# 96_Parallelism_DB_Yamaichi_Rev1_2.net
KiCad netlist of a schematic drawn in EAGLE
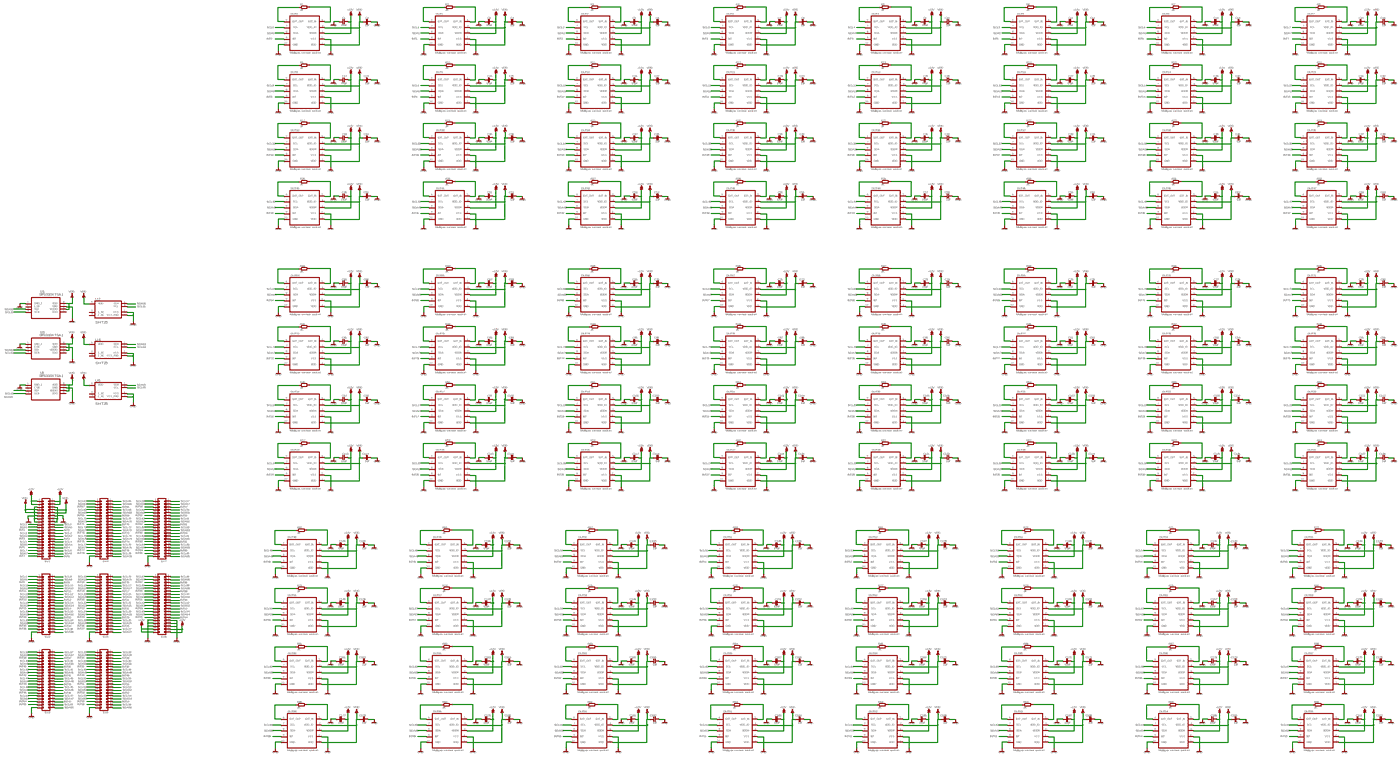
[diagram p0: schematic, sheet 1, overview]
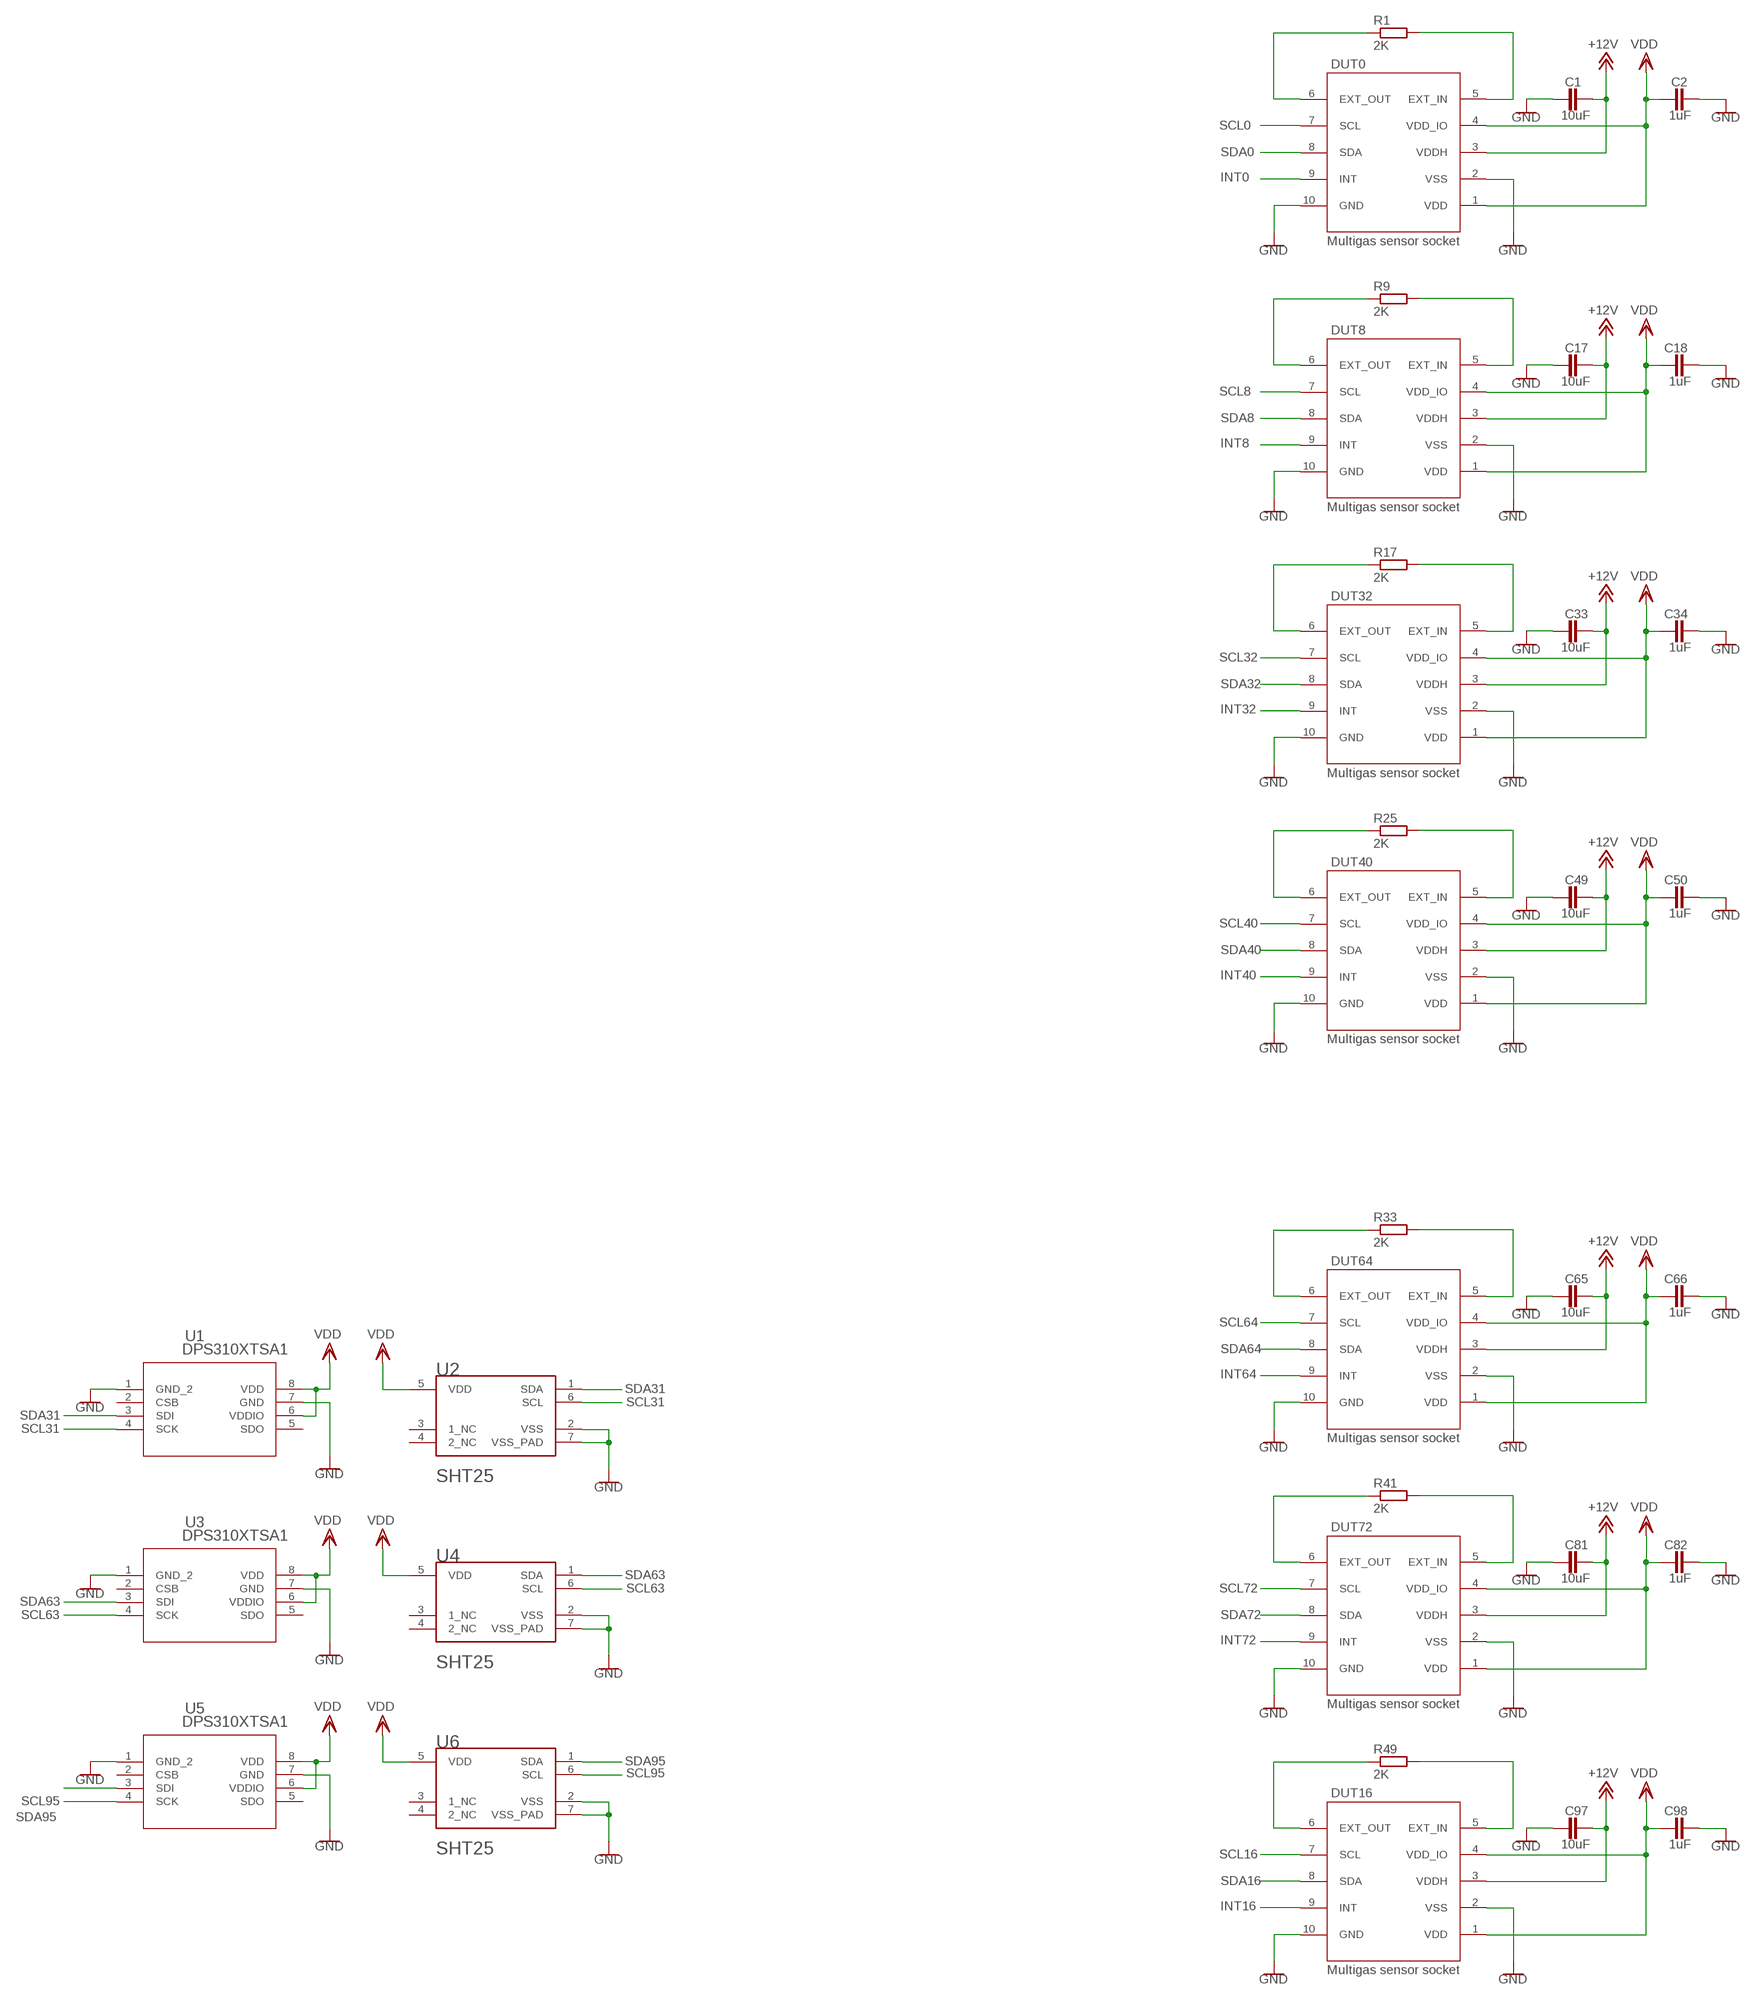
[diagram p1: schematic, sheet 1, part 1 of 8]
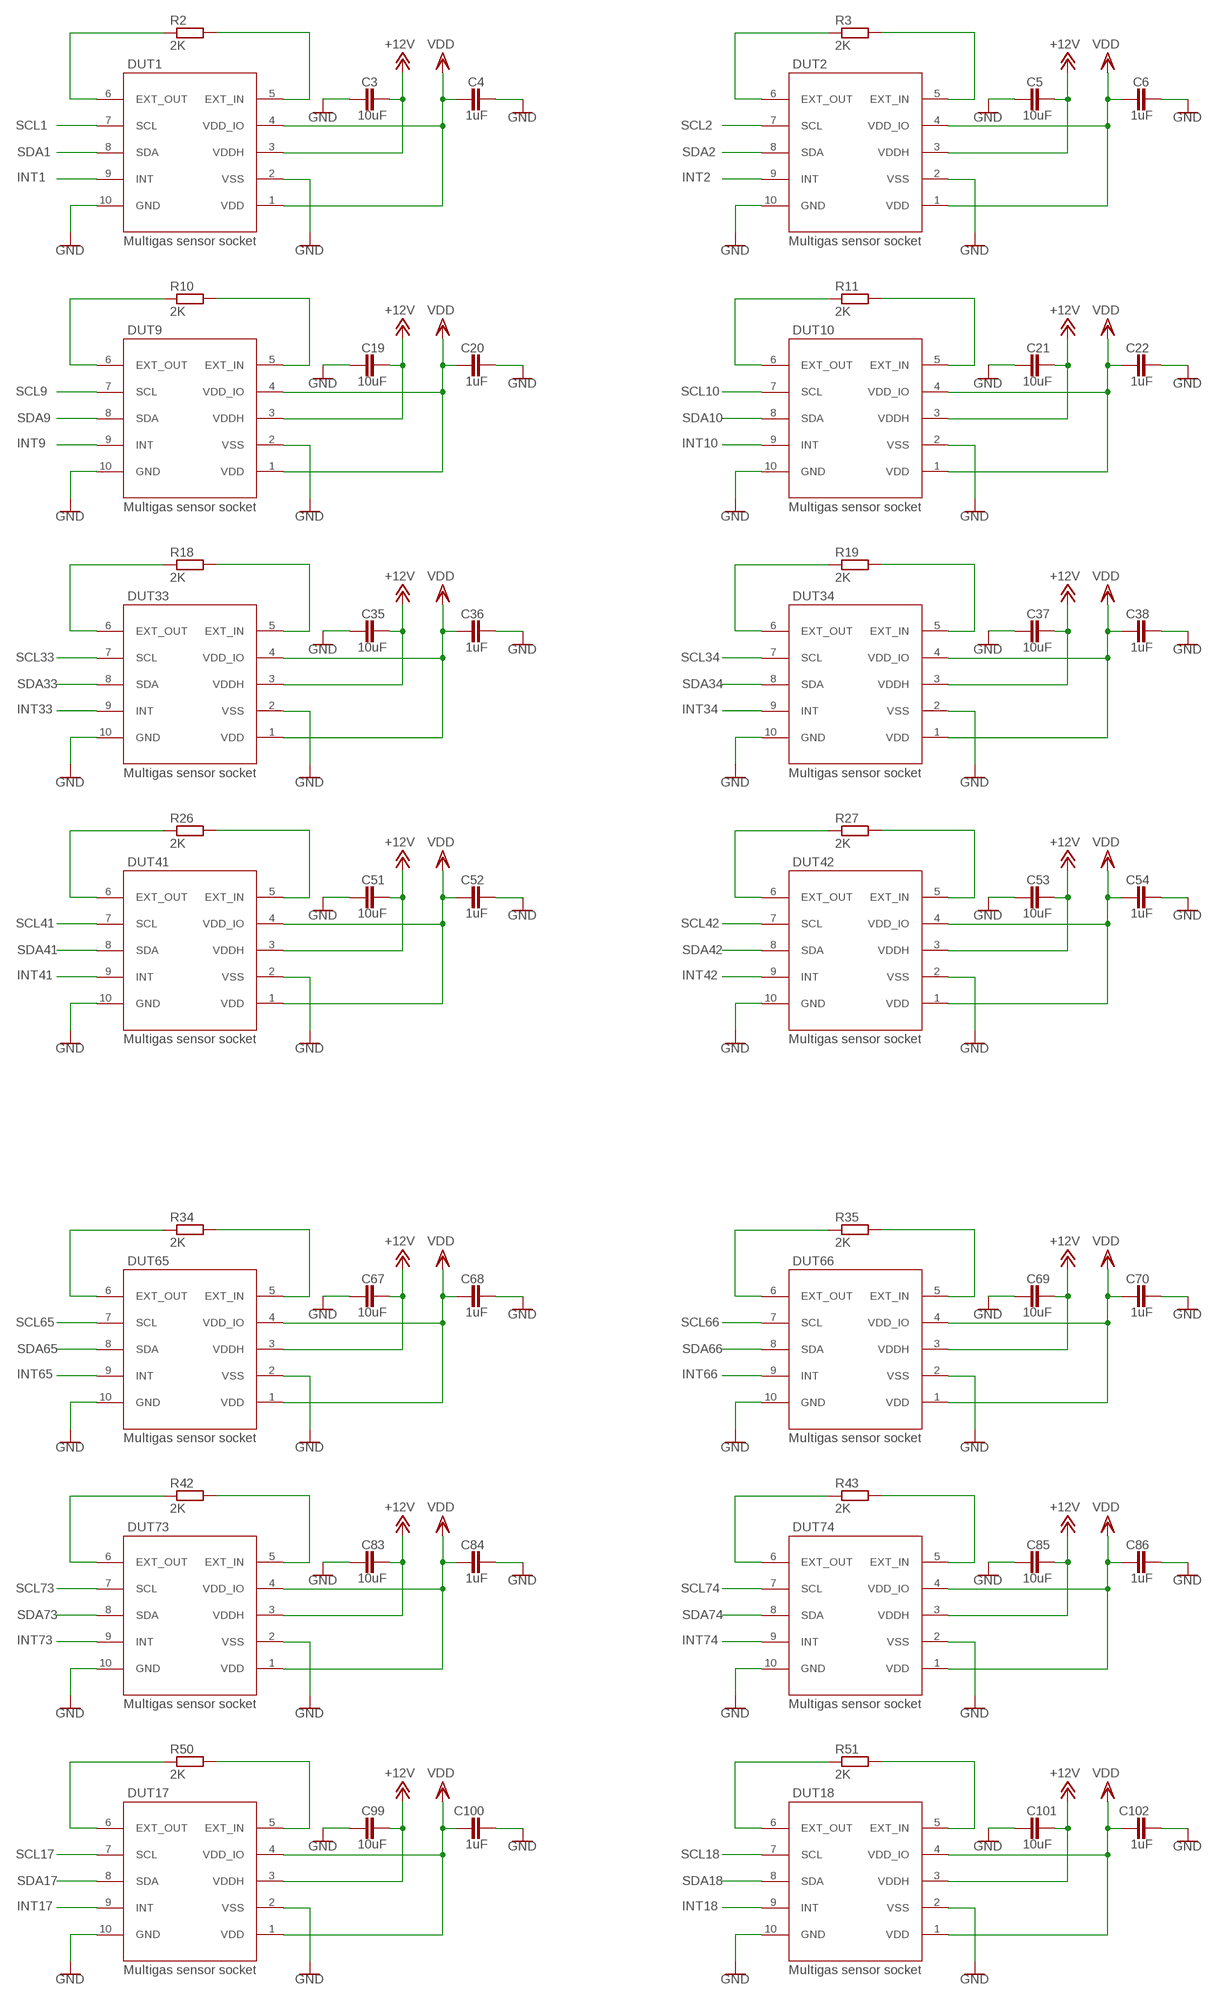
[diagram p2: schematic, sheet 1, part 2 of 8]
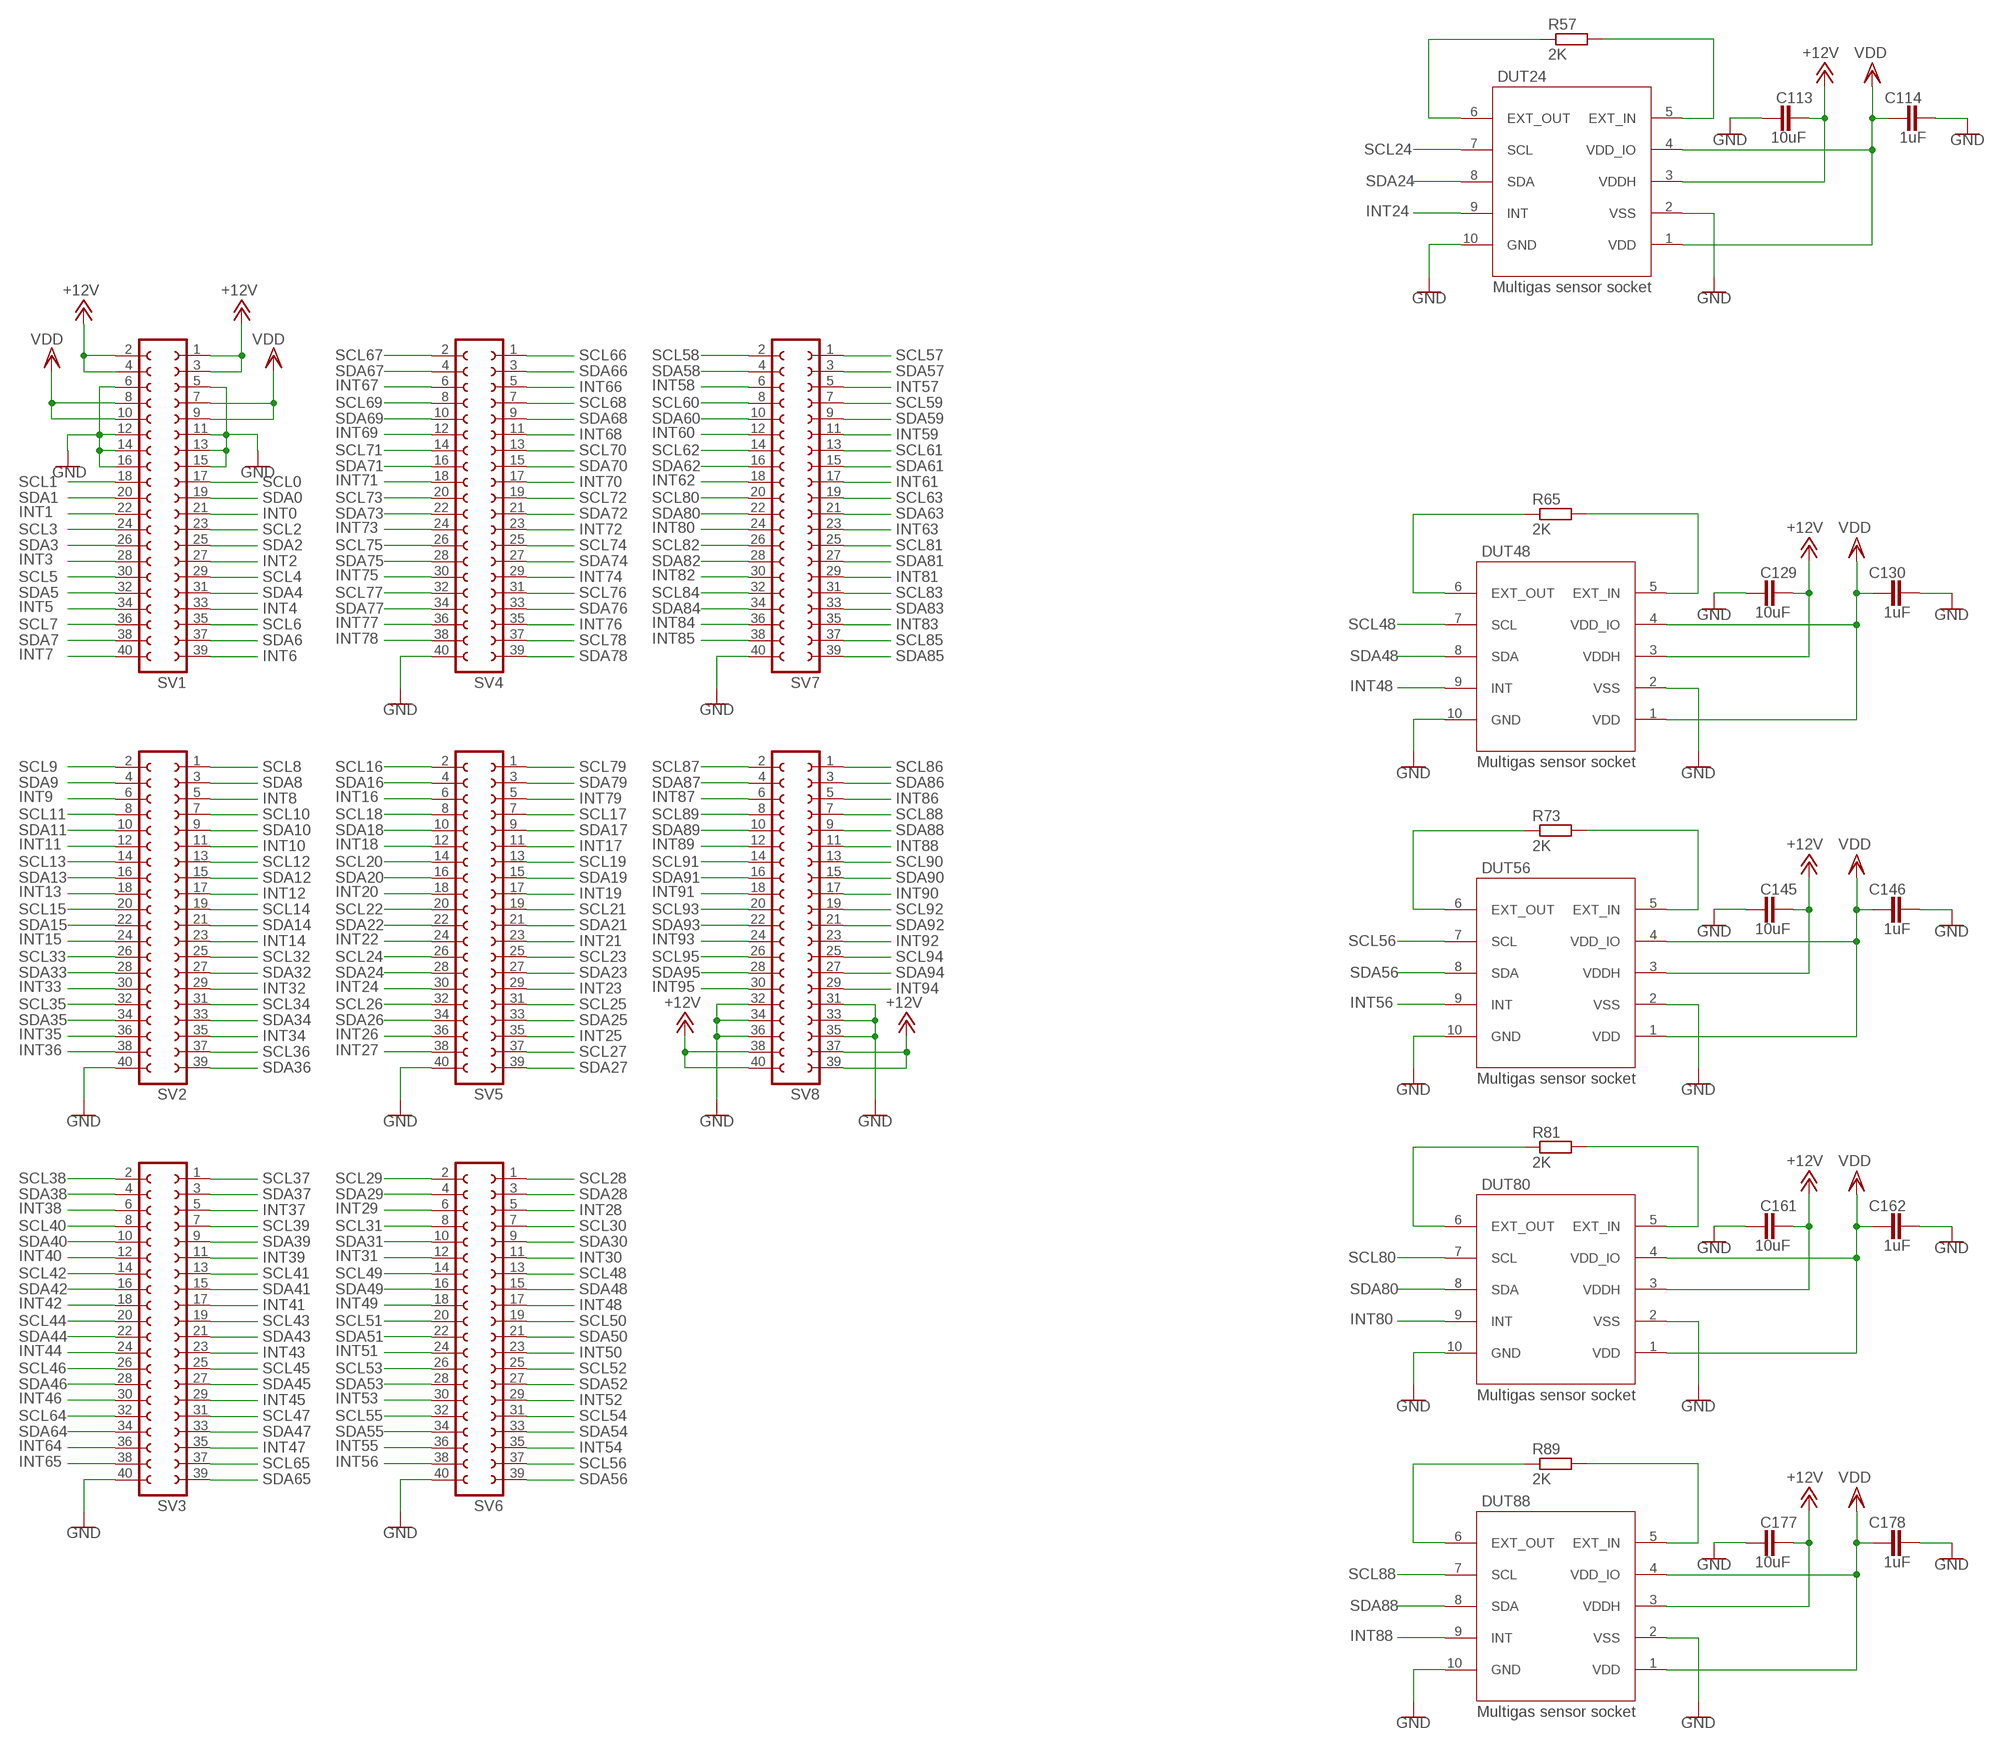
[diagram p3: schematic, sheet 1, part 3 of 8]
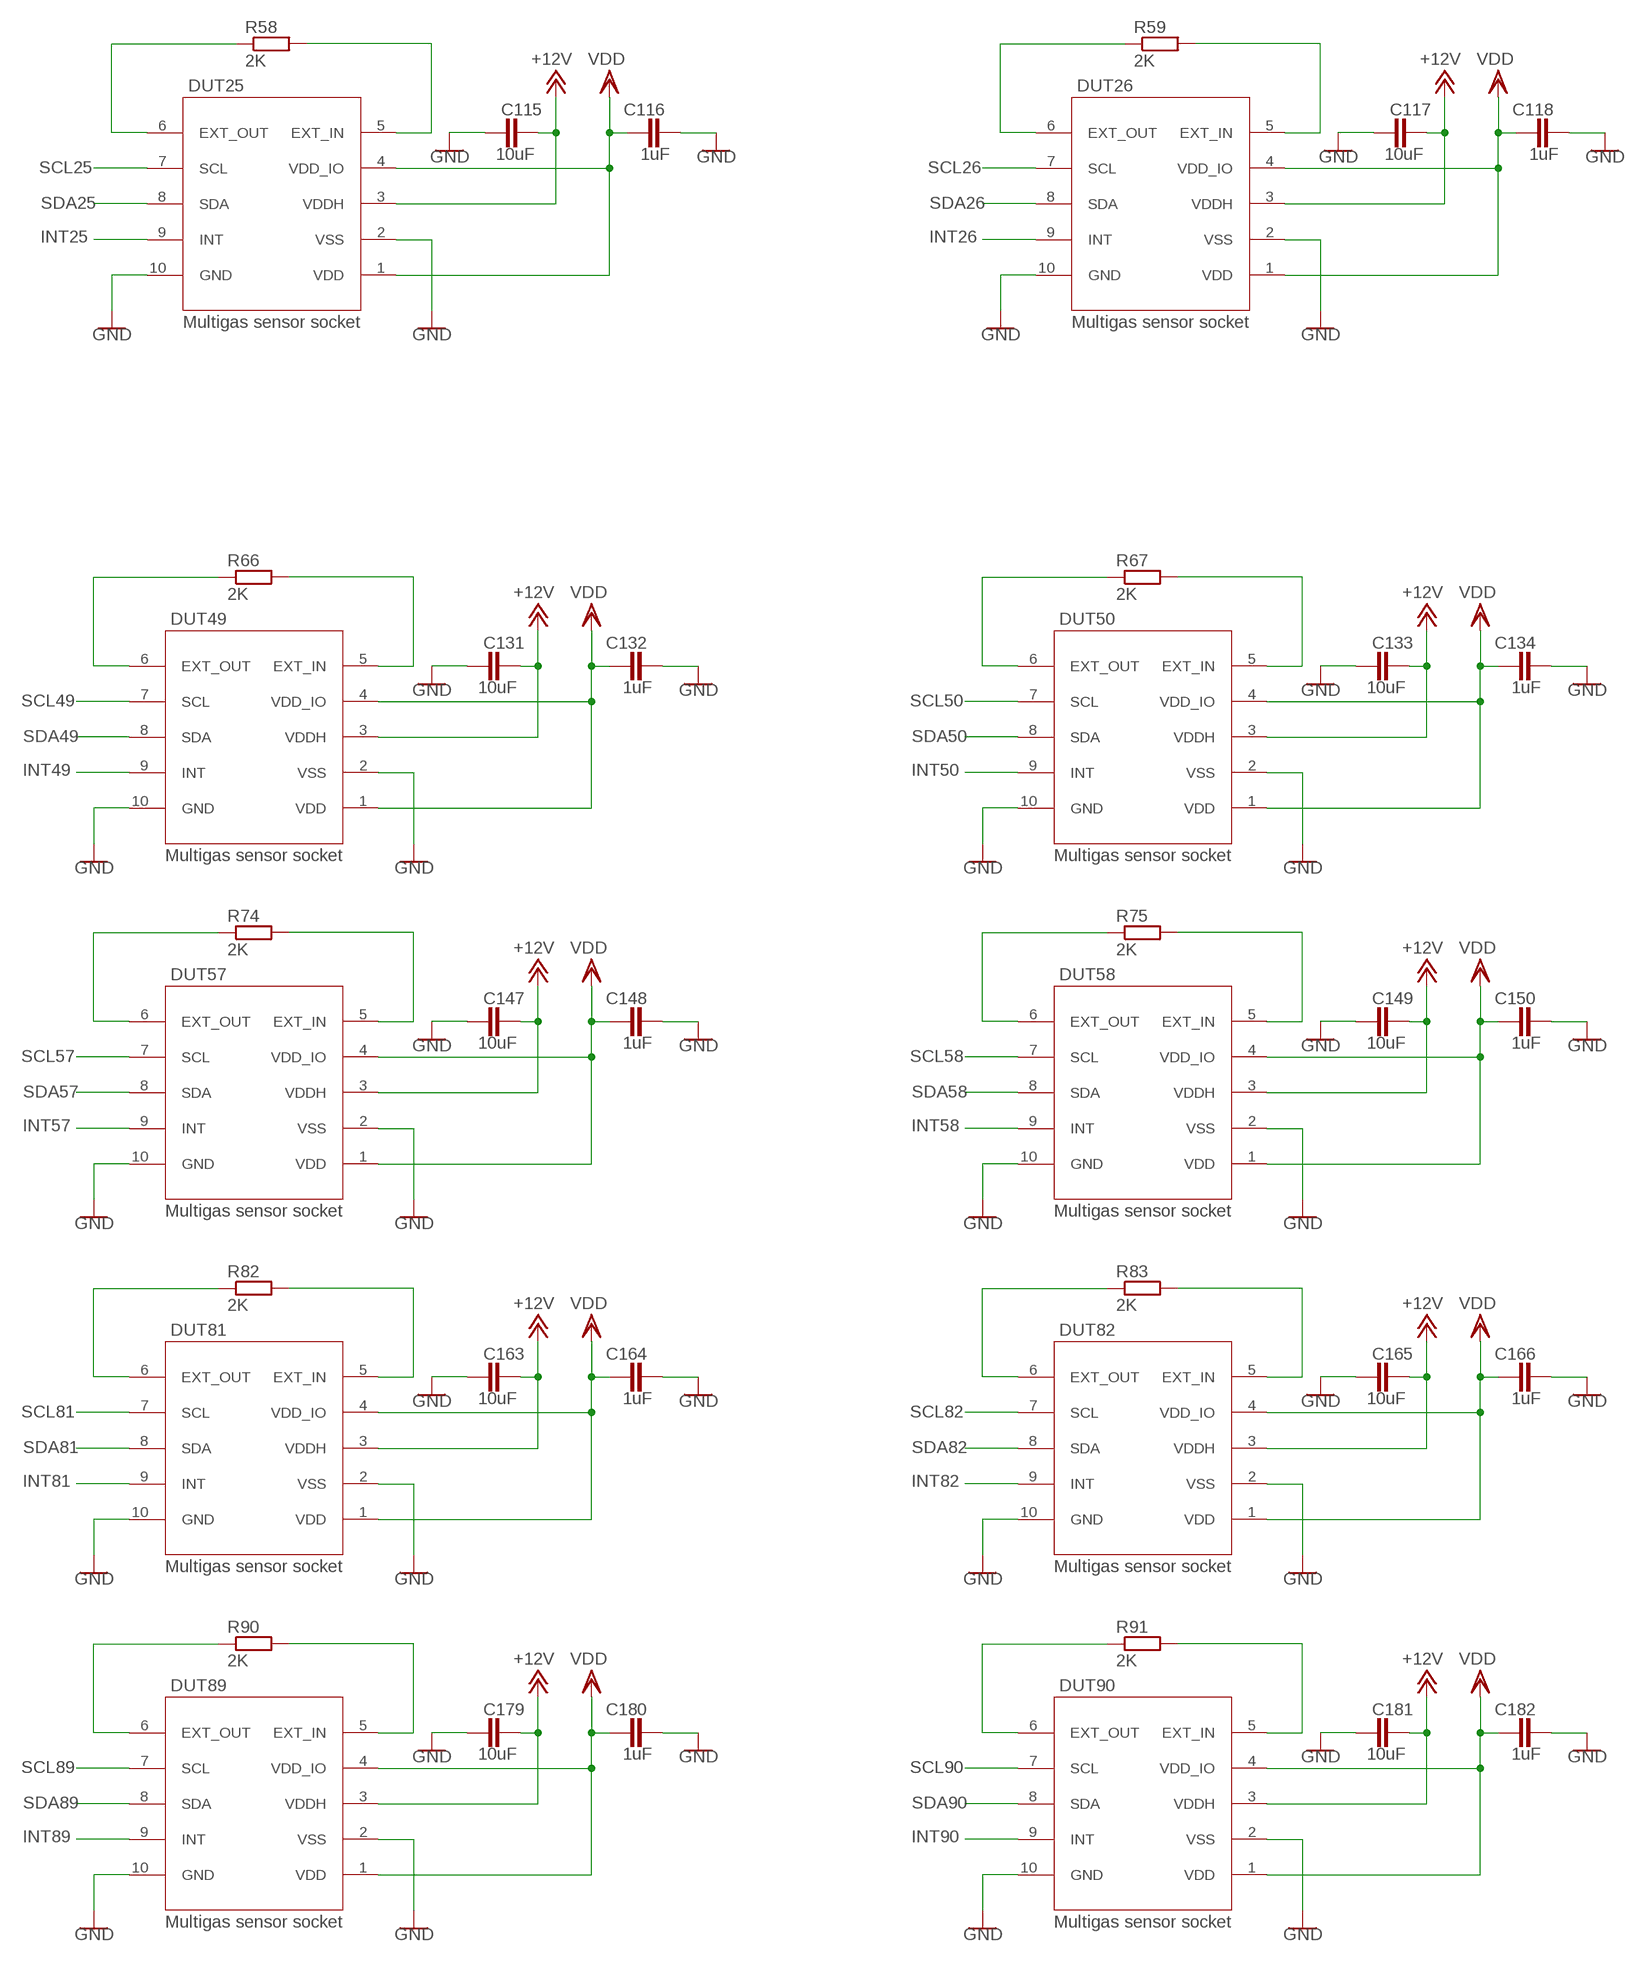
[diagram p4: schematic, sheet 1, part 4 of 8]
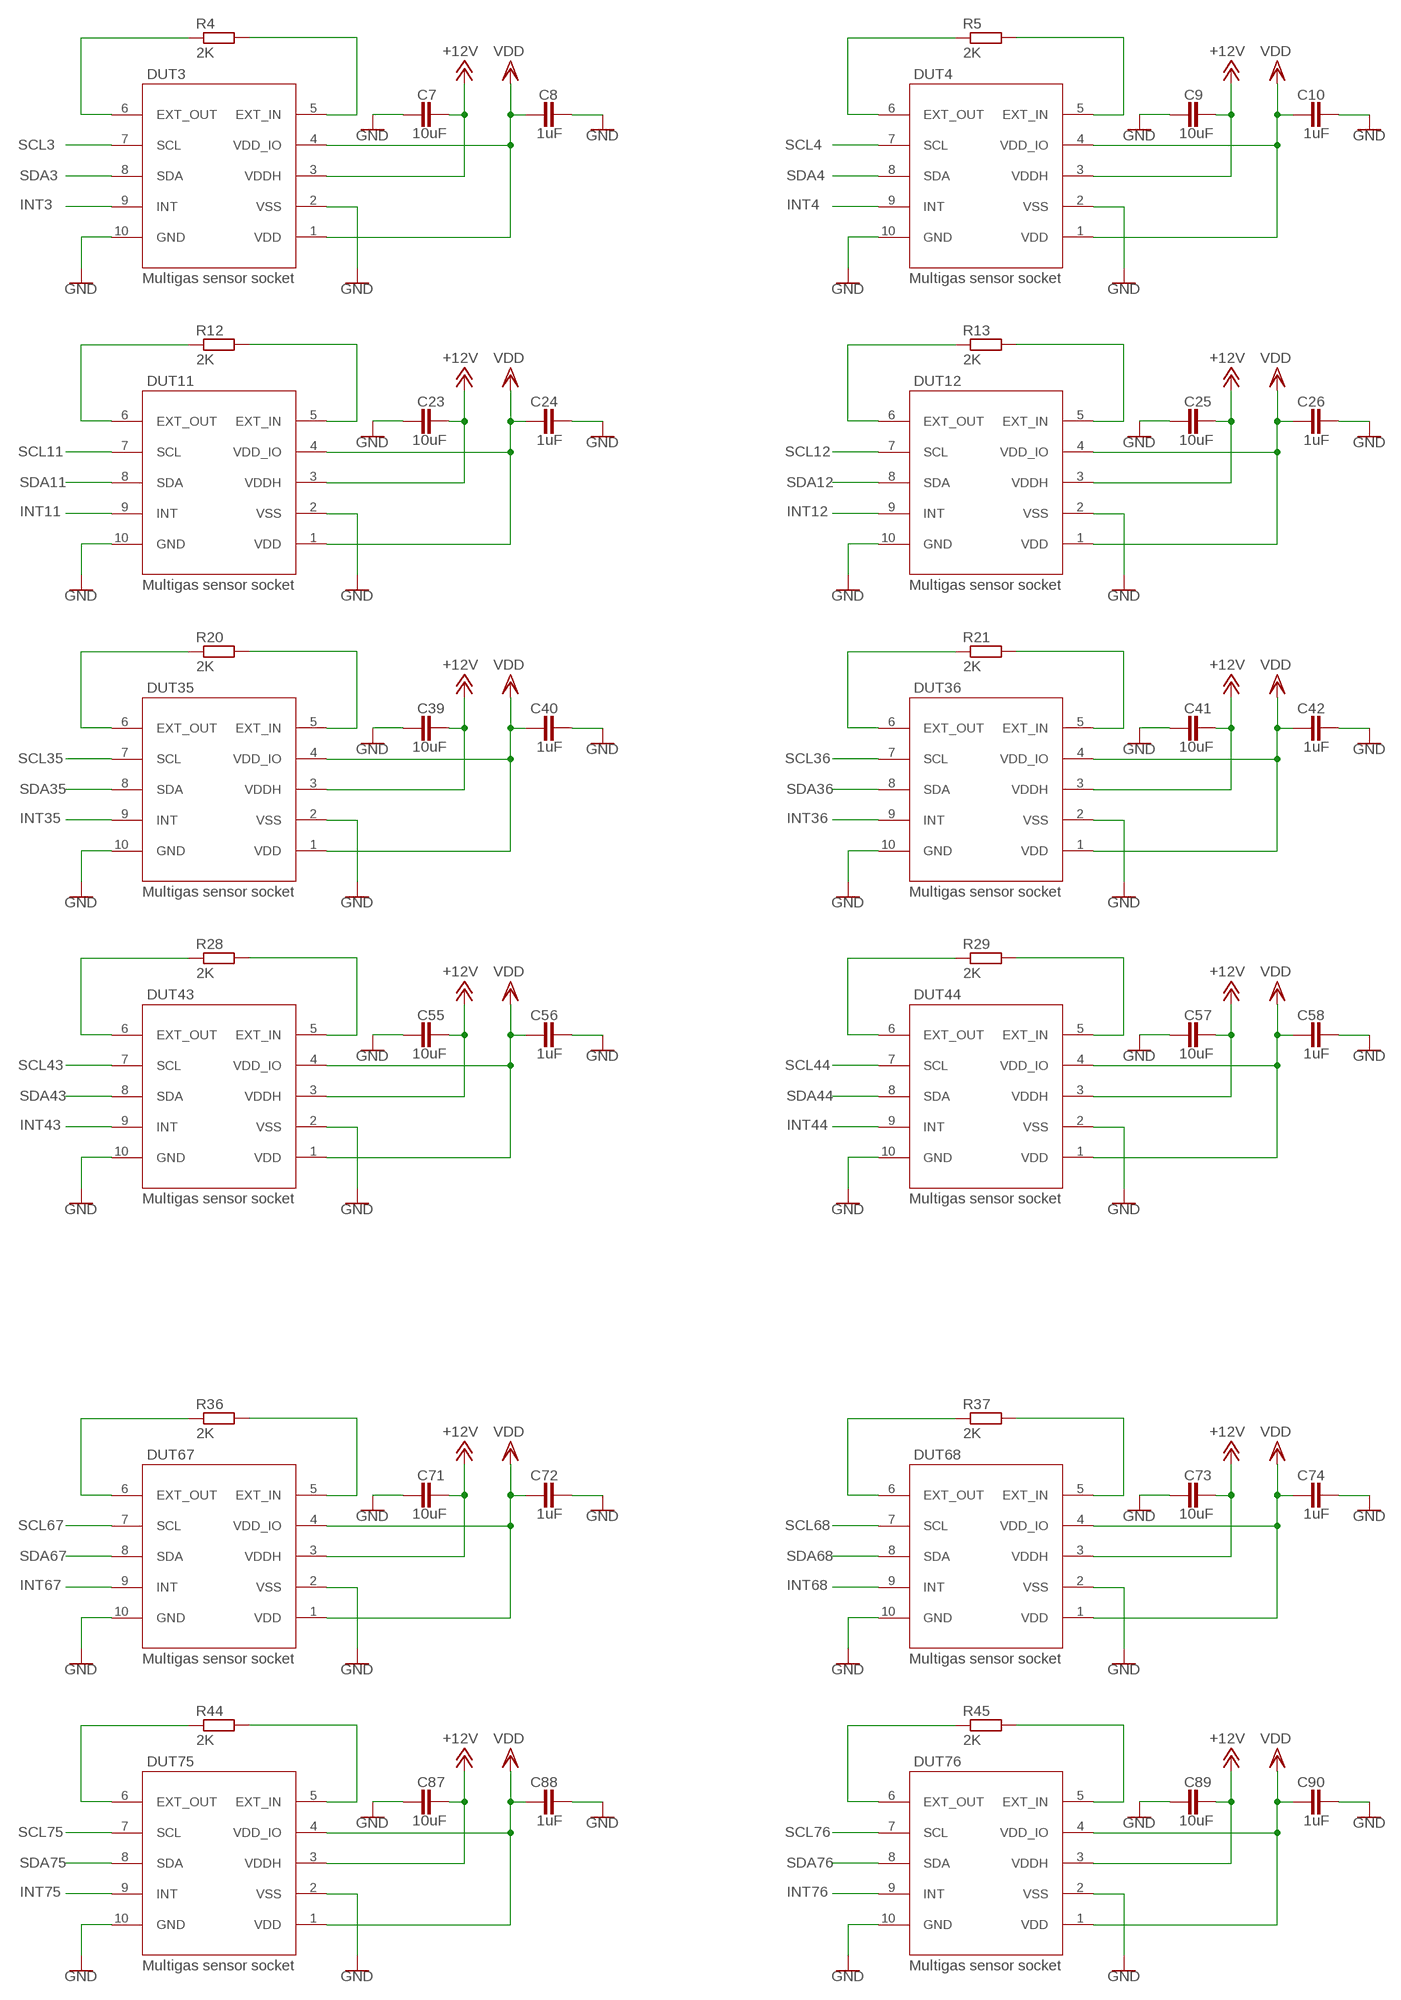
[diagram p5: schematic, sheet 1, part 5 of 8]
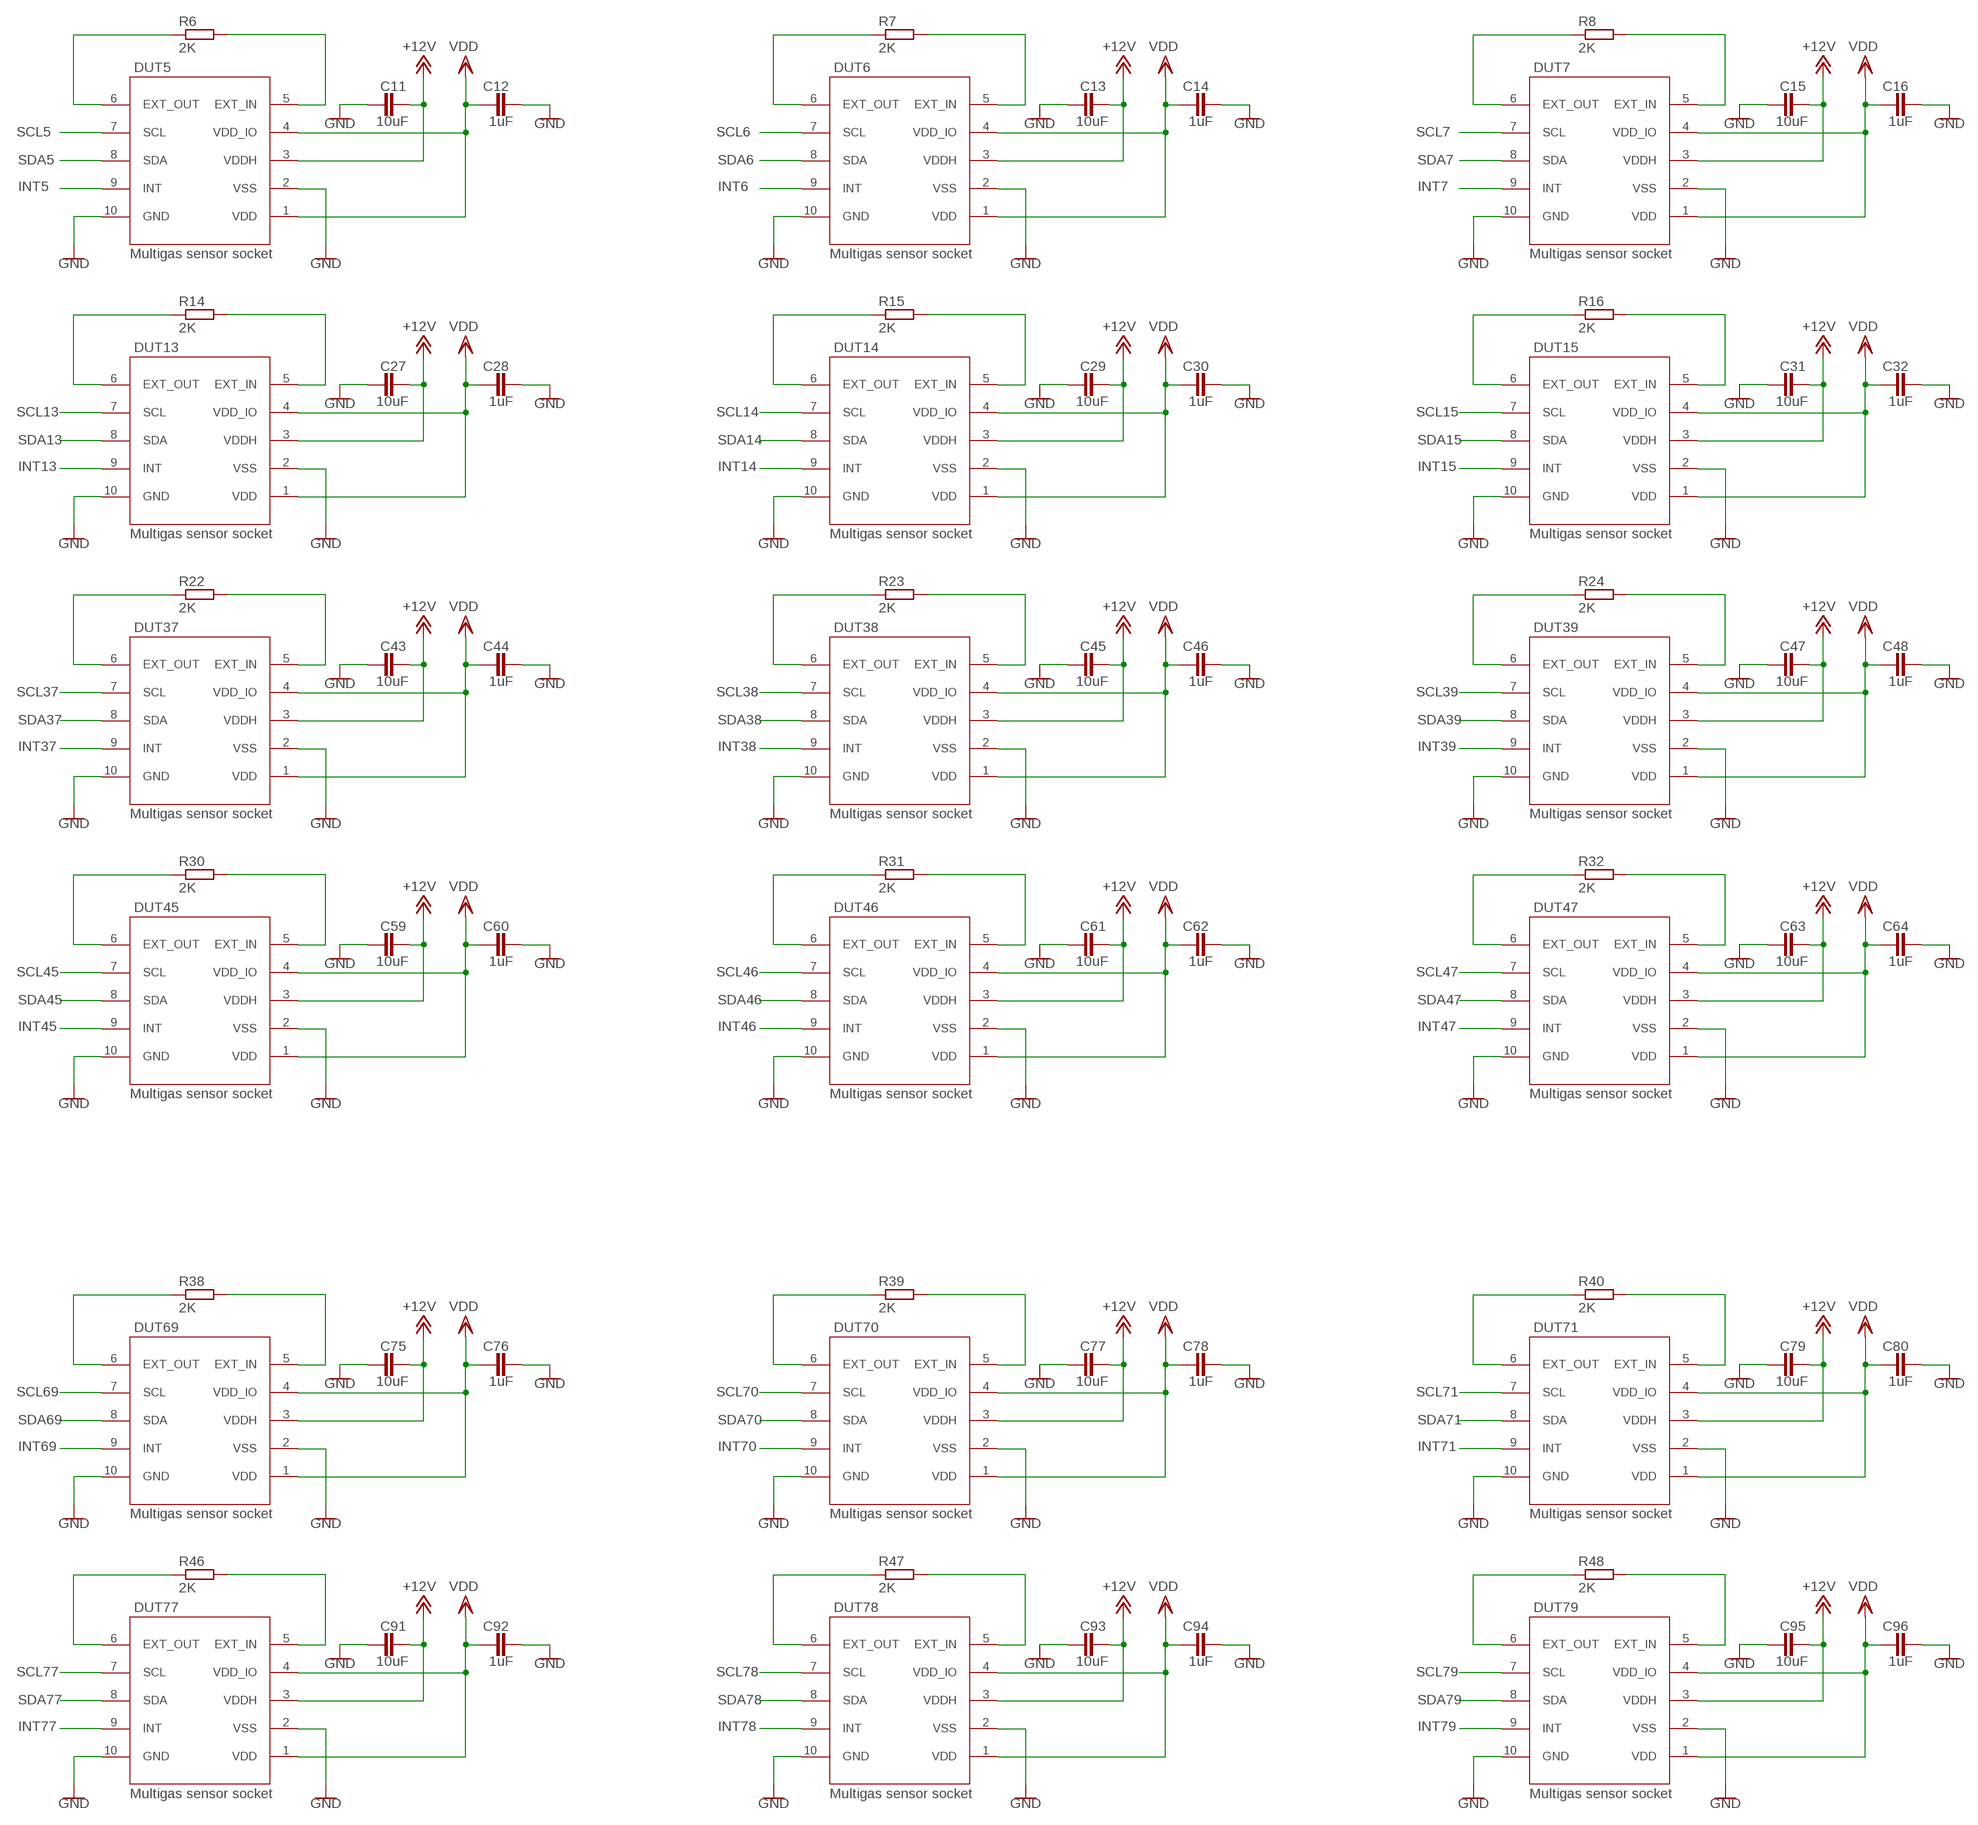
[diagram p6: schematic, sheet 1, part 6 of 8]
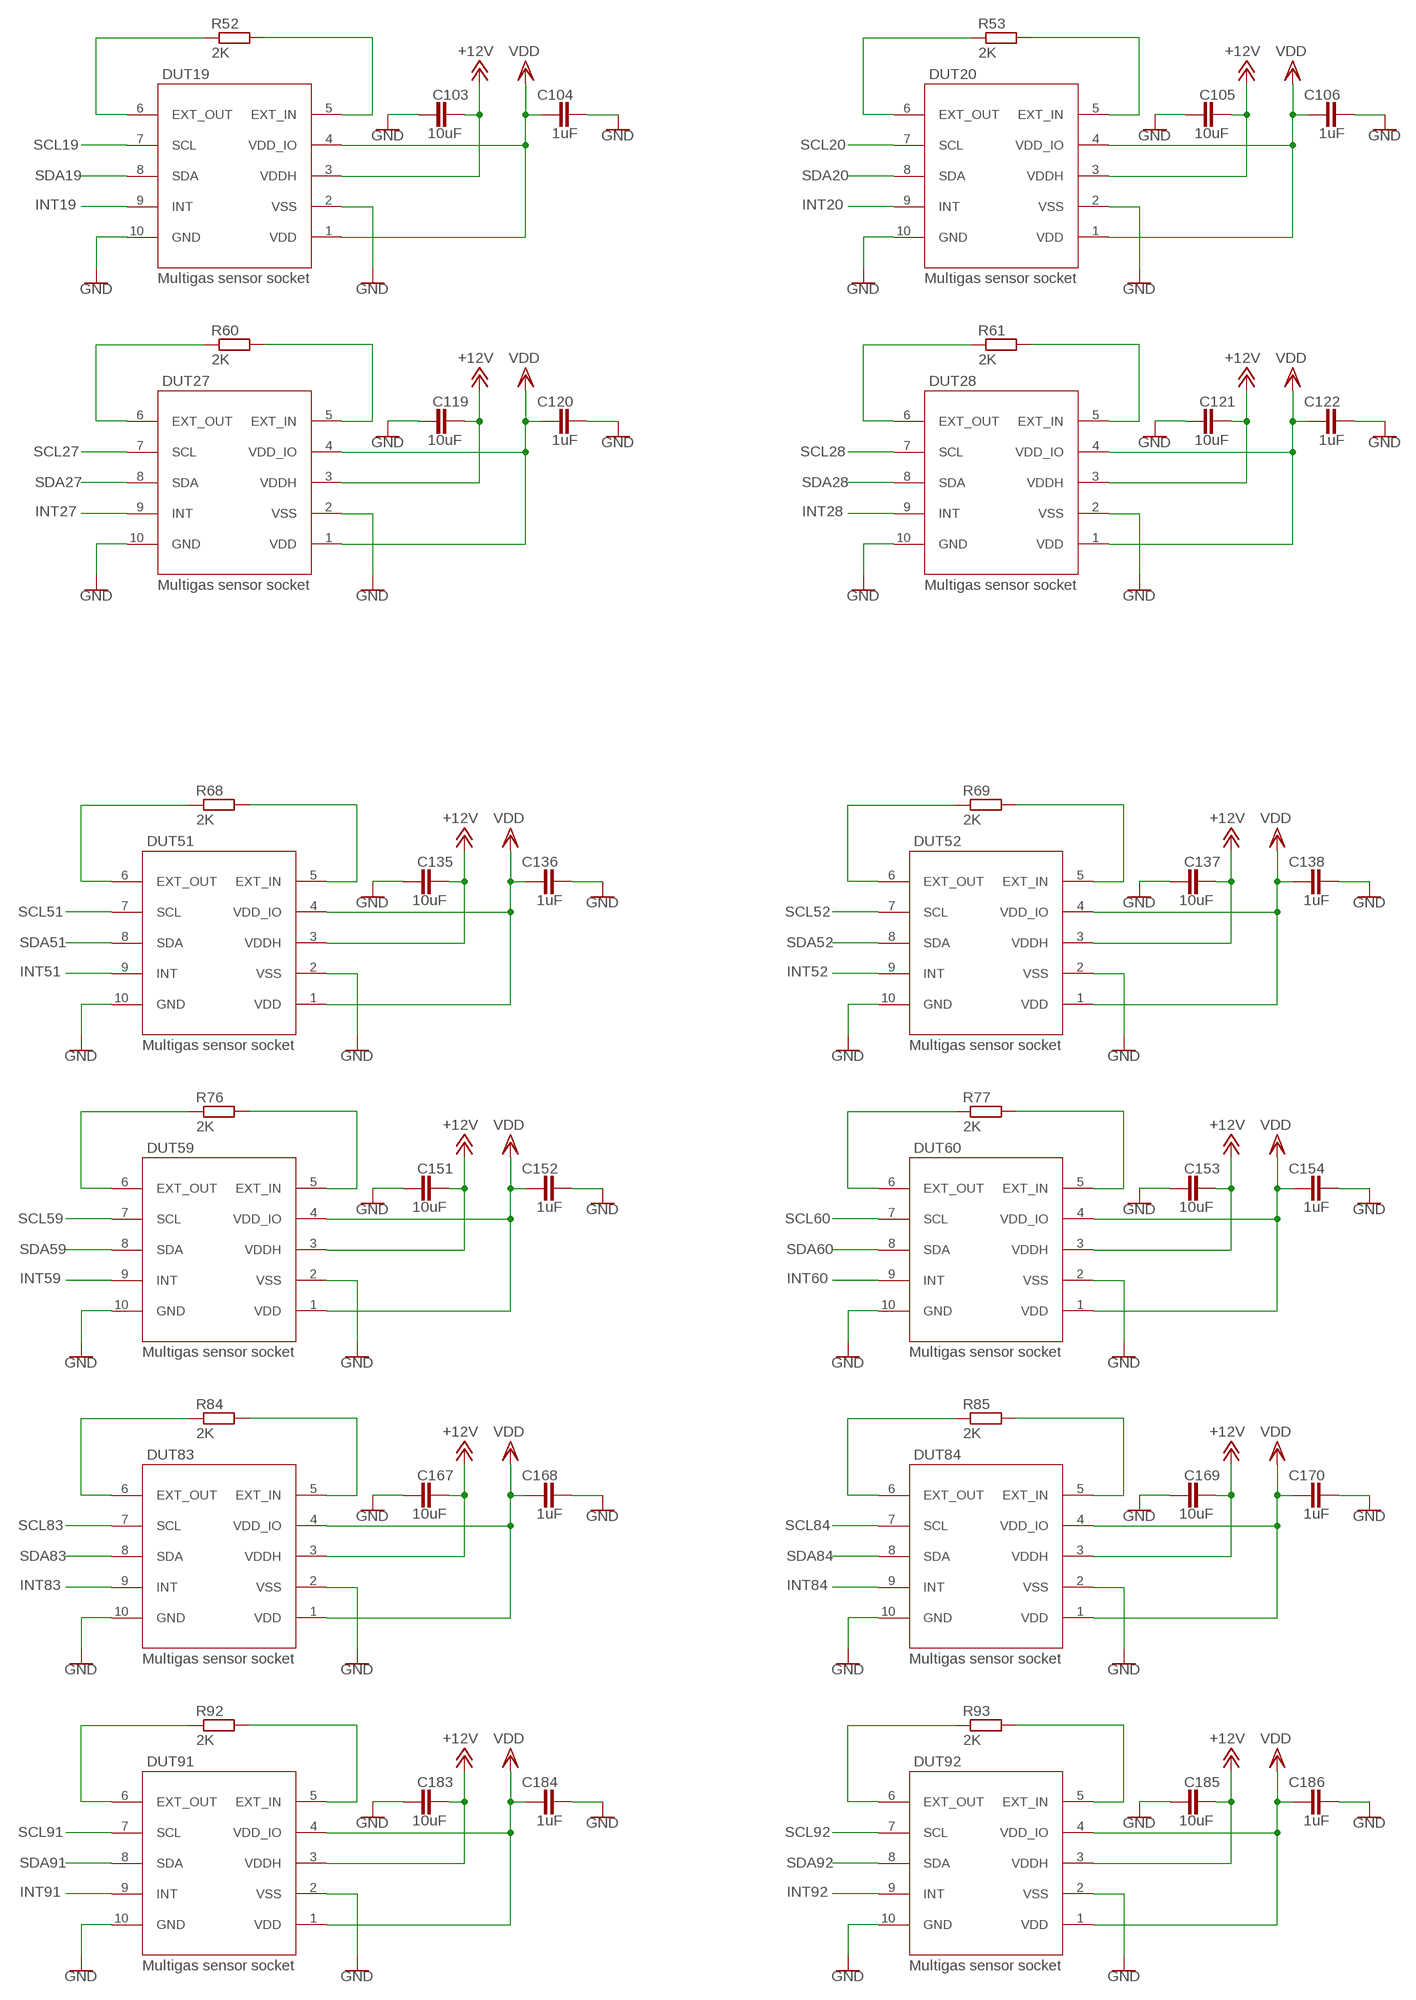
[diagram p7: schematic, sheet 1, part 7 of 8]
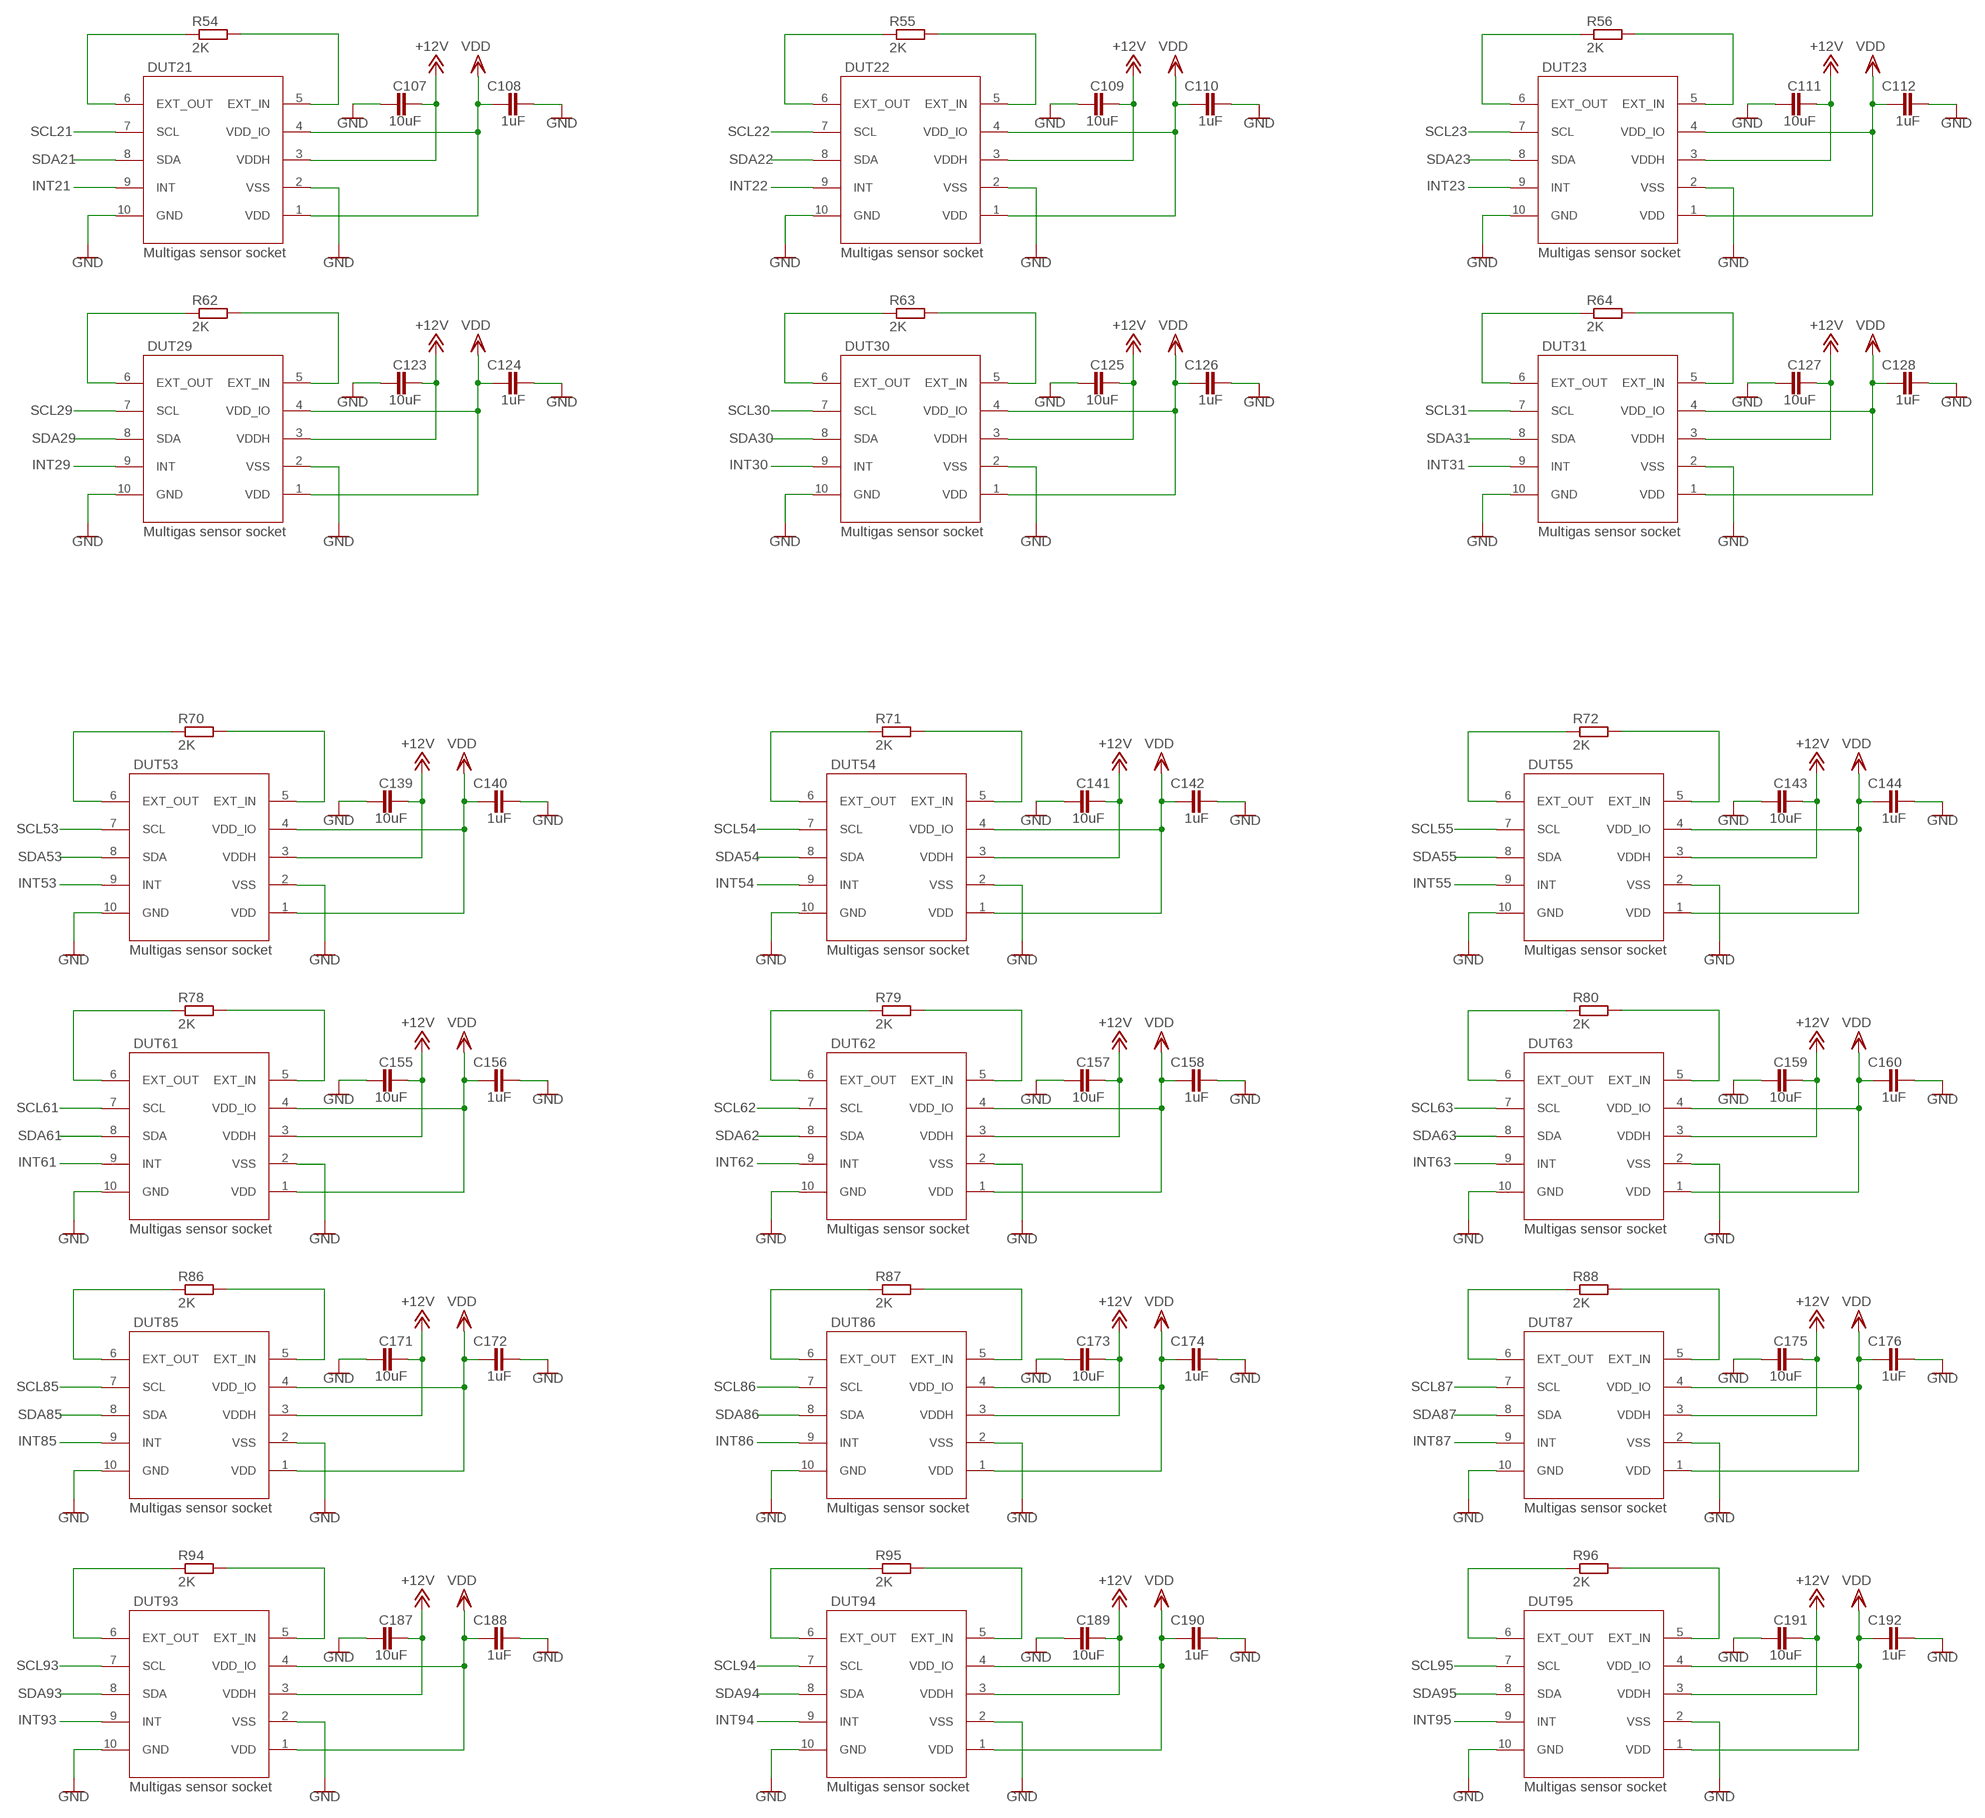
[diagram p8: schematic, sheet 1, part 8 of 8]

(export (version "E")
  (design (tool "Eeschema 10.0.6"))
  (components
    (comp (ref "C1")
      (value "10uF")
      (footprint "eagle-import:C0805")
      (libsource (lib "eagle-import") (part "C-EUC0805"))
    )
    (comp (ref "C2")
      (value "1uF")
      (footprint "eagle-import:C0805")
      (libsource (lib "eagle-import") (part "C-EUC0805"))
    )
    (comp (ref "C3")
      (value "10uF")
      (footprint "eagle-import:C0805")
      (libsource (lib "eagle-import") (part "C-EUC0805"))
    )
    (comp (ref "C4")
      (value "1uF")
      (footprint "eagle-import:C0805")
      (libsource (lib "eagle-import") (part "C-EUC0805"))
    )
    (comp (ref "C5")
      (value "10uF")
      (footprint "eagle-import:C0805")
      (libsource (lib "eagle-import") (part "C-EUC0805"))
    )
    (comp (ref "C6")
      (value "1uF")
      (footprint "eagle-import:C0805")
      (libsource (lib "eagle-import") (part "C-EUC0805"))
    )
    (comp (ref "C7")
      (value "10uF")
      (footprint "eagle-import:C0805")
      (libsource (lib "eagle-import") (part "C-EUC0805"))
    )
    (comp (ref "C8")
      (value "1uF")
      (footprint "eagle-import:C0805")
      (libsource (lib "eagle-import") (part "C-EUC0805"))
    )
    (comp (ref "C9")
      (value "10uF")
      (footprint "eagle-import:C0805")
      (libsource (lib "eagle-import") (part "C-EUC0805"))
    )
    (comp (ref "C10")
      (value "1uF")
      (footprint "eagle-import:C0805")
      (libsource (lib "eagle-import") (part "C-EUC0805"))
    )
    (comp (ref "C11")
      (value "10uF")
      (footprint "eagle-import:C0805")
      (libsource (lib "eagle-import") (part "C-EUC0805"))
    )
    (comp (ref "C12")
      (value "1uF")
      (footprint "eagle-import:C0805")
      (libsource (lib "eagle-import") (part "C-EUC0805"))
    )
    (comp (ref "C13")
      (value "10uF")
      (footprint "eagle-import:C0805")
      (libsource (lib "eagle-import") (part "C-EUC0805"))
    )
    (comp (ref "C14")
      (value "1uF")
      (footprint "eagle-import:C0805")
      (libsource (lib "eagle-import") (part "C-EUC0805"))
    )
    (comp (ref "C15")
      (value "10uF")
      (footprint "eagle-import:C0805")
      (libsource (lib "eagle-import") (part "C-EUC0805"))
    )
    (comp (ref "C16")
      (value "1uF")
      (footprint "eagle-import:C0805")
      (libsource (lib "eagle-import") (part "C-EUC0805"))
    )
    (comp (ref "C17")
      (value "10uF")
      (footprint "eagle-import:C0805")
      (libsource (lib "eagle-import") (part "C-EUC0805"))
    )
    (comp (ref "C18")
      (value "1uF")
      (footprint "eagle-import:C0805")
      (libsource (lib "eagle-import") (part "C-EUC0805"))
    )
    (comp (ref "C19")
      (value "10uF")
      (footprint "eagle-import:C0805")
      (libsource (lib "eagle-import") (part "C-EUC0805"))
    )
    (comp (ref "C20")
      (value "1uF")
      (footprint "eagle-import:C0805")
      (libsource (lib "eagle-import") (part "C-EUC0805"))
    )
    (comp (ref "C21")
      (value "10uF")
      (footprint "eagle-import:C0805")
      (libsource (lib "eagle-import") (part "C-EUC0805"))
    )
    (comp (ref "C22")
      (value "1uF")
      (footprint "eagle-import:C0805")
      (libsource (lib "eagle-import") (part "C-EUC0805"))
    )
    (comp (ref "C23")
      (value "10uF")
      (footprint "eagle-import:C0805")
      (libsource (lib "eagle-import") (part "C-EUC0805"))
    )
    (comp (ref "C24")
      (value "1uF")
      (footprint "eagle-import:C0805")
      (libsource (lib "eagle-import") (part "C-EUC0805"))
    )
    (comp (ref "C25")
      (value "10uF")
      (footprint "eagle-import:C0805")
      (libsource (lib "eagle-import") (part "C-EUC0805"))
    )
    (comp (ref "C26")
      (value "1uF")
      (footprint "eagle-import:C0805")
      (libsource (lib "eagle-import") (part "C-EUC0805"))
    )
    (comp (ref "C27")
      (value "10uF")
      (footprint "eagle-import:C0805")
      (libsource (lib "eagle-import") (part "C-EUC0805"))
    )
    (comp (ref "C28")
      (value "1uF")
      (footprint "eagle-import:C0805")
      (libsource (lib "eagle-import") (part "C-EUC0805"))
    )
    (comp (ref "C29")
      (value "10uF")
      (footprint "eagle-import:C0805")
      (libsource (lib "eagle-import") (part "C-EUC0805"))
    )
    (comp (ref "C30")
      (value "1uF")
      (footprint "eagle-import:C0805")
      (libsource (lib "eagle-import") (part "C-EUC0805"))
    )
    (comp (ref "C31")
      (value "10uF")
      (footprint "eagle-import:C0805")
      (libsource (lib "eagle-import") (part "C-EUC0805"))
    )
    (comp (ref "C32")
      (value "1uF")
      (footprint "eagle-import:C0805")
      (libsource (lib "eagle-import") (part "C-EUC0805"))
    )
    (comp (ref "C33")
      (value "10uF")
      (footprint "eagle-import:C0805")
      (libsource (lib "eagle-import") (part "C-EUC0805"))
    )
    (comp (ref "C34")
      (value "1uF")
      (footprint "eagle-import:C0805")
      (libsource (lib "eagle-import") (part "C-EUC0805"))
    )
    (comp (ref "C35")
      (value "10uF")
      (footprint "eagle-import:C0805")
      (libsource (lib "eagle-import") (part "C-EUC0805"))
    )
    (comp (ref "C36")
      (value "1uF")
      (footprint "eagle-import:C0805")
      (libsource (lib "eagle-import") (part "C-EUC0805"))
    )
    (comp (ref "C37")
      (value "10uF")
      (footprint "eagle-import:C0805")
      (libsource (lib "eagle-import") (part "C-EUC0805"))
    )
    (comp (ref "C38")
      (value "1uF")
      (footprint "eagle-import:C0805")
      (libsource (lib "eagle-import") (part "C-EUC0805"))
    )
    (comp (ref "C39")
      (value "10uF")
      (footprint "eagle-import:C0805")
      (libsource (lib "eagle-import") (part "C-EUC0805"))
    )
    (comp (ref "C40")
      (value "1uF")
      (footprint "eagle-import:C0805")
      (libsource (lib "eagle-import") (part "C-EUC0805"))
    )
    (comp (ref "C41")
      (value "10uF")
      (footprint "eagle-import:C0805")
      (libsource (lib "eagle-import") (part "C-EUC0805"))
    )
    (comp (ref "C42")
      (value "1uF")
      (footprint "eagle-import:C0805")
      (libsource (lib "eagle-import") (part "C-EUC0805"))
    )
    (comp (ref "C43")
      (value "10uF")
      (footprint "eagle-import:C0805")
      (libsource (lib "eagle-import") (part "C-EUC0805"))
    )
    (comp (ref "C44")
      (value "1uF")
      (footprint "eagle-import:C0805")
      (libsource (lib "eagle-import") (part "C-EUC0805"))
    )
    (comp (ref "C45")
      (value "10uF")
      (footprint "eagle-import:C0805")
      (libsource (lib "eagle-import") (part "C-EUC0805"))
    )
    (comp (ref "C46")
      (value "1uF")
      (footprint "eagle-import:C0805")
      (libsource (lib "eagle-import") (part "C-EUC0805"))
    )
    (comp (ref "C47")
      (value "10uF")
      (footprint "eagle-import:C0805")
      (libsource (lib "eagle-import") (part "C-EUC0805"))
    )
    (comp (ref "C48")
      (value "1uF")
      (footprint "eagle-import:C0805")
      (libsource (lib "eagle-import") (part "C-EUC0805"))
    )
    (comp (ref "C49")
      (value "10uF")
      (footprint "eagle-import:C0805")
      (libsource (lib "eagle-import") (part "C-EUC0805"))
    )
    (comp (ref "C50")
      (value "1uF")
      (footprint "eagle-import:C0805")
      (libsource (lib "eagle-import") (part "C-EUC0805"))
    )
    (comp (ref "C51")
      (value "10uF")
      (footprint "eagle-import:C0805")
      (libsource (lib "eagle-import") (part "C-EUC0805"))
    )
    (comp (ref "C52")
      (value "1uF")
      (footprint "eagle-import:C0805")
      (libsource (lib "eagle-import") (part "C-EUC0805"))
    )
    (comp (ref "C53")
      (value "10uF")
      (footprint "eagle-import:C0805")
      (libsource (lib "eagle-import") (part "C-EUC0805"))
    )
    (comp (ref "C54")
      (value "1uF")
      (footprint "eagle-import:C0805")
      (libsource (lib "eagle-import") (part "C-EUC0805"))
    )
    (comp (ref "C55")
      (value "10uF")
      (footprint "eagle-import:C0805")
      (libsource (lib "eagle-import") (part "C-EUC0805"))
    )
    (comp (ref "C56")
      (value "1uF")
      (footprint "eagle-import:C0805")
      (libsource (lib "eagle-import") (part "C-EUC0805"))
    )
    (comp (ref "C57")
      (value "10uF")
      (footprint "eagle-import:C0805")
      (libsource (lib "eagle-import") (part "C-EUC0805"))
    )
    (comp (ref "C58")
      (value "1uF")
      (footprint "eagle-import:C0805")
      (libsource (lib "eagle-import") (part "C-EUC0805"))
    )
    (comp (ref "C59")
      (value "10uF")
      (footprint "eagle-import:C0805")
      (libsource (lib "eagle-import") (part "C-EUC0805"))
    )
    (comp (ref "C60")
      (value "1uF")
      (footprint "eagle-import:C0805")
      (libsource (lib "eagle-import") (part "C-EUC0805"))
    )
    (comp (ref "C61")
      (value "10uF")
      (footprint "eagle-import:C0805")
      (libsource (lib "eagle-import") (part "C-EUC0805"))
    )
    (comp (ref "C62")
      (value "1uF")
      (footprint "eagle-import:C0805")
      (libsource (lib "eagle-import") (part "C-EUC0805"))
    )
    (comp (ref "C63")
      (value "10uF")
      (footprint "eagle-import:C0805")
      (libsource (lib "eagle-import") (part "C-EUC0805"))
    )
    (comp (ref "C64")
      (value "1uF")
      (footprint "eagle-import:C0805")
      (libsource (lib "eagle-import") (part "C-EUC0805"))
    )
    (comp (ref "C65")
      (value "10uF")
      (footprint "eagle-import:C0805")
      (libsource (lib "eagle-import") (part "C-EUC0805"))
    )
    (comp (ref "C66")
      (value "1uF")
      (footprint "eagle-import:C0805")
      (libsource (lib "eagle-import") (part "C-EUC0805"))
    )
    (comp (ref "C67")
      (value "10uF")
      (footprint "eagle-import:C0805")
      (libsource (lib "eagle-import") (part "C-EUC0805"))
    )
    (comp (ref "C68")
      (value "1uF")
      (footprint "eagle-import:C0805")
      (libsource (lib "eagle-import") (part "C-EUC0805"))
    )
    (comp (ref "C69")
      (value "10uF")
      (footprint "eagle-import:C0805")
      (libsource (lib "eagle-import") (part "C-EUC0805"))
    )
    (comp (ref "C70")
      (value "1uF")
      (footprint "eagle-import:C0805")
      (libsource (lib "eagle-import") (part "C-EUC0805"))
    )
    (comp (ref "C71")
      (value "10uF")
      (footprint "eagle-import:C0805")
      (libsource (lib "eagle-import") (part "C-EUC0805"))
    )
    (comp (ref "C72")
      (value "1uF")
      (footprint "eagle-import:C0805")
      (libsource (lib "eagle-import") (part "C-EUC0805"))
    )
    (comp (ref "C73")
      (value "10uF")
      (footprint "eagle-import:C0805")
      (libsource (lib "eagle-import") (part "C-EUC0805"))
    )
    (comp (ref "C74")
      (value "1uF")
      (footprint "eagle-import:C0805")
      (libsource (lib "eagle-import") (part "C-EUC0805"))
    )
    (comp (ref "C75")
      (value "10uF")
      (footprint "eagle-import:C0805")
      (libsource (lib "eagle-import") (part "C-EUC0805"))
    )
    (comp (ref "C76")
      (value "1uF")
      (footprint "eagle-import:C0805")
      (libsource (lib "eagle-import") (part "C-EUC0805"))
    )
    (comp (ref "C77")
      (value "10uF")
      (footprint "eagle-import:C0805")
      (libsource (lib "eagle-import") (part "C-EUC0805"))
    )
    (comp (ref "C78")
      (value "1uF")
      (footprint "eagle-import:C0805")
      (libsource (lib "eagle-import") (part "C-EUC0805"))
    )
    (comp (ref "C79")
      (value "10uF")
      (footprint "eagle-import:C0805")
      (libsource (lib "eagle-import") (part "C-EUC0805"))
    )
    (comp (ref "C80")
      (value "1uF")
      (footprint "eagle-import:C0805")
      (libsource (lib "eagle-import") (part "C-EUC0805"))
    )
    (comp (ref "C81")
      (value "10uF")
      (footprint "eagle-import:C0805")
      (libsource (lib "eagle-import") (part "C-EUC0805"))
    )
    (comp (ref "C82")
      (value "1uF")
      (footprint "eagle-import:C0805")
      (libsource (lib "eagle-import") (part "C-EUC0805"))
    )
    (comp (ref "C83")
      (value "10uF")
      (footprint "eagle-import:C0805")
      (libsource (lib "eagle-import") (part "C-EUC0805"))
    )
    (comp (ref "C84")
      (value "1uF")
      (footprint "eagle-import:C0805")
      (libsource (lib "eagle-import") (part "C-EUC0805"))
    )
    (comp (ref "C85")
      (value "10uF")
      (footprint "eagle-import:C0805")
      (libsource (lib "eagle-import") (part "C-EUC0805"))
    )
    (comp (ref "C86")
      (value "1uF")
      (footprint "eagle-import:C0805")
      (libsource (lib "eagle-import") (part "C-EUC0805"))
    )
    (comp (ref "C87")
      (value "10uF")
      (footprint "eagle-import:C0805")
      (libsource (lib "eagle-import") (part "C-EUC0805"))
    )
    (comp (ref "C88")
      (value "1uF")
      (footprint "eagle-import:C0805")
      (libsource (lib "eagle-import") (part "C-EUC0805"))
    )
    (comp (ref "C89")
      (value "10uF")
      (footprint "eagle-import:C0805")
      (libsource (lib "eagle-import") (part "C-EUC0805"))
    )
    (comp (ref "C90")
      (value "1uF")
      (footprint "eagle-import:C0805")
      (libsource (lib "eagle-import") (part "C-EUC0805"))
    )
    (comp (ref "C91")
      (value "10uF")
      (footprint "eagle-import:C0805")
      (libsource (lib "eagle-import") (part "C-EUC0805"))
    )
    (comp (ref "C92")
      (value "1uF")
      (footprint "eagle-import:C0805")
      (libsource (lib "eagle-import") (part "C-EUC0805"))
    )
    (comp (ref "C93")
      (value "10uF")
      (footprint "eagle-import:C0805")
      (libsource (lib "eagle-import") (part "C-EUC0805"))
    )
    (comp (ref "C94")
      (value "1uF")
      (footprint "eagle-import:C0805")
      (libsource (lib "eagle-import") (part "C-EUC0805"))
    )
    (comp (ref "C95")
      (value "10uF")
      (footprint "eagle-import:C0805")
      (libsource (lib "eagle-import") (part "C-EUC0805"))
    )
    (comp (ref "C96")
      (value "1uF")
      (footprint "eagle-import:C0805")
      (libsource (lib "eagle-import") (part "C-EUC0805"))
    )
    (comp (ref "C97")
      (value "10uF")
      (footprint "eagle-import:C0805")
      (libsource (lib "eagle-import") (part "C-EUC0805"))
    )
    (comp (ref "C98")
      (value "1uF")
      (footprint "eagle-import:C0805")
      (libsource (lib "eagle-import") (part "C-EUC0805"))
    )
    (comp (ref "C99")
      (value "10uF")
      (footprint "eagle-import:C0805")
      (libsource (lib "eagle-import") (part "C-EUC0805"))
    )
    (comp (ref "C100")
      (value "1uF")
      (footprint "eagle-import:C0805")
      (libsource (lib "eagle-import") (part "C-EUC0805"))
    )
    (comp (ref "C101")
      (value "10uF")
      (footprint "eagle-import:C0805")
      (libsource (lib "eagle-import") (part "C-EUC0805"))
    )
    (comp (ref "C102")
      (value "1uF")
      (footprint "eagle-import:C0805")
      (libsource (lib "eagle-import") (part "C-EUC0805"))
    )
    (comp (ref "C103")
      (value "10uF")
      (footprint "eagle-import:C0805")
      (libsource (lib "eagle-import") (part "C-EUC0805"))
    )
    (comp (ref "C104")
      (value "1uF")
      (footprint "eagle-import:C0805")
      (libsource (lib "eagle-import") (part "C-EUC0805"))
    )
    (comp (ref "C105")
      (value "10uF")
      (footprint "eagle-import:C0805")
      (libsource (lib "eagle-import") (part "C-EUC0805"))
    )
    (comp (ref "C106")
      (value "1uF")
      (footprint "eagle-import:C0805")
      (libsource (lib "eagle-import") (part "C-EUC0805"))
    )
    (comp (ref "C107")
      (value "10uF")
      (footprint "eagle-import:C0805")
      (libsource (lib "eagle-import") (part "C-EUC0805"))
    )
    (comp (ref "C108")
      (value "1uF")
      (footprint "eagle-import:C0805")
      (libsource (lib "eagle-import") (part "C-EUC0805"))
    )
    (comp (ref "C109")
      (value "10uF")
      (footprint "eagle-import:C0805")
      (libsource (lib "eagle-import") (part "C-EUC0805"))
    )
    (comp (ref "C110")
      (value "1uF")
      (footprint "eagle-import:C0805")
      (libsource (lib "eagle-import") (part "C-EUC0805"))
    )
    (comp (ref "C111")
      (value "10uF")
      (footprint "eagle-import:C0805")
      (libsource (lib "eagle-import") (part "C-EUC0805"))
    )
    (comp (ref "C112")
      (value "1uF")
      (footprint "eagle-import:C0805")
      (libsource (lib "eagle-import") (part "C-EUC0805"))
    )
    (comp (ref "C113")
      (value "10uF")
      (footprint "eagle-import:C0805")
      (libsource (lib "eagle-import") (part "C-EUC0805"))
    )
    (comp (ref "C114")
      (value "1uF")
      (footprint "eagle-import:C0805")
      (libsource (lib "eagle-import") (part "C-EUC0805"))
    )
    (comp (ref "C115")
      (value "10uF")
      (footprint "eagle-import:C0805")
      (libsource (lib "eagle-import") (part "C-EUC0805"))
    )
    (comp (ref "C116")
      (value "1uF")
      (footprint "eagle-import:C0805")
      (libsource (lib "eagle-import") (part "C-EUC0805"))
    )
    (comp (ref "C117")
      (value "10uF")
      (footprint "eagle-import:C0805")
      (libsource (lib "eagle-import") (part "C-EUC0805"))
    )
    (comp (ref "C118")
      (value "1uF")
      (footprint "eagle-import:C0805")
      (libsource (lib "eagle-import") (part "C-EUC0805"))
    )
    (comp (ref "C119")
      (value "10uF")
      (footprint "eagle-import:C0805")
      (libsource (lib "eagle-import") (part "C-EUC0805"))
    )
    (comp (ref "C120")
      (value "1uF")
      (footprint "eagle-import:C0805")
      (libsource (lib "eagle-import") (part "C-EUC0805"))
    )
    (comp (ref "C121")
      (value "10uF")
      (footprint "eagle-import:C0805")
      (libsource (lib "eagle-import") (part "C-EUC0805"))
    )
    (comp (ref "C122")
      (value "1uF")
      (footprint "eagle-import:C0805")
      (libsource (lib "eagle-import") (part "C-EUC0805"))
    )
    (comp (ref "C123")
      (value "10uF")
      (footprint "eagle-import:C0805")
      (libsource (lib "eagle-import") (part "C-EUC0805"))
    )
    (comp (ref "C124")
      (value "1uF")
      (footprint "eagle-import:C0805")
      (libsource (lib "eagle-import") (part "C-EUC0805"))
    )
    (comp (ref "C125")
      (value "10uF")
      (footprint "eagle-import:C0805")
      (libsource (lib "eagle-import") (part "C-EUC0805"))
    )
    (comp (ref "C126")
      (value "1uF")
      (footprint "eagle-import:C0805")
      (libsource (lib "eagle-import") (part "C-EUC0805"))
    )
    (comp (ref "C127")
      (value "10uF")
      (footprint "eagle-import:C0805")
      (libsource (lib "eagle-import") (part "C-EUC0805"))
    )
    (comp (ref "C128")
      (value "1uF")
      (footprint "eagle-import:C0805")
      (libsource (lib "eagle-import") (part "C-EUC0805"))
    )
    (comp (ref "C129")
      (value "10uF")
      (footprint "eagle-import:C0805")
      (libsource (lib "eagle-import") (part "C-EUC0805"))
    )
    (comp (ref "C130")
      (value "1uF")
      (footprint "eagle-import:C0805")
      (libsource (lib "eagle-import") (part "C-EUC0805"))
    )
    (comp (ref "C131")
      (value "10uF")
      (footprint "eagle-import:C0805")
      (libsource (lib "eagle-import") (part "C-EUC0805"))
    )
    (comp (ref "C132")
      (value "1uF")
      (footprint "eagle-import:C0805")
      (libsource (lib "eagle-import") (part "C-EUC0805"))
    )
    (comp (ref "C133")
      (value "10uF")
      (footprint "eagle-import:C0805")
      (libsource (lib "eagle-import") (part "C-EUC0805"))
    )
    (comp (ref "C134")
      (value "1uF")
      (footprint "eagle-import:C0805")
      (libsource (lib "eagle-import") (part "C-EUC0805"))
    )
    (comp (ref "C135")
      (value "10uF")
      (footprint "eagle-import:C0805")
      (libsource (lib "eagle-import") (part "C-EUC0805"))
    )
    (comp (ref "C136")
      (value "1uF")
      (footprint "eagle-import:C0805")
      (libsource (lib "eagle-import") (part "C-EUC0805"))
    )
    (comp (ref "C137")
      (value "10uF")
      (footprint "eagle-import:C0805")
      (libsource (lib "eagle-import") (part "C-EUC0805"))
    )
    (comp (ref "C138")
      (value "1uF")
      (footprint "eagle-import:C0805")
      (libsource (lib "eagle-import") (part "C-EUC0805"))
    )
    (comp (ref "C139")
      (value "10uF")
      (footprint "eagle-import:C0805")
      (libsource (lib "eagle-import") (part "C-EUC0805"))
    )
    (comp (ref "C140")
      (value "1uF")
      (footprint "eagle-import:C0805")
      (libsource (lib "eagle-import") (part "C-EUC0805"))
    )
    (comp (ref "C141")
      (value "10uF")
      (footprint "eagle-import:C0805")
      (libsource (lib "eagle-import") (part "C-EUC0805"))
    )
    (comp (ref "C142")
      (value "1uF")
      (footprint "eagle-import:C0805")
      (libsource (lib "eagle-import") (part "C-EUC0805"))
    )
    (comp (ref "C143")
      (value "10uF")
      (footprint "eagle-import:C0805")
      (libsource (lib "eagle-import") (part "C-EUC0805"))
    )
    (comp (ref "C144")
      (value "1uF")
      (footprint "eagle-import:C0805")
      (libsource (lib "eagle-import") (part "C-EUC0805"))
    )
    (comp (ref "C145")
      (value "10uF")
      (footprint "eagle-import:C0805")
      (libsource (lib "eagle-import") (part "C-EUC0805"))
    )
    (comp (ref "C146")
      (value "1uF")
      (footprint "eagle-import:C0805")
      (libsource (lib "eagle-import") (part "C-EUC0805"))
    )
    (comp (ref "C147")
      (value "10uF")
      (footprint "eagle-import:C0805")
      (libsource (lib "eagle-import") (part "C-EUC0805"))
    )
    (comp (ref "C148")
      (value "1uF")
      (footprint "eagle-import:C0805")
      (libsource (lib "eagle-import") (part "C-EUC0805"))
    )
    (comp (ref "C149")
      (value "10uF")
      (footprint "eagle-import:C0805")
      (libsource (lib "eagle-import") (part "C-EUC0805"))
    )
    (comp (ref "C150")
      (value "1uF")
      (footprint "eagle-import:C0805")
      (libsource (lib "eagle-import") (part "C-EUC0805"))
    )
    (comp (ref "C151")
      (value "10uF")
      (footprint "eagle-import:C0805")
      (libsource (lib "eagle-import") (part "C-EUC0805"))
    )
    (comp (ref "C152")
      (value "1uF")
      (footprint "eagle-import:C0805")
      (libsource (lib "eagle-import") (part "C-EUC0805"))
    )
    (comp (ref "C153")
      (value "10uF")
      (footprint "eagle-import:C0805")
      (libsource (lib "eagle-import") (part "C-EUC0805"))
    )
    (comp (ref "C154")
      (value "1uF")
      (footprint "eagle-import:C0805")
      (libsource (lib "eagle-import") (part "C-EUC0805"))
    )
    (comp (ref "C155")
      (value "10uF")
      (footprint "eagle-import:C0805")
      (libsource (lib "eagle-import") (part "C-EUC0805"))
    )
    (comp (ref "C156")
      (value "1uF")
      (footprint "eagle-import:C0805")
      (libsource (lib "eagle-import") (part "C-EUC0805"))
    )
    (comp (ref "C157")
      (value "10uF")
      (footprint "eagle-import:C0805")
      (libsource (lib "eagle-import") (part "C-EUC0805"))
    )
    (comp (ref "C158")
      (value "1uF")
      (footprint "eagle-import:C0805")
      (libsource (lib "eagle-import") (part "C-EUC0805"))
    )
    (comp (ref "C159")
      (value "10uF")
      (footprint "eagle-import:C0805")
      (libsource (lib "eagle-import") (part "C-EUC0805"))
    )
    (comp (ref "C160")
      (value "1uF")
      (footprint "eagle-import:C0805")
      (libsource (lib "eagle-import") (part "C-EUC0805"))
    )
    (comp (ref "C161")
      (value "10uF")
      (footprint "eagle-import:C0805")
      (libsource (lib "eagle-import") (part "C-EUC0805"))
    )
    (comp (ref "C162")
      (value "1uF")
      (footprint "eagle-import:C0805")
      (libsource (lib "eagle-import") (part "C-EUC0805"))
    )
    (comp (ref "C163")
      (value "10uF")
      (footprint "eagle-import:C0805")
      (libsource (lib "eagle-import") (part "C-EUC0805"))
    )
    (comp (ref "C164")
      (value "1uF")
      (footprint "eagle-import:C0805")
      (libsource (lib "eagle-import") (part "C-EUC0805"))
    )
    (comp (ref "C165")
      (value "10uF")
      (footprint "eagle-import:C0805")
      (libsource (lib "eagle-import") (part "C-EUC0805"))
    )
    (comp (ref "C166")
      (value "1uF")
      (footprint "eagle-import:C0805")
      (libsource (lib "eagle-import") (part "C-EUC0805"))
    )
    (comp (ref "C167")
      (value "10uF")
      (footprint "eagle-import:C0805")
      (libsource (lib "eagle-import") (part "C-EUC0805"))
    )
    (comp (ref "C168")
      (value "1uF")
      (footprint "eagle-import:C0805")
      (libsource (lib "eagle-import") (part "C-EUC0805"))
    )
    (comp (ref "C169")
      (value "10uF")
      (footprint "eagle-import:C0805")
      (libsource (lib "eagle-import") (part "C-EUC0805"))
    )
    (comp (ref "C170")
      (value "1uF")
      (footprint "eagle-import:C0805")
      (libsource (lib "eagle-import") (part "C-EUC0805"))
    )
    (comp (ref "C171")
      (value "10uF")
      (footprint "eagle-import:C0805")
      (libsource (lib "eagle-import") (part "C-EUC0805"))
    )
    (comp (ref "C172")
      (value "1uF")
      (footprint "eagle-import:C0805")
      (libsource (lib "eagle-import") (part "C-EUC0805"))
    )
    (comp (ref "C173")
      (value "10uF")
      (footprint "eagle-import:C0805")
      (libsource (lib "eagle-import") (part "C-EUC0805"))
    )
    (comp (ref "C174")
      (value "1uF")
      (footprint "eagle-import:C0805")
      (libsource (lib "eagle-import") (part "C-EUC0805"))
    )
    (comp (ref "C175")
      (value "10uF")
      (footprint "eagle-import:C0805")
      (libsource (lib "eagle-import") (part "C-EUC0805"))
    )
    (comp (ref "C176")
      (value "1uF")
      (footprint "eagle-import:C0805")
      (libsource (lib "eagle-import") (part "C-EUC0805"))
    )
    (comp (ref "C177")
      (value "10uF")
      (footprint "eagle-import:C0805")
      (libsource (lib "eagle-import") (part "C-EUC0805"))
    )
    (comp (ref "C178")
      (value "1uF")
      (footprint "eagle-import:C0805")
      (libsource (lib "eagle-import") (part "C-EUC0805"))
    )
    (comp (ref "C179")
      (value "10uF")
      (footprint "eagle-import:C0805")
      (libsource (lib "eagle-import") (part "C-EUC0805"))
    )
    (comp (ref "C180")
      (value "1uF")
      (footprint "eagle-import:C0805")
      (libsource (lib "eagle-import") (part "C-EUC0805"))
    )
    (comp (ref "C181")
      (value "10uF")
      (footprint "eagle-import:C0805")
      (libsource (lib "eagle-import") (part "C-EUC0805"))
    )
    (comp (ref "C182")
      (value "1uF")
      (footprint "eagle-import:C0805")
      (libsource (lib "eagle-import") (part "C-EUC0805"))
    )
    (comp (ref "C183")
      (value "10uF")
      (footprint "eagle-import:C0805")
      (libsource (lib "eagle-import") (part "C-EUC0805"))
    )
    (comp (ref "C184")
      (value "1uF")
      (footprint "eagle-import:C0805")
      (libsource (lib "eagle-import") (part "C-EUC0805"))
    )
    (comp (ref "C185")
      (value "10uF")
      (footprint "eagle-import:C0805")
      (libsource (lib "eagle-import") (part "C-EUC0805"))
    )
    (comp (ref "C186")
      (value "1uF")
      (footprint "eagle-import:C0805")
      (libsource (lib "eagle-import") (part "C-EUC0805"))
    )
    (comp (ref "C187")
      (value "10uF")
      (footprint "eagle-import:C0805")
      (libsource (lib "eagle-import") (part "C-EUC0805"))
    )
    (comp (ref "C188")
      (value "1uF")
      (footprint "eagle-import:C0805")
      (libsource (lib "eagle-import") (part "C-EUC0805"))
    )
    (comp (ref "C189")
      (value "10uF")
      (footprint "eagle-import:C0805")
      (libsource (lib "eagle-import") (part "C-EUC0805"))
    )
    (comp (ref "C190")
      (value "1uF")
      (footprint "eagle-import:C0805")
      (libsource (lib "eagle-import") (part "C-EUC0805"))
    )
    (comp (ref "C191")
      (value "10uF")
      (footprint "eagle-import:C0805")
      (libsource (lib "eagle-import") (part "C-EUC0805"))
    )
    (comp (ref "C192")
      (value "1uF")
      (footprint "eagle-import:C0805")
      (libsource (lib "eagle-import") (part "C-EUC0805"))
    )
    (comp (ref "R1")
      (value "2K")
      (footprint "eagle-import:R0805")
      (libsource (lib "eagle-import") (part "R-EU_R0805"))
    )
    (comp (ref "R2")
      (value "2K")
      (footprint "eagle-import:R0805")
      (libsource (lib "eagle-import") (part "R-EU_R0805"))
    )
    (comp (ref "R3")
      (value "2K")
      (footprint "eagle-import:R0805")
      (libsource (lib "eagle-import") (part "R-EU_R0805"))
    )
    (comp (ref "R4")
      (value "2K")
      (footprint "eagle-import:R0805")
      (libsource (lib "eagle-import") (part "R-EU_R0805"))
    )
    (comp (ref "R5")
      (value "2K")
      (footprint "eagle-import:R0805")
      (libsource (lib "eagle-import") (part "R-EU_R0805"))
    )
    (comp (ref "R6")
      (value "2K")
      (footprint "eagle-import:R0805")
      (libsource (lib "eagle-import") (part "R-EU_R0805"))
    )
    (comp (ref "R7")
      (value "2K")
      (footprint "eagle-import:R0805")
      (libsource (lib "eagle-import") (part "R-EU_R0805"))
    )
    (comp (ref "R8")
      (value "2K")
      (footprint "eagle-import:R0805")
      (libsource (lib "eagle-import") (part "R-EU_R0805"))
    )
    (comp (ref "R9")
      (value "2K")
      (footprint "eagle-import:R0805")
      (libsource (lib "eagle-import") (part "R-EU_R0805"))
    )
    (comp (ref "R10")
      (value "2K")
      (footprint "eagle-import:R0805")
      (libsource (lib "eagle-import") (part "R-EU_R0805"))
    )
    (comp (ref "R11")
      (value "2K")
      (footprint "eagle-import:R0805")
      (libsource (lib "eagle-import") (part "R-EU_R0805"))
    )
    (comp (ref "R12")
      (value "2K")
      (footprint "eagle-import:R0805")
      (libsource (lib "eagle-import") (part "R-EU_R0805"))
    )
    (comp (ref "R13")
      (value "2K")
      (footprint "eagle-import:R0805")
      (libsource (lib "eagle-import") (part "R-EU_R0805"))
    )
    (comp (ref "R14")
      (value "2K")
      (footprint "eagle-import:R0805")
      (libsource (lib "eagle-import") (part "R-EU_R0805"))
    )
    (comp (ref "R15")
      (value "2K")
      (footprint "eagle-import:R0805")
      (libsource (lib "eagle-import") (part "R-EU_R0805"))
    )
    (comp (ref "R16")
      (value "2K")
      (footprint "eagle-import:R0805")
      (libsource (lib "eagle-import") (part "R-EU_R0805"))
    )
    (comp (ref "R17")
      (value "2K")
      (footprint "eagle-import:R0805")
      (libsource (lib "eagle-import") (part "R-EU_R0805"))
    )
    (comp (ref "R18")
      (value "2K")
      (footprint "eagle-import:R0805")
      (libsource (lib "eagle-import") (part "R-EU_R0805"))
    )
    (comp (ref "R19")
      (value "2K")
      (footprint "eagle-import:R0805")
      (libsource (lib "eagle-import") (part "R-EU_R0805"))
    )
    (comp (ref "R20")
      (value "2K")
      (footprint "eagle-import:R0805")
      (libsource (lib "eagle-import") (part "R-EU_R0805"))
    )
    (comp (ref "R21")
      (value "2K")
      (footprint "eagle-import:R0805")
      (libsource (lib "eagle-import") (part "R-EU_R0805"))
    )
    (comp (ref "R22")
      (value "2K")
      (footprint "eagle-import:R0805")
      (libsource (lib "eagle-import") (part "R-EU_R0805"))
    )
    (comp (ref "R23")
      (value "2K")
      (footprint "eagle-import:R0805")
      (libsource (lib "eagle-import") (part "R-EU_R0805"))
    )
    (comp (ref "R24")
      (value "2K")
      (footprint "eagle-import:R0805")
      (libsource (lib "eagle-import") (part "R-EU_R0805"))
    )
    (comp (ref "R25")
      (value "2K")
      (footprint "eagle-import:R0805")
      (libsource (lib "eagle-import") (part "R-EU_R0805"))
    )
    (comp (ref "R26")
      (value "2K")
      (footprint "eagle-import:R0805")
      (libsource (lib "eagle-import") (part "R-EU_R0805"))
    )
    (comp (ref "R27")
      (value "2K")
      (footprint "eagle-import:R0805")
      (libsource (lib "eagle-import") (part "R-EU_R0805"))
    )
    (comp (ref "R28")
      (value "2K")
      (footprint "eagle-import:R0805")
      (libsource (lib "eagle-import") (part "R-EU_R0805"))
    )
    (comp (ref "R29")
      (value "2K")
      (footprint "eagle-import:R0805")
      (libsource (lib "eagle-import") (part "R-EU_R0805"))
    )
    (comp (ref "R30")
      (value "2K")
      (footprint "eagle-import:R0805")
      (libsource (lib "eagle-import") (part "R-EU_R0805"))
    )
    (comp (ref "R31")
      (value "2K")
      (footprint "eagle-import:R0805")
      (libsource (lib "eagle-import") (part "R-EU_R0805"))
    )
    (comp (ref "R32")
      (value "2K")
      (footprint "eagle-import:R0805")
      (libsource (lib "eagle-import") (part "R-EU_R0805"))
    )
    (comp (ref "R33")
      (value "2K")
      (footprint "eagle-import:R0805")
      (libsource (lib "eagle-import") (part "R-EU_R0805"))
    )
    (comp (ref "R34")
      (value "2K")
      (footprint "eagle-import:R0805")
      (libsource (lib "eagle-import") (part "R-EU_R0805"))
    )
    (comp (ref "R35")
      (value "2K")
      (footprint "eagle-import:R0805")
      (libsource (lib "eagle-import") (part "R-EU_R0805"))
    )
    (comp (ref "R36")
      (value "2K")
      (footprint "eagle-import:R0805")
      (libsource (lib "eagle-import") (part "R-EU_R0805"))
    )
    (comp (ref "R37")
      (value "2K")
      (footprint "eagle-import:R0805")
      (libsource (lib "eagle-import") (part "R-EU_R0805"))
    )
    (comp (ref "R38")
      (value "2K")
      (footprint "eagle-import:R0805")
      (libsource (lib "eagle-import") (part "R-EU_R0805"))
    )
    (comp (ref "R39")
      (value "2K")
      (footprint "eagle-import:R0805")
      (libsource (lib "eagle-import") (part "R-EU_R0805"))
    )
    (comp (ref "R40")
      (value "2K")
      (footprint "eagle-import:R0805")
      (libsource (lib "eagle-import") (part "R-EU_R0805"))
    )
    (comp (ref "R41")
      (value "2K")
      (footprint "eagle-import:R0805")
      (libsource (lib "eagle-import") (part "R-EU_R0805"))
    )
    (comp (ref "R42")
      (value "2K")
      (footprint "eagle-import:R0805")
      (libsource (lib "eagle-import") (part "R-EU_R0805"))
    )
    (comp (ref "R43")
      (value "2K")
      (footprint "eagle-import:R0805")
      (libsource (lib "eagle-import") (part "R-EU_R0805"))
    )
    (comp (ref "R44")
      (value "2K")
      (footprint "eagle-import:R0805")
      (libsource (lib "eagle-import") (part "R-EU_R0805"))
    )
    (comp (ref "R45")
      (value "2K")
      (footprint "eagle-import:R0805")
      (libsource (lib "eagle-import") (part "R-EU_R0805"))
    )
    (comp (ref "R46")
      (value "2K")
      (footprint "eagle-import:R0805")
      (libsource (lib "eagle-import") (part "R-EU_R0805"))
    )
    (comp (ref "R47")
      (value "2K")
      (footprint "eagle-import:R0805")
      (libsource (lib "eagle-import") (part "R-EU_R0805"))
    )
    (comp (ref "R48")
      (value "2K")
      (footprint "eagle-import:R0805")
      (libsource (lib "eagle-import") (part "R-EU_R0805"))
    )
    (comp (ref "R49")
      (value "2K")
      (footprint "eagle-import:R0805")
      (libsource (lib "eagle-import") (part "R-EU_R0805"))
    )
    (comp (ref "R50")
      (value "2K")
      (footprint "eagle-import:R0805")
      (libsource (lib "eagle-import") (part "R-EU_R0805"))
    )
    (comp (ref "R51")
      (value "2K")
      (footprint "eagle-import:R0805")
      (libsource (lib "eagle-import") (part "R-EU_R0805"))
    )
    (comp (ref "R52")
      (value "2K")
      (footprint "eagle-import:R0805")
      (libsource (lib "eagle-import") (part "R-EU_R0805"))
    )
    (comp (ref "R53")
      (value "2K")
      (footprint "eagle-import:R0805")
      (libsource (lib "eagle-import") (part "R-EU_R0805"))
    )
    (comp (ref "R54")
      (value "2K")
      (footprint "eagle-import:R0805")
      (libsource (lib "eagle-import") (part "R-EU_R0805"))
    )
    (comp (ref "R55")
      (value "2K")
      (footprint "eagle-import:R0805")
      (libsource (lib "eagle-import") (part "R-EU_R0805"))
    )
    (comp (ref "R56")
      (value "2K")
      (footprint "eagle-import:R0805")
      (libsource (lib "eagle-import") (part "R-EU_R0805"))
    )
    (comp (ref "R57")
      (value "2K")
      (footprint "eagle-import:R0805")
      (libsource (lib "eagle-import") (part "R-EU_R0805"))
    )
    (comp (ref "R58")
      (value "2K")
      (footprint "eagle-import:R0805")
      (libsource (lib "eagle-import") (part "R-EU_R0805"))
    )
    (comp (ref "R59")
      (value "2K")
      (footprint "eagle-import:R0805")
      (libsource (lib "eagle-import") (part "R-EU_R0805"))
    )
    (comp (ref "R60")
      (value "2K")
      (footprint "eagle-import:R0805")
      (libsource (lib "eagle-import") (part "R-EU_R0805"))
    )
    (comp (ref "R61")
      (value "2K")
      (footprint "eagle-import:R0805")
      (libsource (lib "eagle-import") (part "R-EU_R0805"))
    )
    (comp (ref "R62")
      (value "2K")
      (footprint "eagle-import:R0805")
      (libsource (lib "eagle-import") (part "R-EU_R0805"))
    )
    (comp (ref "R63")
      (value "2K")
      (footprint "eagle-import:R0805")
      (libsource (lib "eagle-import") (part "R-EU_R0805"))
    )
    (comp (ref "R64")
      (value "2K")
      (footprint "eagle-import:R0805")
      (libsource (lib "eagle-import") (part "R-EU_R0805"))
    )
    (comp (ref "R65")
      (value "2K")
      (footprint "eagle-import:R0805")
      (libsource (lib "eagle-import") (part "R-EU_R0805"))
    )
    (comp (ref "R66")
      (value "2K")
      (footprint "eagle-import:R0805")
      (libsource (lib "eagle-import") (part "R-EU_R0805"))
    )
    (comp (ref "R67")
      (value "2K")
      (footprint "eagle-import:R0805")
      (libsource (lib "eagle-import") (part "R-EU_R0805"))
    )
    (comp (ref "R68")
      (value "2K")
      (footprint "eagle-import:R0805")
      (libsource (lib "eagle-import") (part "R-EU_R0805"))
    )
    (comp (ref "R69")
      (value "2K")
      (footprint "eagle-import:R0805")
      (libsource (lib "eagle-import") (part "R-EU_R0805"))
    )
    (comp (ref "R70")
      (value "2K")
      (footprint "eagle-import:R0805")
      (libsource (lib "eagle-import") (part "R-EU_R0805"))
    )
    (comp (ref "R71")
      (value "2K")
      (footprint "eagle-import:R0805")
      (libsource (lib "eagle-import") (part "R-EU_R0805"))
    )
    (comp (ref "R72")
      (value "2K")
      (footprint "eagle-import:R0805")
      (libsource (lib "eagle-import") (part "R-EU_R0805"))
    )
    (comp (ref "R73")
      (value "2K")
      (footprint "eagle-import:R0805")
      (libsource (lib "eagle-import") (part "R-EU_R0805"))
    )
    (comp (ref "R74")
      (value "2K")
      (footprint "eagle-import:R0805")
      (libsource (lib "eagle-import") (part "R-EU_R0805"))
    )
    (comp (ref "R75")
      (value "2K")
      (footprint "eagle-import:R0805")
      (libsource (lib "eagle-import") (part "R-EU_R0805"))
    )
    (comp (ref "R76")
      (value "2K")
      (footprint "eagle-import:R0805")
      (libsource (lib "eagle-import") (part "R-EU_R0805"))
    )
    (comp (ref "R77")
      (value "2K")
      (footprint "eagle-import:R0805")
      (libsource (lib "eagle-import") (part "R-EU_R0805"))
    )
    (comp (ref "R78")
      (value "2K")
      (footprint "eagle-import:R0805")
      (libsource (lib "eagle-import") (part "R-EU_R0805"))
    )
    (comp (ref "R79")
      (value "2K")
      (footprint "eagle-import:R0805")
      (libsource (lib "eagle-import") (part "R-EU_R0805"))
    )
    (comp (ref "R80")
      (value "2K")
      (footprint "eagle-import:R0805")
      (libsource (lib "eagle-import") (part "R-EU_R0805"))
    )
    (comp (ref "R81")
      (value "2K")
      (footprint "eagle-import:R0805")
      (libsource (lib "eagle-import") (part "R-EU_R0805"))
    )
    (comp (ref "R82")
      (value "2K")
      (footprint "eagle-import:R0805")
      (libsource (lib "eagle-import") (part "R-EU_R0805"))
    )
    (comp (ref "R83")
      (value "2K")
      (footprint "eagle-import:R0805")
      (libsource (lib "eagle-import") (part "R-EU_R0805"))
    )
    (comp (ref "R84")
      (value "2K")
      (footprint "eagle-import:R0805")
      (libsource (lib "eagle-import") (part "R-EU_R0805"))
    )
    (comp (ref "R85")
      (value "2K")
      (footprint "eagle-import:R0805")
      (libsource (lib "eagle-import") (part "R-EU_R0805"))
    )
    (comp (ref "R86")
      (value "2K")
      (footprint "eagle-import:R0805")
      (libsource (lib "eagle-import") (part "R-EU_R0805"))
    )
    (comp (ref "R87")
      (value "2K")
      (footprint "eagle-import:R0805")
      (libsource (lib "eagle-import") (part "R-EU_R0805"))
    )
    (comp (ref "R88")
      (value "2K")
      (footprint "eagle-import:R0805")
      (libsource (lib "eagle-import") (part "R-EU_R0805"))
    )
    (comp (ref "R89")
      (value "2K")
      (footprint "eagle-import:R0805")
      (libsource (lib "eagle-import") (part "R-EU_R0805"))
    )
    (comp (ref "R90")
      (value "2K")
      (footprint "eagle-import:R0805")
      (libsource (lib "eagle-import") (part "R-EU_R0805"))
    )
    (comp (ref "R91")
      (value "2K")
      (footprint "eagle-import:R0805")
      (libsource (lib "eagle-import") (part "R-EU_R0805"))
    )
    (comp (ref "R92")
      (value "2K")
      (footprint "eagle-import:R0805")
      (libsource (lib "eagle-import") (part "R-EU_R0805"))
    )
    (comp (ref "R93")
      (value "2K")
      (footprint "eagle-import:R0805")
      (libsource (lib "eagle-import") (part "R-EU_R0805"))
    )
    (comp (ref "R94")
      (value "2K")
      (footprint "eagle-import:R0805")
      (libsource (lib "eagle-import") (part "R-EU_R0805"))
    )
    (comp (ref "R95")
      (value "2K")
      (footprint "eagle-import:R0805")
      (libsource (lib "eagle-import") (part "R-EU_R0805"))
    )
    (comp (ref "R96")
      (value "2K")
      (footprint "eagle-import:R0805")
      (libsource (lib "eagle-import") (part "R-EU_R0805"))
    )
    (comp (ref "SV1")
      (value "FE20-2")
      (footprint "eagle-import:FE20-2")
      (libsource (lib "eagle-import") (part "FE20-2"))
    )
    (comp (ref "SV2")
      (value "FE20-2")
      (footprint "eagle-import:FE20-2")
      (libsource (lib "eagle-import") (part "FE20-2"))
    )
    (comp (ref "SV3")
      (value "FE20-2")
      (footprint "eagle-import:FE20-2")
      (libsource (lib "eagle-import") (part "FE20-2"))
    )
    (comp (ref "SV4")
      (value "FE20-2")
      (footprint "eagle-import:FE20-2")
      (libsource (lib "eagle-import") (part "FE20-2"))
    )
    (comp (ref "SV5")
      (value "FE20-2")
      (footprint "eagle-import:FE20-2")
      (libsource (lib "eagle-import") (part "FE20-2"))
    )
    (comp (ref "SV6")
      (value "FE20-2")
      (footprint "eagle-import:FE20-2")
      (libsource (lib "eagle-import") (part "FE20-2"))
    )
    (comp (ref "SV7")
      (value "FE20-2")
      (footprint "eagle-import:FE20-2")
      (libsource (lib "eagle-import") (part "FE20-2"))
    )
    (comp (ref "SV8")
      (value "FE20-2")
      (footprint "eagle-import:FE20-2")
      (libsource (lib "eagle-import") (part "FE20-2"))
    )
    (comp (ref "U$1")
      (value "DUT0")
      (footprint "eagle-import:MGS")
      (libsource (lib "eagle-import") (part "MGS"))
    )
    (comp (ref "U$2")
      (value "DUT1")
      (footprint "eagle-import:MGS")
      (libsource (lib "eagle-import") (part "MGS"))
    )
    (comp (ref "U$3")
      (value "DUT2")
      (footprint "eagle-import:MGS")
      (libsource (lib "eagle-import") (part "MGS"))
    )
    (comp (ref "U$4")
      (value "DUT3")
      (footprint "eagle-import:MGS")
      (libsource (lib "eagle-import") (part "MGS"))
    )
    (comp (ref "U$5")
      (value "DUT4")
      (footprint "eagle-import:MGS")
      (libsource (lib "eagle-import") (part "MGS"))
    )
    (comp (ref "U$6")
      (value "DUT5")
      (footprint "eagle-import:MGS")
      (libsource (lib "eagle-import") (part "MGS"))
    )
    (comp (ref "U$7")
      (value "DUT6")
      (footprint "eagle-import:MGS")
      (libsource (lib "eagle-import") (part "MGS"))
    )
    (comp (ref "U$8")
      (value "DUT7")
      (footprint "eagle-import:MGS")
      (libsource (lib "eagle-import") (part "MGS"))
    )
    (comp (ref "U$9")
      (value "DUT8")
      (footprint "eagle-import:MGS")
      (libsource (lib "eagle-import") (part "MGS"))
    )
    (comp (ref "U$10")
      (value "DUT9")
      (footprint "eagle-import:MGS")
      (libsource (lib "eagle-import") (part "MGS"))
    )
    (comp (ref "U$11")
      (value "DUT10")
      (footprint "eagle-import:MGS")
      (libsource (lib "eagle-import") (part "MGS"))
    )
    (comp (ref "U$12")
      (value "DUT11")
      (footprint "eagle-import:MGS")
      (libsource (lib "eagle-import") (part "MGS"))
    )
    (comp (ref "U$13")
      (value "DUT12")
      (footprint "eagle-import:MGS")
      (libsource (lib "eagle-import") (part "MGS"))
    )
    (comp (ref "U$14")
      (value "DUT13")
      (footprint "eagle-import:MGS")
      (libsource (lib "eagle-import") (part "MGS"))
    )
    (comp (ref "U$15")
      (value "DUT14")
      (footprint "eagle-import:MGS")
      (libsource (lib "eagle-import") (part "MGS"))
    )
    (comp (ref "U$16")
      (value "DUT15")
      (footprint "eagle-import:MGS")
      (libsource (lib "eagle-import") (part "MGS"))
    )
    (comp (ref "U$17")
      (value "DUT32")
      (footprint "eagle-import:MGS")
      (libsource (lib "eagle-import") (part "MGS"))
    )
    (comp (ref "U$18")
      (value "DUT33")
      (footprint "eagle-import:MGS")
      (libsource (lib "eagle-import") (part "MGS"))
    )
    (comp (ref "U$19")
      (value "DUT34")
      (footprint "eagle-import:MGS")
      (libsource (lib "eagle-import") (part "MGS"))
    )
    (comp (ref "U$20")
      (value "DUT35")
      (footprint "eagle-import:MGS")
      (libsource (lib "eagle-import") (part "MGS"))
    )
    (comp (ref "U$21")
      (value "DUT36")
      (footprint "eagle-import:MGS")
      (libsource (lib "eagle-import") (part "MGS"))
    )
    (comp (ref "U$22")
      (value "DUT37")
      (footprint "eagle-import:MGS")
      (libsource (lib "eagle-import") (part "MGS"))
    )
    (comp (ref "U$23")
      (value "DUT38")
      (footprint "eagle-import:MGS")
      (libsource (lib "eagle-import") (part "MGS"))
    )
    (comp (ref "U$24")
      (value "DUT39")
      (footprint "eagle-import:MGS")
      (libsource (lib "eagle-import") (part "MGS"))
    )
    (comp (ref "U$25")
      (value "DUT40")
      (footprint "eagle-import:MGS")
      (libsource (lib "eagle-import") (part "MGS"))
    )
    (comp (ref "U$26")
      (value "DUT41")
      (footprint "eagle-import:MGS")
      (libsource (lib "eagle-import") (part "MGS"))
    )
    (comp (ref "U$27")
      (value "DUT42")
      (footprint "eagle-import:MGS")
      (libsource (lib "eagle-import") (part "MGS"))
    )
    (comp (ref "U$28")
      (value "DUT43")
      (footprint "eagle-import:MGS")
      (libsource (lib "eagle-import") (part "MGS"))
    )
    (comp (ref "U$29")
      (value "DUT44")
      (footprint "eagle-import:MGS")
      (libsource (lib "eagle-import") (part "MGS"))
    )
    (comp (ref "U$30")
      (value "DUT45")
      (footprint "eagle-import:MGS")
      (libsource (lib "eagle-import") (part "MGS"))
    )
    (comp (ref "U$31")
      (value "DUT46")
      (footprint "eagle-import:MGS")
      (libsource (lib "eagle-import") (part "MGS"))
    )
    (comp (ref "U$32")
      (value "DUT47")
      (footprint "eagle-import:MGS")
      (libsource (lib "eagle-import") (part "MGS"))
    )
    (comp (ref "U$33")
      (value "DUT64")
      (footprint "eagle-import:MGS")
      (libsource (lib "eagle-import") (part "MGS"))
    )
    (comp (ref "U$34")
      (value "DUT65")
      (footprint "eagle-import:MGS")
      (libsource (lib "eagle-import") (part "MGS"))
    )
    (comp (ref "U$35")
      (value "DUT66")
      (footprint "eagle-import:MGS")
      (libsource (lib "eagle-import") (part "MGS"))
    )
    (comp (ref "U$36")
      (value "DUT67")
      (footprint "eagle-import:MGS")
      (libsource (lib "eagle-import") (part "MGS"))
    )
    (comp (ref "U$37")
      (value "DUT68")
      (footprint "eagle-import:MGS")
      (libsource (lib "eagle-import") (part "MGS"))
    )
    (comp (ref "U$38")
      (value "DUT69")
      (footprint "eagle-import:MGS")
      (libsource (lib "eagle-import") (part "MGS"))
    )
    (comp (ref "U$39")
      (value "DUT70")
      (footprint "eagle-import:MGS")
      (libsource (lib "eagle-import") (part "MGS"))
    )
    (comp (ref "U$40")
      (value "DUT71")
      (footprint "eagle-import:MGS")
      (libsource (lib "eagle-import") (part "MGS"))
    )
    (comp (ref "U$41")
      (value "DUT72")
      (footprint "eagle-import:MGS")
      (libsource (lib "eagle-import") (part "MGS"))
    )
    (comp (ref "U$42")
      (value "DUT73")
      (footprint "eagle-import:MGS")
      (libsource (lib "eagle-import") (part "MGS"))
    )
    (comp (ref "U$43")
      (value "DUT74")
      (footprint "eagle-import:MGS")
      (libsource (lib "eagle-import") (part "MGS"))
    )
    (comp (ref "U$44")
      (value "DUT75")
      (footprint "eagle-import:MGS")
      (libsource (lib "eagle-import") (part "MGS"))
    )
    (comp (ref "U$45")
      (value "DUT76")
      (footprint "eagle-import:MGS")
      (libsource (lib "eagle-import") (part "MGS"))
    )
    (comp (ref "U$46")
      (value "DUT77")
      (footprint "eagle-import:MGS")
      (libsource (lib "eagle-import") (part "MGS"))
    )
    (comp (ref "U$47")
      (value "DUT78")
      (footprint "eagle-import:MGS")
      (libsource (lib "eagle-import") (part "MGS"))
    )
    (comp (ref "U$48")
      (value "DUT79")
      (footprint "eagle-import:MGS")
      (libsource (lib "eagle-import") (part "MGS"))
    )
    (comp (ref "U$49")
      (value "DUT16")
      (footprint "eagle-import:MGS")
      (libsource (lib "eagle-import") (part "MGS"))
    )
    (comp (ref "U$50")
      (value "DUT17")
      (footprint "eagle-import:MGS")
      (libsource (lib "eagle-import") (part "MGS"))
    )
    (comp (ref "U$51")
      (value "DUT18")
      (footprint "eagle-import:MGS")
      (libsource (lib "eagle-import") (part "MGS"))
    )
    (comp (ref "U$52")
      (value "DUT19")
      (footprint "eagle-import:MGS")
      (libsource (lib "eagle-import") (part "MGS"))
    )
    (comp (ref "U$53")
      (value "DUT20")
      (footprint "eagle-import:MGS")
      (libsource (lib "eagle-import") (part "MGS"))
    )
    (comp (ref "U$54")
      (value "DUT21")
      (footprint "eagle-import:MGS")
      (libsource (lib "eagle-import") (part "MGS"))
    )
    (comp (ref "U$55")
      (value "DUT22")
      (footprint "eagle-import:MGS")
      (libsource (lib "eagle-import") (part "MGS"))
    )
    (comp (ref "U$56")
      (value "DUT23")
      (footprint "eagle-import:MGS")
      (libsource (lib "eagle-import") (part "MGS"))
    )
    (comp (ref "U$57")
      (value "DUT24")
      (footprint "eagle-import:MGS")
      (libsource (lib "eagle-import") (part "MGS"))
    )
    (comp (ref "U$58")
      (value "DUT25")
      (footprint "eagle-import:MGS")
      (libsource (lib "eagle-import") (part "MGS"))
    )
    (comp (ref "U$59")
      (value "DUT26")
      (footprint "eagle-import:MGS")
      (libsource (lib "eagle-import") (part "MGS"))
    )
    (comp (ref "U$60")
      (value "DUT27")
      (footprint "eagle-import:MGS")
      (libsource (lib "eagle-import") (part "MGS"))
    )
    (comp (ref "U$61")
      (value "DUT28")
      (footprint "eagle-import:MGS")
      (libsource (lib "eagle-import") (part "MGS"))
    )
    (comp (ref "U$62")
      (value "DUT29")
      (footprint "eagle-import:MGS")
      (libsource (lib "eagle-import") (part "MGS"))
    )
    (comp (ref "U$63")
      (value "DUT30")
      (footprint "eagle-import:MGS")
      (libsource (lib "eagle-import") (part "MGS"))
    )
    (comp (ref "U$64")
      (value "DUT31")
      (footprint "eagle-import:MGS")
      (libsource (lib "eagle-import") (part "MGS"))
    )
    (comp (ref "U$65")
      (value "DUT48")
      (footprint "eagle-import:MGS")
      (libsource (lib "eagle-import") (part "MGS"))
    )
    (comp (ref "U$66")
      (value "DUT49")
      (footprint "eagle-import:MGS")
      (libsource (lib "eagle-import") (part "MGS"))
    )
    (comp (ref "U$67")
      (value "DUT50")
      (footprint "eagle-import:MGS")
      (libsource (lib "eagle-import") (part "MGS"))
    )
    (comp (ref "U$68")
      (value "DUT51")
      (footprint "eagle-import:MGS")
      (libsource (lib "eagle-import") (part "MGS"))
    )
    (comp (ref "U$69")
      (value "DUT52")
      (footprint "eagle-import:MGS")
      (libsource (lib "eagle-import") (part "MGS"))
    )
    (comp (ref "U$70")
      (value "DUT53")
      (footprint "eagle-import:MGS")
      (libsource (lib "eagle-import") (part "MGS"))
    )
    (comp (ref "U$71")
      (value "DUT54")
      (footprint "eagle-import:MGS")
      (libsource (lib "eagle-import") (part "MGS"))
    )
    (comp (ref "U$72")
      (value "DUT55")
      (footprint "eagle-import:MGS")
      (libsource (lib "eagle-import") (part "MGS"))
    )
    (comp (ref "U$73")
      (value "DUT56")
      (footprint "eagle-import:MGS")
      (libsource (lib "eagle-import") (part "MGS"))
    )
    (comp (ref "U$74")
      (value "DUT57")
      (footprint "eagle-import:MGS")
      (libsource (lib "eagle-import") (part "MGS"))
    )
    (comp (ref "U$75")
      (value "DUT58")
      (footprint "eagle-import:MGS")
      (libsource (lib "eagle-import") (part "MGS"))
    )
    (comp (ref "U$76")
      (value "DUT59")
      (footprint "eagle-import:MGS")
      (libsource (lib "eagle-import") (part "MGS"))
    )
    (comp (ref "U$77")
      (value "DUT60")
      (footprint "eagle-import:MGS")
      (libsource (lib "eagle-import") (part "MGS"))
    )
    (comp (ref "U$78")
      (value "DUT61")
      (footprint "eagle-import:MGS")
      (libsource (lib "eagle-import") (part "MGS"))
    )
    (comp (ref "U$79")
      (value "DUT62")
      (footprint "eagle-import:MGS")
      (libsource (lib "eagle-import") (part "MGS"))
    )
    (comp (ref "U$80")
      (value "DUT63")
      (footprint "eagle-import:MGS")
      (libsource (lib "eagle-import") (part "MGS"))
    )
    (comp (ref "U$81")
      (value "DUT80")
      (footprint "eagle-import:MGS")
      (libsource (lib "eagle-import") (part "MGS"))
    )
    (comp (ref "U$82")
      (value "DUT81")
      (footprint "eagle-import:MGS")
      (libsource (lib "eagle-import") (part "MGS"))
    )
    (comp (ref "U$83")
      (value "DUT82")
      (footprint "eagle-import:MGS")
      (libsource (lib "eagle-import") (part "MGS"))
    )
    (comp (ref "U$84")
      (value "DUT83")
      (footprint "eagle-import:MGS")
      (libsource (lib "eagle-import") (part "MGS"))
    )
    (comp (ref "U$85")
      (value "DUT84")
      (footprint "eagle-import:MGS")
      (libsource (lib "eagle-import") (part "MGS"))
    )
    (comp (ref "U$86")
      (value "DUT85")
      (footprint "eagle-import:MGS")
      (libsource (lib "eagle-import") (part "MGS"))
    )
    (comp (ref "U$87")
      (value "DUT86")
      (footprint "eagle-import:MGS")
      (libsource (lib "eagle-import") (part "MGS"))
    )
    (comp (ref "U$88")
      (value "DUT87")
      (footprint "eagle-import:MGS")
      (libsource (lib "eagle-import") (part "MGS"))
    )
    (comp (ref "U$89")
      (value "DUT88")
      (footprint "eagle-import:MGS")
      (libsource (lib "eagle-import") (part "MGS"))
    )
    (comp (ref "U$90")
      (value "DUT89")
      (footprint "eagle-import:MGS")
      (libsource (lib "eagle-import") (part "MGS"))
    )
    (comp (ref "U$91")
      (value "DUT90")
      (footprint "eagle-import:MGS")
      (libsource (lib "eagle-import") (part "MGS"))
    )
    (comp (ref "U$92")
      (value "DUT91")
      (footprint "eagle-import:MGS")
      (libsource (lib "eagle-import") (part "MGS"))
    )
    (comp (ref "U$93")
      (value "DUT92")
      (footprint "eagle-import:MGS")
      (libsource (lib "eagle-import") (part "MGS"))
    )
    (comp (ref "U$94")
      (value "DUT93")
      (footprint "eagle-import:MGS")
      (libsource (lib "eagle-import") (part "MGS"))
    )
    (comp (ref "U$95")
      (value "DUT94")
      (footprint "eagle-import:MGS")
      (libsource (lib "eagle-import") (part "MGS"))
    )
    (comp (ref "U$96")
      (value "DUT95")
      (footprint "eagle-import:MGS")
      (libsource (lib "eagle-import") (part "MGS"))
    )
    (comp (ref "U1")
      (value "DPS310XTSA1")
      (footprint "eagle-import:PG-VLGA-8-1_INF")
      (fields (field (name "COPYRIGHT") "Copyright (C) 2018 Accelerated Designs. All rights reserved"))
      (libsource (lib "eagle-import") (part "DPS310XTSA1"))
    )
    (comp (ref "U2")
      (value "SENSIRION_SHT25SENSIRION_SHT25_0_0")
      (footprint "eagle-import:SENSIRION_SHT25_0")
      (fields
        (field (name "DIGIKEY_PART_NUMBER") "1649-1008-1-ND")
        (field (name "MF") "Sensirion")
        (field (name "MOUSER_PART_NUMBER") "403-SHT25")
      )
      (libsource (lib "eagle-import") (part "SENSIRION_SHT25SENSIRION_SHT25_0_0"))
    )
    (comp (ref "U3")
      (value "DPS310XTSA1")
      (footprint "eagle-import:PG-VLGA-8-1_INF")
      (fields (field (name "COPYRIGHT") "Copyright (C) 2018 Accelerated Designs. All rights reserved"))
      (libsource (lib "eagle-import") (part "DPS310XTSA1"))
    )
    (comp (ref "U4")
      (value "SENSIRION_SHT25SENSIRION_SHT25_0_0")
      (footprint "eagle-import:SENSIRION_SHT25_0")
      (fields
        (field (name "DIGIKEY_PART_NUMBER") "1649-1008-1-ND")
        (field (name "MF") "Sensirion")
        (field (name "MOUSER_PART_NUMBER") "403-SHT25")
      )
      (libsource (lib "eagle-import") (part "SENSIRION_SHT25SENSIRION_SHT25_0_0"))
    )
    (comp (ref "U5")
      (value "DPS310XTSA1")
      (footprint "eagle-import:PG-VLGA-8-1_INF")
      (fields (field (name "COPYRIGHT") "Copyright (C) 2018 Accelerated Designs. All rights reserved"))
      (libsource (lib "eagle-import") (part "DPS310XTSA1"))
    )
    (comp (ref "U6")
      (value "SENSIRION_SHT25SENSIRION_SHT25_0_0")
      (footprint "eagle-import:SENSIRION_SHT25_0")
      (fields
        (field (name "DIGIKEY_PART_NUMBER") "1649-1008-1-ND")
        (field (name "MF") "Sensirion")
        (field (name "MOUSER_PART_NUMBER") "403-SHT25")
      )
      (libsource (lib "eagle-import") (part "SENSIRION_SHT25SENSIRION_SHT25_0_0"))
    )
  )
  (nets
    (net (code "1") (name "+12V") (class "Default")
      (node (ref "C1") (pin "1") (pinfunction "1_1") (pintype "passive"))
      (node (ref "C101") (pin "1") (pinfunction "1_1") (pintype "passive"))
      (node (ref "C103") (pin "1") (pinfunction "1_1") (pintype "passive"))
      (node (ref "C105") (pin "1") (pinfunction "1_1") (pintype "passive"))
      (node (ref "C107") (pin "1") (pinfunction "1_1") (pintype "passive"))
      (node (ref "C109") (pin "1") (pinfunction "1_1") (pintype "passive"))
      (node (ref "C11") (pin "1") (pinfunction "1_1") (pintype "passive"))
      (node (ref "C111") (pin "1") (pinfunction "1_1") (pintype "passive"))
      (node (ref "C113") (pin "1") (pinfunction "1_1") (pintype "passive"))
      (node (ref "C115") (pin "1") (pinfunction "1_1") (pintype "passive"))
      (node (ref "C117") (pin "1") (pinfunction "1_1") (pintype "passive"))
      (node (ref "C119") (pin "1") (pinfunction "1_1") (pintype "passive"))
      (node (ref "C121") (pin "1") (pinfunction "1_1") (pintype "passive"))
      (node (ref "C123") (pin "1") (pinfunction "1_1") (pintype "passive"))
      (node (ref "C125") (pin "1") (pinfunction "1_1") (pintype "passive"))
      (node (ref "C127") (pin "1") (pinfunction "1_1") (pintype "passive"))
      (node (ref "C129") (pin "1") (pinfunction "1_1") (pintype "passive"))
      (node (ref "C13") (pin "1") (pinfunction "1_1") (pintype "passive"))
      (node (ref "C131") (pin "1") (pinfunction "1_1") (pintype "passive"))
      (node (ref "C133") (pin "1") (pinfunction "1_1") (pintype "passive"))
      (node (ref "C135") (pin "1") (pinfunction "1_1") (pintype "passive"))
      (node (ref "C137") (pin "1") (pinfunction "1_1") (pintype "passive"))
      (node (ref "C139") (pin "1") (pinfunction "1_1") (pintype "passive"))
      (node (ref "C141") (pin "1") (pinfunction "1_1") (pintype "passive"))
      (node (ref "C143") (pin "1") (pinfunction "1_1") (pintype "passive"))
      (node (ref "C145") (pin "1") (pinfunction "1_1") (pintype "passive"))
      (node (ref "C147") (pin "1") (pinfunction "1_1") (pintype "passive"))
      (node (ref "C149") (pin "1") (pinfunction "1_1") (pintype "passive"))
      (node (ref "C15") (pin "1") (pinfunction "1_1") (pintype "passive"))
      (node (ref "C151") (pin "1") (pinfunction "1_1") (pintype "passive"))
      (node (ref "C153") (pin "1") (pinfunction "1_1") (pintype "passive"))
      (node (ref "C155") (pin "1") (pinfunction "1_1") (pintype "passive"))
      (node (ref "C157") (pin "1") (pinfunction "1_1") (pintype "passive"))
      (node (ref "C159") (pin "1") (pinfunction "1_1") (pintype "passive"))
      (node (ref "C161") (pin "1") (pinfunction "1_1") (pintype "passive"))
      (node (ref "C163") (pin "1") (pinfunction "1_1") (pintype "passive"))
      (node (ref "C165") (pin "1") (pinfunction "1_1") (pintype "passive"))
      (node (ref "C167") (pin "1") (pinfunction "1_1") (pintype "passive"))
      (node (ref "C169") (pin "1") (pinfunction "1_1") (pintype "passive"))
      (node (ref "C17") (pin "1") (pinfunction "1_1") (pintype "passive"))
      (node (ref "C171") (pin "1") (pinfunction "1_1") (pintype "passive"))
      (node (ref "C173") (pin "1") (pinfunction "1_1") (pintype "passive"))
      (node (ref "C175") (pin "1") (pinfunction "1_1") (pintype "passive"))
      (node (ref "C177") (pin "1") (pinfunction "1_1") (pintype "passive"))
      (node (ref "C179") (pin "1") (pinfunction "1_1") (pintype "passive"))
      (node (ref "C181") (pin "1") (pinfunction "1_1") (pintype "passive"))
      (node (ref "C183") (pin "1") (pinfunction "1_1") (pintype "passive"))
      (node (ref "C185") (pin "1") (pinfunction "1_1") (pintype "passive"))
      (node (ref "C187") (pin "1") (pinfunction "1_1") (pintype "passive"))
      (node (ref "C189") (pin "1") (pinfunction "1_1") (pintype "passive"))
      (node (ref "C19") (pin "1") (pinfunction "1_1") (pintype "passive"))
      (node (ref "C191") (pin "1") (pinfunction "1_1") (pintype "passive"))
      (node (ref "C21") (pin "1") (pinfunction "1_1") (pintype "passive"))
      (node (ref "C23") (pin "1") (pinfunction "1_1") (pintype "passive"))
      (node (ref "C25") (pin "1") (pinfunction "1_1") (pintype "passive"))
      (node (ref "C27") (pin "1") (pinfunction "1_1") (pintype "passive"))
      (node (ref "C29") (pin "1") (pinfunction "1_1") (pintype "passive"))
      (node (ref "C3") (pin "1") (pinfunction "1_1") (pintype "passive"))
      (node (ref "C31") (pin "1") (pinfunction "1_1") (pintype "passive"))
      (node (ref "C33") (pin "1") (pinfunction "1_1") (pintype "passive"))
      (node (ref "C35") (pin "1") (pinfunction "1_1") (pintype "passive"))
      (node (ref "C37") (pin "1") (pinfunction "1_1") (pintype "passive"))
      (node (ref "C39") (pin "1") (pinfunction "1_1") (pintype "passive"))
      (node (ref "C41") (pin "1") (pinfunction "1_1") (pintype "passive"))
      (node (ref "C43") (pin "1") (pinfunction "1_1") (pintype "passive"))
      (node (ref "C45") (pin "1") (pinfunction "1_1") (pintype "passive"))
      (node (ref "C47") (pin "1") (pinfunction "1_1") (pintype "passive"))
      (node (ref "C49") (pin "1") (pinfunction "1_1") (pintype "passive"))
      (node (ref "C5") (pin "1") (pinfunction "1_1") (pintype "passive"))
      (node (ref "C51") (pin "1") (pinfunction "1_1") (pintype "passive"))
      (node (ref "C53") (pin "1") (pinfunction "1_1") (pintype "passive"))
      (node (ref "C55") (pin "1") (pinfunction "1_1") (pintype "passive"))
      (node (ref "C57") (pin "1") (pinfunction "1_1") (pintype "passive"))
      (node (ref "C59") (pin "1") (pinfunction "1_1") (pintype "passive"))
      (node (ref "C61") (pin "1") (pinfunction "1_1") (pintype "passive"))
      (node (ref "C63") (pin "1") (pinfunction "1_1") (pintype "passive"))
      (node (ref "C65") (pin "1") (pinfunction "1_1") (pintype "passive"))
      (node (ref "C67") (pin "1") (pinfunction "1_1") (pintype "passive"))
      (node (ref "C69") (pin "1") (pinfunction "1_1") (pintype "passive"))
      (node (ref "C7") (pin "1") (pinfunction "1_1") (pintype "passive"))
      (node (ref "C71") (pin "1") (pinfunction "1_1") (pintype "passive"))
      (node (ref "C73") (pin "1") (pinfunction "1_1") (pintype "passive"))
      (node (ref "C75") (pin "1") (pinfunction "1_1") (pintype "passive"))
      (node (ref "C77") (pin "1") (pinfunction "1_1") (pintype "passive"))
      (node (ref "C79") (pin "1") (pinfunction "1_1") (pintype "passive"))
      (node (ref "C81") (pin "1") (pinfunction "1_1") (pintype "passive"))
      (node (ref "C83") (pin "1") (pinfunction "1_1") (pintype "passive"))
      (node (ref "C85") (pin "1") (pinfunction "1_1") (pintype "passive"))
      (node (ref "C87") (pin "1") (pinfunction "1_1") (pintype "passive"))
      (node (ref "C89") (pin "1") (pinfunction "1_1") (pintype "passive"))
      (node (ref "C9") (pin "1") (pinfunction "1_1") (pintype "passive"))
      (node (ref "C91") (pin "1") (pinfunction "1_1") (pintype "passive"))
      (node (ref "C93") (pin "1") (pinfunction "1_1") (pintype "passive"))
      (node (ref "C95") (pin "1") (pinfunction "1_1") (pintype "passive"))
      (node (ref "C97") (pin "1") (pinfunction "1_1") (pintype "passive"))
      (node (ref "C99") (pin "1") (pinfunction "1_1") (pintype "passive"))
      (node (ref "SV1") (pin "1") (pinfunction "1_1") (pintype "passive"))
      (node (ref "SV1") (pin "2") (pinfunction "2_2") (pintype "passive"))
      (node (ref "SV1") (pin "3") (pinfunction "3_3") (pintype "passive"))
      (node (ref "SV1") (pin "4") (pinfunction "4_4") (pintype "passive"))
      (node (ref "SV8") (pin "37") (pinfunction "37_37") (pintype "passive"))
      (node (ref "SV8") (pin "38") (pinfunction "38_38") (pintype "passive"))
      (node (ref "SV8") (pin "39") (pinfunction "39_39") (pintype "passive"))
      (node (ref "SV8") (pin "40") (pinfunction "40_40") (pintype "passive"))
      (node (ref "U$1") (pin "3") (pinfunction "VDDH_3") (pintype "bidirectional"))
      (node (ref "U$10") (pin "3") (pinfunction "VDDH_3") (pintype "bidirectional"))
      (node (ref "U$11") (pin "3") (pinfunction "VDDH_3") (pintype "bidirectional"))
      (node (ref "U$12") (pin "3") (pinfunction "VDDH_3") (pintype "bidirectional"))
      (node (ref "U$13") (pin "3") (pinfunction "VDDH_3") (pintype "bidirectional"))
      (node (ref "U$14") (pin "3") (pinfunction "VDDH_3") (pintype "bidirectional"))
      (node (ref "U$15") (pin "3") (pinfunction "VDDH_3") (pintype "bidirectional"))
      (node (ref "U$16") (pin "3") (pinfunction "VDDH_3") (pintype "bidirectional"))
      (node (ref "U$17") (pin "3") (pinfunction "VDDH_3") (pintype "bidirectional"))
      (node (ref "U$18") (pin "3") (pinfunction "VDDH_3") (pintype "bidirectional"))
      (node (ref "U$19") (pin "3") (pinfunction "VDDH_3") (pintype "bidirectional"))
      (node (ref "U$2") (pin "3") (pinfunction "VDDH_3") (pintype "bidirectional"))
      (node (ref "U$20") (pin "3") (pinfunction "VDDH_3") (pintype "bidirectional"))
      (node (ref "U$21") (pin "3") (pinfunction "VDDH_3") (pintype "bidirectional"))
      (node (ref "U$22") (pin "3") (pinfunction "VDDH_3") (pintype "bidirectional"))
      (node (ref "U$23") (pin "3") (pinfunction "VDDH_3") (pintype "bidirectional"))
      (node (ref "U$24") (pin "3") (pinfunction "VDDH_3") (pintype "bidirectional"))
      (node (ref "U$25") (pin "3") (pinfunction "VDDH_3") (pintype "bidirectional"))
      (node (ref "U$26") (pin "3") (pinfunction "VDDH_3") (pintype "bidirectional"))
      (node (ref "U$27") (pin "3") (pinfunction "VDDH_3") (pintype "bidirectional"))
      (node (ref "U$28") (pin "3") (pinfunction "VDDH_3") (pintype "bidirectional"))
      (node (ref "U$29") (pin "3") (pinfunction "VDDH_3") (pintype "bidirectional"))
      (node (ref "U$3") (pin "3") (pinfunction "VDDH_3") (pintype "bidirectional"))
      (node (ref "U$30") (pin "3") (pinfunction "VDDH_3") (pintype "bidirectional"))
      (node (ref "U$31") (pin "3") (pinfunction "VDDH_3") (pintype "bidirectional"))
      (node (ref "U$32") (pin "3") (pinfunction "VDDH_3") (pintype "bidirectional"))
      (node (ref "U$33") (pin "3") (pinfunction "VDDH_3") (pintype "bidirectional"))
      (node (ref "U$34") (pin "3") (pinfunction "VDDH_3") (pintype "bidirectional"))
      (node (ref "U$35") (pin "3") (pinfunction "VDDH_3") (pintype "bidirectional"))
      (node (ref "U$36") (pin "3") (pinfunction "VDDH_3") (pintype "bidirectional"))
      (node (ref "U$37") (pin "3") (pinfunction "VDDH_3") (pintype "bidirectional"))
      (node (ref "U$38") (pin "3") (pinfunction "VDDH_3") (pintype "bidirectional"))
      (node (ref "U$39") (pin "3") (pinfunction "VDDH_3") (pintype "bidirectional"))
      (node (ref "U$4") (pin "3") (pinfunction "VDDH_3") (pintype "bidirectional"))
      (node (ref "U$40") (pin "3") (pinfunction "VDDH_3") (pintype "bidirectional"))
      (node (ref "U$41") (pin "3") (pinfunction "VDDH_3") (pintype "bidirectional"))
      (node (ref "U$42") (pin "3") (pinfunction "VDDH_3") (pintype "bidirectional"))
      (node (ref "U$43") (pin "3") (pinfunction "VDDH_3") (pintype "bidirectional"))
      (node (ref "U$44") (pin "3") (pinfunction "VDDH_3") (pintype "bidirectional"))
      (node (ref "U$45") (pin "3") (pinfunction "VDDH_3") (pintype "bidirectional"))
      (node (ref "U$46") (pin "3") (pinfunction "VDDH_3") (pintype "bidirectional"))
      (node (ref "U$47") (pin "3") (pinfunction "VDDH_3") (pintype "bidirectional"))
      (node (ref "U$48") (pin "3") (pinfunction "VDDH_3") (pintype "bidirectional"))
      (node (ref "U$49") (pin "3") (pinfunction "VDDH_3") (pintype "bidirectional"))
      (node (ref "U$5") (pin "3") (pinfunction "VDDH_3") (pintype "bidirectional"))
      (node (ref "U$50") (pin "3") (pinfunction "VDDH_3") (pintype "bidirectional"))
      (node (ref "U$51") (pin "3") (pinfunction "VDDH_3") (pintype "bidirectional"))
      (node (ref "U$52") (pin "3") (pinfunction "VDDH_3") (pintype "bidirectional"))
      (node (ref "U$53") (pin "3") (pinfunction "VDDH_3") (pintype "bidirectional"))
      (node (ref "U$54") (pin "3") (pinfunction "VDDH_3") (pintype "bidirectional"))
      (node (ref "U$55") (pin "3") (pinfunction "VDDH_3") (pintype "bidirectional"))
      (node (ref "U$56") (pin "3") (pinfunction "VDDH_3") (pintype "bidirectional"))
      (node (ref "U$57") (pin "3") (pinfunction "VDDH_3") (pintype "bidirectional"))
      (node (ref "U$58") (pin "3") (pinfunction "VDDH_3") (pintype "bidirectional"))
      (node (ref "U$59") (pin "3") (pinfunction "VDDH_3") (pintype "bidirectional"))
      (node (ref "U$6") (pin "3") (pinfunction "VDDH_3") (pintype "bidirectional"))
      (node (ref "U$60") (pin "3") (pinfunction "VDDH_3") (pintype "bidirectional"))
      (node (ref "U$61") (pin "3") (pinfunction "VDDH_3") (pintype "bidirectional"))
      (node (ref "U$62") (pin "3") (pinfunction "VDDH_3") (pintype "bidirectional"))
      (node (ref "U$63") (pin "3") (pinfunction "VDDH_3") (pintype "bidirectional"))
      (node (ref "U$64") (pin "3") (pinfunction "VDDH_3") (pintype "bidirectional"))
      (node (ref "U$65") (pin "3") (pinfunction "VDDH_3") (pintype "bidirectional"))
      (node (ref "U$66") (pin "3") (pinfunction "VDDH_3") (pintype "bidirectional"))
      (node (ref "U$67") (pin "3") (pinfunction "VDDH_3") (pintype "bidirectional"))
      (node (ref "U$68") (pin "3") (pinfunction "VDDH_3") (pintype "bidirectional"))
      (node (ref "U$69") (pin "3") (pinfunction "VDDH_3") (pintype "bidirectional"))
      (node (ref "U$7") (pin "3") (pinfunction "VDDH_3") (pintype "bidirectional"))
      (node (ref "U$70") (pin "3") (pinfunction "VDDH_3") (pintype "bidirectional"))
      (node (ref "U$71") (pin "3") (pinfunction "VDDH_3") (pintype "bidirectional"))
      (node (ref "U$72") (pin "3") (pinfunction "VDDH_3") (pintype "bidirectional"))
      (node (ref "U$73") (pin "3") (pinfunction "VDDH_3") (pintype "bidirectional"))
      (node (ref "U$74") (pin "3") (pinfunction "VDDH_3") (pintype "bidirectional"))
      (node (ref "U$75") (pin "3") (pinfunction "VDDH_3") (pintype "bidirectional"))
      (node (ref "U$76") (pin "3") (pinfunction "VDDH_3") (pintype "bidirectional"))
      (node (ref "U$77") (pin "3") (pinfunction "VDDH_3") (pintype "bidirectional"))
      (node (ref "U$78") (pin "3") (pinfunction "VDDH_3") (pintype "bidirectional"))
      (node (ref "U$79") (pin "3") (pinfunction "VDDH_3") (pintype "bidirectional"))
      (node (ref "U$8") (pin "3") (pinfunction "VDDH_3") (pintype "bidirectional"))
      (node (ref "U$80") (pin "3") (pinfunction "VDDH_3") (pintype "bidirectional"))
      (node (ref "U$81") (pin "3") (pinfunction "VDDH_3") (pintype "bidirectional"))
      (node (ref "U$82") (pin "3") (pinfunction "VDDH_3") (pintype "bidirectional"))
      (node (ref "U$83") (pin "3") (pinfunction "VDDH_3") (pintype "bidirectional"))
      (node (ref "U$84") (pin "3") (pinfunction "VDDH_3") (pintype "bidirectional"))
      (node (ref "U$85") (pin "3") (pinfunction "VDDH_3") (pintype "bidirectional"))
      (node (ref "U$86") (pin "3") (pinfunction "VDDH_3") (pintype "bidirectional"))
      (node (ref "U$87") (pin "3") (pinfunction "VDDH_3") (pintype "bidirectional"))
      (node (ref "U$88") (pin "3") (pinfunction "VDDH_3") (pintype "bidirectional"))
      (node (ref "U$89") (pin "3") (pinfunction "VDDH_3") (pintype "bidirectional"))
      (node (ref "U$9") (pin "3") (pinfunction "VDDH_3") (pintype "bidirectional"))
      (node (ref "U$90") (pin "3") (pinfunction "VDDH_3") (pintype "bidirectional"))
      (node (ref "U$91") (pin "3") (pinfunction "VDDH_3") (pintype "bidirectional"))
      (node (ref "U$92") (pin "3") (pinfunction "VDDH_3") (pintype "bidirectional"))
      (node (ref "U$93") (pin "3") (pinfunction "VDDH_3") (pintype "bidirectional"))
      (node (ref "U$94") (pin "3") (pinfunction "VDDH_3") (pintype "bidirectional"))
      (node (ref "U$95") (pin "3") (pinfunction "VDDH_3") (pintype "bidirectional"))
      (node (ref "U$96") (pin "3") (pinfunction "VDDH_3") (pintype "bidirectional"))
    )
    (net (code "2") (name "/INT0") (class "Default")
      (node (ref "SV1") (pin "21") (pinfunction "21_21") (pintype "passive"))
      (node (ref "U$1") (pin "9") (pinfunction "INT_9") (pintype "bidirectional"))
    )
    (net (code "3") (name "/INT1") (class "Default")
      (node (ref "SV1") (pin "22") (pinfunction "22_22") (pintype "passive"))
      (node (ref "U$2") (pin "9") (pinfunction "INT_9") (pintype "bidirectional"))
    )
    (net (code "4") (name "/INT2") (class "Default")
      (node (ref "SV1") (pin "27") (pinfunction "27_27") (pintype "passive"))
      (node (ref "U$3") (pin "9") (pinfunction "INT_9") (pintype "bidirectional"))
    )
    (net (code "5") (name "/INT3") (class "Default")
      (node (ref "SV1") (pin "28") (pinfunction "28_28") (pintype "passive"))
      (node (ref "U$4") (pin "9") (pinfunction "INT_9") (pintype "bidirectional"))
    )
    (net (code "6") (name "/INT4") (class "Default")
      (node (ref "SV1") (pin "33") (pinfunction "33_33") (pintype "passive"))
      (node (ref "U$5") (pin "9") (pinfunction "INT_9") (pintype "bidirectional"))
    )
    (net (code "7") (name "/INT5") (class "Default")
      (node (ref "SV1") (pin "34") (pinfunction "34_34") (pintype "passive"))
      (node (ref "U$6") (pin "9") (pinfunction "INT_9") (pintype "bidirectional"))
    )
    (net (code "8") (name "/INT6") (class "Default")
      (node (ref "SV1") (pin "39") (pinfunction "39_39") (pintype "passive"))
      (node (ref "U$7") (pin "9") (pinfunction "INT_9") (pintype "bidirectional"))
    )
    (net (code "9") (name "/INT7") (class "Default")
      (node (ref "SV1") (pin "40") (pinfunction "40_40") (pintype "passive"))
      (node (ref "U$8") (pin "9") (pinfunction "INT_9") (pintype "bidirectional"))
    )
    (net (code "10") (name "/INT8") (class "Default")
      (node (ref "SV2") (pin "5") (pinfunction "5_5") (pintype "passive"))
      (node (ref "U$9") (pin "9") (pinfunction "INT_9") (pintype "bidirectional"))
    )
    (net (code "11") (name "/INT9") (class "Default")
      (node (ref "SV2") (pin "6") (pinfunction "6_6") (pintype "passive"))
      (node (ref "U$10") (pin "9") (pinfunction "INT_9") (pintype "bidirectional"))
    )
    (net (code "12") (name "/INT10") (class "Default")
      (node (ref "SV2") (pin "11") (pinfunction "11_11") (pintype "passive"))
      (node (ref "U$11") (pin "9") (pinfunction "INT_9") (pintype "bidirectional"))
    )
    (net (code "13") (name "/INT11") (class "Default")
      (node (ref "SV2") (pin "12") (pinfunction "12_12") (pintype "passive"))
      (node (ref "U$12") (pin "9") (pinfunction "INT_9") (pintype "bidirectional"))
    )
    (net (code "14") (name "/INT12") (class "Default")
      (node (ref "SV2") (pin "17") (pinfunction "17_17") (pintype "passive"))
      (node (ref "U$13") (pin "9") (pinfunction "INT_9") (pintype "bidirectional"))
    )
    (net (code "15") (name "/INT13") (class "Default")
      (node (ref "SV2") (pin "18") (pinfunction "18_18") (pintype "passive"))
      (node (ref "U$14") (pin "9") (pinfunction "INT_9") (pintype "bidirectional"))
    )
    (net (code "16") (name "/INT14") (class "Default")
      (node (ref "SV2") (pin "23") (pinfunction "23_23") (pintype "passive"))
      (node (ref "U$15") (pin "9") (pinfunction "INT_9") (pintype "bidirectional"))
    )
    (net (code "17") (name "/INT15") (class "Default")
      (node (ref "SV2") (pin "24") (pinfunction "24_24") (pintype "passive"))
      (node (ref "U$16") (pin "9") (pinfunction "INT_9") (pintype "bidirectional"))
    )
    (net (code "18") (name "/INT16") (class "Default")
      (node (ref "SV5") (pin "6") (pinfunction "6_6") (pintype "passive"))
      (node (ref "U$49") (pin "9") (pinfunction "INT_9") (pintype "bidirectional"))
    )
    (net (code "19") (name "/INT17") (class "Default")
      (node (ref "SV5") (pin "11") (pinfunction "11_11") (pintype "passive"))
      (node (ref "U$50") (pin "9") (pinfunction "INT_9") (pintype "bidirectional"))
    )
    (net (code "20") (name "/INT18") (class "Default")
      (node (ref "SV5") (pin "12") (pinfunction "12_12") (pintype "passive"))
      (node (ref "U$51") (pin "9") (pinfunction "INT_9") (pintype "bidirectional"))
    )
    (net (code "21") (name "/INT19") (class "Default")
      (node (ref "SV5") (pin "17") (pinfunction "17_17") (pintype "passive"))
      (node (ref "U$52") (pin "9") (pinfunction "INT_9") (pintype "bidirectional"))
    )
    (net (code "22") (name "/INT20") (class "Default")
      (node (ref "SV5") (pin "18") (pinfunction "18_18") (pintype "passive"))
      (node (ref "U$53") (pin "9") (pinfunction "INT_9") (pintype "bidirectional"))
    )
    (net (code "23") (name "/INT21") (class "Default")
      (node (ref "SV5") (pin "23") (pinfunction "23_23") (pintype "passive"))
      (node (ref "U$54") (pin "9") (pinfunction "INT_9") (pintype "bidirectional"))
    )
    (net (code "24") (name "/INT22") (class "Default")
      (node (ref "SV5") (pin "24") (pinfunction "24_24") (pintype "passive"))
      (node (ref "U$55") (pin "9") (pinfunction "INT_9") (pintype "bidirectional"))
    )
    (net (code "25") (name "/INT23") (class "Default")
      (node (ref "SV5") (pin "29") (pinfunction "29_29") (pintype "passive"))
      (node (ref "U$56") (pin "9") (pinfunction "INT_9") (pintype "bidirectional"))
    )
    (net (code "26") (name "/INT24") (class "Default")
      (node (ref "SV5") (pin "30") (pinfunction "30_30") (pintype "passive"))
      (node (ref "U$57") (pin "9") (pinfunction "INT_9") (pintype "bidirectional"))
    )
    (net (code "27") (name "/INT25") (class "Default")
      (node (ref "SV5") (pin "35") (pinfunction "35_35") (pintype "passive"))
      (node (ref "U$58") (pin "9") (pinfunction "INT_9") (pintype "bidirectional"))
    )
    (net (code "28") (name "/INT26") (class "Default")
      (node (ref "SV5") (pin "36") (pinfunction "36_36") (pintype "passive"))
      (node (ref "U$59") (pin "9") (pinfunction "INT_9") (pintype "bidirectional"))
    )
    (net (code "29") (name "/INT27") (class "Default")
      (node (ref "SV5") (pin "38") (pinfunction "38_38") (pintype "passive"))
      (node (ref "U$60") (pin "9") (pinfunction "INT_9") (pintype "bidirectional"))
    )
    (net (code "30") (name "/INT28") (class "Default")
      (node (ref "SV6") (pin "5") (pinfunction "5_5") (pintype "passive"))
      (node (ref "U$61") (pin "9") (pinfunction "INT_9") (pintype "bidirectional"))
    )
    (net (code "31") (name "/INT29") (class "Default")
      (node (ref "SV6") (pin "6") (pinfunction "6_6") (pintype "passive"))
      (node (ref "U$62") (pin "9") (pinfunction "INT_9") (pintype "bidirectional"))
    )
    (net (code "32") (name "/INT30") (class "Default")
      (node (ref "SV6") (pin "11") (pinfunction "11_11") (pintype "passive"))
      (node (ref "U$63") (pin "9") (pinfunction "INT_9") (pintype "bidirectional"))
    )
    (net (code "33") (name "/INT31") (class "Default")
      (node (ref "SV6") (pin "12") (pinfunction "12_12") (pintype "passive"))
      (node (ref "U$64") (pin "9") (pinfunction "INT_9") (pintype "bidirectional"))
    )
    (net (code "34") (name "/INT32") (class "Default")
      (node (ref "SV2") (pin "29") (pinfunction "29_29") (pintype "passive"))
      (node (ref "U$17") (pin "9") (pinfunction "INT_9") (pintype "bidirectional"))
    )
    (net (code "35") (name "/INT33") (class "Default")
      (node (ref "SV2") (pin "30") (pinfunction "30_30") (pintype "passive"))
      (node (ref "U$18") (pin "9") (pinfunction "INT_9") (pintype "bidirectional"))
    )
    (net (code "36") (name "/INT34") (class "Default")
      (node (ref "SV2") (pin "35") (pinfunction "35_35") (pintype "passive"))
      (node (ref "U$19") (pin "9") (pinfunction "INT_9") (pintype "bidirectional"))
    )
    (net (code "37") (name "/INT35") (class "Default")
      (node (ref "SV2") (pin "36") (pinfunction "36_36") (pintype "passive"))
      (node (ref "U$20") (pin "9") (pinfunction "INT_9") (pintype "bidirectional"))
    )
    (net (code "38") (name "/INT36") (class "Default")
      (node (ref "SV2") (pin "38") (pinfunction "38_38") (pintype "passive"))
      (node (ref "U$21") (pin "9") (pinfunction "INT_9") (pintype "bidirectional"))
    )
    (net (code "39") (name "/INT37") (class "Default")
      (node (ref "SV3") (pin "5") (pinfunction "5_5") (pintype "passive"))
      (node (ref "U$22") (pin "9") (pinfunction "INT_9") (pintype "bidirectional"))
    )
    (net (code "40") (name "/INT38") (class "Default")
      (node (ref "SV3") (pin "6") (pinfunction "6_6") (pintype "passive"))
      (node (ref "U$23") (pin "9") (pinfunction "INT_9") (pintype "bidirectional"))
    )
    (net (code "41") (name "/INT39") (class "Default")
      (node (ref "SV3") (pin "11") (pinfunction "11_11") (pintype "passive"))
      (node (ref "U$24") (pin "9") (pinfunction "INT_9") (pintype "bidirectional"))
    )
    (net (code "42") (name "/INT40") (class "Default")
      (node (ref "SV3") (pin "12") (pinfunction "12_12") (pintype "passive"))
      (node (ref "U$25") (pin "9") (pinfunction "INT_9") (pintype "bidirectional"))
    )
    (net (code "43") (name "/INT41") (class "Default")
      (node (ref "SV3") (pin "17") (pinfunction "17_17") (pintype "passive"))
      (node (ref "U$26") (pin "9") (pinfunction "INT_9") (pintype "bidirectional"))
    )
    (net (code "44") (name "/INT42") (class "Default")
      (node (ref "SV3") (pin "18") (pinfunction "18_18") (pintype "passive"))
      (node (ref "U$27") (pin "9") (pinfunction "INT_9") (pintype "bidirectional"))
    )
    (net (code "45") (name "/INT43") (class "Default")
      (node (ref "SV3") (pin "23") (pinfunction "23_23") (pintype "passive"))
      (node (ref "U$28") (pin "9") (pinfunction "INT_9") (pintype "bidirectional"))
    )
    (net (code "46") (name "/INT44") (class "Default")
      (node (ref "SV3") (pin "24") (pinfunction "24_24") (pintype "passive"))
      (node (ref "U$29") (pin "9") (pinfunction "INT_9") (pintype "bidirectional"))
    )
    (net (code "47") (name "/INT45") (class "Default")
      (node (ref "SV3") (pin "29") (pinfunction "29_29") (pintype "passive"))
      (node (ref "U$30") (pin "9") (pinfunction "INT_9") (pintype "bidirectional"))
    )
    (net (code "48") (name "/INT46") (class "Default")
      (node (ref "SV3") (pin "30") (pinfunction "30_30") (pintype "passive"))
      (node (ref "U$31") (pin "9") (pinfunction "INT_9") (pintype "bidirectional"))
    )
    (net (code "49") (name "/INT47") (class "Default")
      (node (ref "SV3") (pin "35") (pinfunction "35_35") (pintype "passive"))
      (node (ref "U$32") (pin "9") (pinfunction "INT_9") (pintype "bidirectional"))
    )
    (net (code "50") (name "/INT48") (class "Default")
      (node (ref "SV6") (pin "17") (pinfunction "17_17") (pintype "passive"))
      (node (ref "U$65") (pin "9") (pinfunction "INT_9") (pintype "bidirectional"))
    )
    (net (code "51") (name "/INT49") (class "Default")
      (node (ref "SV6") (pin "18") (pinfunction "18_18") (pintype "passive"))
      (node (ref "U$66") (pin "9") (pinfunction "INT_9") (pintype "bidirectional"))
    )
    (net (code "52") (name "/INT50") (class "Default")
      (node (ref "SV6") (pin "23") (pinfunction "23_23") (pintype "passive"))
      (node (ref "U$67") (pin "9") (pinfunction "INT_9") (pintype "bidirectional"))
    )
    (net (code "53") (name "/INT51") (class "Default")
      (node (ref "SV6") (pin "24") (pinfunction "24_24") (pintype "passive"))
      (node (ref "U$68") (pin "9") (pinfunction "INT_9") (pintype "bidirectional"))
    )
    (net (code "54") (name "/INT52") (class "Default")
      (node (ref "SV6") (pin "29") (pinfunction "29_29") (pintype "passive"))
      (node (ref "U$69") (pin "9") (pinfunction "INT_9") (pintype "bidirectional"))
    )
    (net (code "55") (name "/INT53") (class "Default")
      (node (ref "SV6") (pin "30") (pinfunction "30_30") (pintype "passive"))
      (node (ref "U$70") (pin "9") (pinfunction "INT_9") (pintype "bidirectional"))
    )
    (net (code "56") (name "/INT54") (class "Default")
      (node (ref "SV6") (pin "35") (pinfunction "35_35") (pintype "passive"))
      (node (ref "U$71") (pin "9") (pinfunction "INT_9") (pintype "bidirectional"))
    )
    (net (code "57") (name "/INT55") (class "Default")
      (node (ref "SV6") (pin "36") (pinfunction "36_36") (pintype "passive"))
      (node (ref "U$72") (pin "9") (pinfunction "INT_9") (pintype "bidirectional"))
    )
    (net (code "58") (name "/INT56") (class "Default")
      (node (ref "SV6") (pin "38") (pinfunction "38_38") (pintype "passive"))
      (node (ref "U$73") (pin "9") (pinfunction "INT_9") (pintype "bidirectional"))
    )
    (net (code "59") (name "/INT57") (class "Default")
      (node (ref "SV7") (pin "5") (pinfunction "5_5") (pintype "passive"))
      (node (ref "U$74") (pin "9") (pinfunction "INT_9") (pintype "bidirectional"))
    )
    (net (code "60") (name "/INT58") (class "Default")
      (node (ref "SV7") (pin "6") (pinfunction "6_6") (pintype "passive"))
      (node (ref "U$75") (pin "9") (pinfunction "INT_9") (pintype "bidirectional"))
    )
    (net (code "61") (name "/INT59") (class "Default")
      (node (ref "SV7") (pin "11") (pinfunction "11_11") (pintype "passive"))
      (node (ref "U$76") (pin "9") (pinfunction "INT_9") (pintype "bidirectional"))
    )
    (net (code "62") (name "/INT60") (class "Default")
      (node (ref "SV7") (pin "12") (pinfunction "12_12") (pintype "passive"))
      (node (ref "U$77") (pin "9") (pinfunction "INT_9") (pintype "bidirectional"))
    )
    (net (code "63") (name "/INT61") (class "Default")
      (node (ref "SV7") (pin "17") (pinfunction "17_17") (pintype "passive"))
      (node (ref "U$78") (pin "9") (pinfunction "INT_9") (pintype "bidirectional"))
    )
    (net (code "64") (name "/INT62") (class "Default")
      (node (ref "SV7") (pin "18") (pinfunction "18_18") (pintype "passive"))
      (node (ref "U$79") (pin "9") (pinfunction "INT_9") (pintype "bidirectional"))
    )
    (net (code "65") (name "/INT63") (class "Default")
      (node (ref "SV7") (pin "23") (pinfunction "23_23") (pintype "passive"))
      (node (ref "U$80") (pin "9") (pinfunction "INT_9") (pintype "bidirectional"))
    )
    (net (code "66") (name "/INT64") (class "Default")
      (node (ref "SV3") (pin "36") (pinfunction "36_36") (pintype "passive"))
      (node (ref "U$33") (pin "9") (pinfunction "INT_9") (pintype "bidirectional"))
    )
    (net (code "67") (name "/INT65") (class "Default")
      (node (ref "SV3") (pin "38") (pinfunction "38_38") (pintype "passive"))
      (node (ref "U$34") (pin "9") (pinfunction "INT_9") (pintype "bidirectional"))
    )
    (net (code "68") (name "/INT66") (class "Default")
      (node (ref "SV4") (pin "5") (pinfunction "5_5") (pintype "passive"))
      (node (ref "U$35") (pin "9") (pinfunction "INT_9") (pintype "bidirectional"))
    )
    (net (code "69") (name "/INT67") (class "Default")
      (node (ref "SV4") (pin "6") (pinfunction "6_6") (pintype "passive"))
      (node (ref "U$36") (pin "9") (pinfunction "INT_9") (pintype "bidirectional"))
    )
    (net (code "70") (name "/INT68") (class "Default")
      (node (ref "SV4") (pin "11") (pinfunction "11_11") (pintype "passive"))
      (node (ref "U$37") (pin "9") (pinfunction "INT_9") (pintype "bidirectional"))
    )
    (net (code "71") (name "/INT69") (class "Default")
      (node (ref "SV4") (pin "12") (pinfunction "12_12") (pintype "passive"))
      (node (ref "U$38") (pin "9") (pinfunction "INT_9") (pintype "bidirectional"))
    )
    (net (code "72") (name "/INT70") (class "Default")
      (node (ref "SV4") (pin "17") (pinfunction "17_17") (pintype "passive"))
      (node (ref "U$39") (pin "9") (pinfunction "INT_9") (pintype "bidirectional"))
    )
    (net (code "73") (name "/INT71") (class "Default")
      (node (ref "SV4") (pin "18") (pinfunction "18_18") (pintype "passive"))
      (node (ref "U$40") (pin "9") (pinfunction "INT_9") (pintype "bidirectional"))
    )
    (net (code "74") (name "/INT72") (class "Default")
      (node (ref "SV4") (pin "23") (pinfunction "23_23") (pintype "passive"))
      (node (ref "U$41") (pin "9") (pinfunction "INT_9") (pintype "bidirectional"))
    )
    (net (code "75") (name "/INT73") (class "Default")
      (node (ref "SV4") (pin "24") (pinfunction "24_24") (pintype "passive"))
      (node (ref "U$42") (pin "9") (pinfunction "INT_9") (pintype "bidirectional"))
    )
    (net (code "76") (name "/INT74") (class "Default")
      (node (ref "SV4") (pin "29") (pinfunction "29_29") (pintype "passive"))
      (node (ref "U$43") (pin "9") (pinfunction "INT_9") (pintype "bidirectional"))
    )
    (net (code "77") (name "/INT75") (class "Default")
      (node (ref "SV4") (pin "30") (pinfunction "30_30") (pintype "passive"))
      (node (ref "U$44") (pin "9") (pinfunction "INT_9") (pintype "bidirectional"))
    )
    (net (code "78") (name "/INT76") (class "Default")
      (node (ref "SV4") (pin "35") (pinfunction "35_35") (pintype "passive"))
      (node (ref "U$45") (pin "9") (pinfunction "INT_9") (pintype "bidirectional"))
    )
    (net (code "79") (name "/INT77") (class "Default")
      (node (ref "SV4") (pin "36") (pinfunction "36_36") (pintype "passive"))
      (node (ref "U$46") (pin "9") (pinfunction "INT_9") (pintype "bidirectional"))
    )
    (net (code "80") (name "/INT78") (class "Default")
      (node (ref "SV4") (pin "38") (pinfunction "38_38") (pintype "passive"))
      (node (ref "U$47") (pin "9") (pinfunction "INT_9") (pintype "bidirectional"))
    )
    (net (code "81") (name "/INT79") (class "Default")
      (node (ref "SV5") (pin "5") (pinfunction "5_5") (pintype "passive"))
      (node (ref "U$48") (pin "9") (pinfunction "INT_9") (pintype "bidirectional"))
    )
    (net (code "82") (name "/INT80") (class "Default")
      (node (ref "SV7") (pin "24") (pinfunction "24_24") (pintype "passive"))
      (node (ref "U$81") (pin "9") (pinfunction "INT_9") (pintype "bidirectional"))
    )
    (net (code "83") (name "/INT81") (class "Default")
      (node (ref "SV7") (pin "29") (pinfunction "29_29") (pintype "passive"))
      (node (ref "U$82") (pin "9") (pinfunction "INT_9") (pintype "bidirectional"))
    )
    (net (code "84") (name "/INT82") (class "Default")
      (node (ref "SV7") (pin "30") (pinfunction "30_30") (pintype "passive"))
      (node (ref "U$83") (pin "9") (pinfunction "INT_9") (pintype "bidirectional"))
    )
    (net (code "85") (name "/INT83") (class "Default")
      (node (ref "SV7") (pin "35") (pinfunction "35_35") (pintype "passive"))
      (node (ref "U$84") (pin "9") (pinfunction "INT_9") (pintype "bidirectional"))
    )
    (net (code "86") (name "/INT84") (class "Default")
      (node (ref "SV7") (pin "36") (pinfunction "36_36") (pintype "passive"))
      (node (ref "U$85") (pin "9") (pinfunction "INT_9") (pintype "bidirectional"))
    )
    (net (code "87") (name "/INT85") (class "Default")
      (node (ref "SV7") (pin "38") (pinfunction "38_38") (pintype "passive"))
      (node (ref "U$86") (pin "9") (pinfunction "INT_9") (pintype "bidirectional"))
    )
    (net (code "88") (name "/INT86") (class "Default")
      (node (ref "SV8") (pin "5") (pinfunction "5_5") (pintype "passive"))
      (node (ref "U$87") (pin "9") (pinfunction "INT_9") (pintype "bidirectional"))
    )
    (net (code "89") (name "/INT87") (class "Default")
      (node (ref "SV8") (pin "6") (pinfunction "6_6") (pintype "passive"))
      (node (ref "U$88") (pin "9") (pinfunction "INT_9") (pintype "bidirectional"))
    )
    (net (code "90") (name "/INT88") (class "Default")
      (node (ref "SV8") (pin "11") (pinfunction "11_11") (pintype "passive"))
      (node (ref "U$89") (pin "9") (pinfunction "INT_9") (pintype "bidirectional"))
    )
    (net (code "91") (name "/INT89") (class "Default")
      (node (ref "SV8") (pin "12") (pinfunction "12_12") (pintype "passive"))
      (node (ref "U$90") (pin "9") (pinfunction "INT_9") (pintype "bidirectional"))
    )
    (net (code "92") (name "/INT90") (class "Default")
      (node (ref "SV8") (pin "17") (pinfunction "17_17") (pintype "passive"))
      (node (ref "U$91") (pin "9") (pinfunction "INT_9") (pintype "bidirectional"))
    )
    (net (code "93") (name "/INT91") (class "Default")
      (node (ref "SV8") (pin "18") (pinfunction "18_18") (pintype "passive"))
      (node (ref "U$92") (pin "9") (pinfunction "INT_9") (pintype "bidirectional"))
    )
    (net (code "94") (name "/INT92") (class "Default")
      (node (ref "SV8") (pin "23") (pinfunction "23_23") (pintype "passive"))
      (node (ref "U$93") (pin "9") (pinfunction "INT_9") (pintype "bidirectional"))
    )
    (net (code "95") (name "/INT93") (class "Default")
      (node (ref "SV8") (pin "24") (pinfunction "24_24") (pintype "passive"))
      (node (ref "U$94") (pin "9") (pinfunction "INT_9") (pintype "bidirectional"))
    )
    (net (code "96") (name "/INT94") (class "Default")
      (node (ref "SV8") (pin "29") (pinfunction "29_29") (pintype "passive"))
      (node (ref "U$95") (pin "9") (pinfunction "INT_9") (pintype "bidirectional"))
    )
    (net (code "97") (name "/INT95") (class "Default")
      (node (ref "SV8") (pin "30") (pinfunction "30_30") (pintype "passive"))
      (node (ref "U$96") (pin "9") (pinfunction "INT_9") (pintype "bidirectional"))
    )
    (net (code "98") (name "/SCL0") (class "Default")
      (node (ref "SV1") (pin "17") (pinfunction "17_17") (pintype "passive"))
      (node (ref "U$1") (pin "7") (pinfunction "SCL_7") (pintype "bidirectional"))
    )
    (net (code "99") (name "/SCL1") (class "Default")
      (node (ref "SV1") (pin "18") (pinfunction "18_18") (pintype "passive"))
      (node (ref "U$2") (pin "7") (pinfunction "SCL_7") (pintype "bidirectional"))
    )
    (net (code "100") (name "/SCL2") (class "Default")
      (node (ref "SV1") (pin "23") (pinfunction "23_23") (pintype "passive"))
      (node (ref "U$3") (pin "7") (pinfunction "SCL_7") (pintype "bidirectional"))
    )
    (net (code "101") (name "/SCL3") (class "Default")
      (node (ref "SV1") (pin "24") (pinfunction "24_24") (pintype "passive"))
      (node (ref "U$4") (pin "7") (pinfunction "SCL_7") (pintype "bidirectional"))
    )
    (net (code "102") (name "/SCL4") (class "Default")
      (node (ref "SV1") (pin "29") (pinfunction "29_29") (pintype "passive"))
      (node (ref "U$5") (pin "7") (pinfunction "SCL_7") (pintype "bidirectional"))
    )
    (net (code "103") (name "/SCL5") (class "Default")
      (node (ref "SV1") (pin "30") (pinfunction "30_30") (pintype "passive"))
      (node (ref "U$6") (pin "7") (pinfunction "SCL_7") (pintype "bidirectional"))
    )
    (net (code "104") (name "/SCL6") (class "Default")
      (node (ref "SV1") (pin "35") (pinfunction "35_35") (pintype "passive"))
      (node (ref "U$7") (pin "7") (pinfunction "SCL_7") (pintype "bidirectional"))
    )
    (net (code "105") (name "/SCL7") (class "Default")
      (node (ref "SV1") (pin "36") (pinfunction "36_36") (pintype "passive"))
      (node (ref "U$8") (pin "7") (pinfunction "SCL_7") (pintype "bidirectional"))
    )
    (net (code "106") (name "/SCL8") (class "Default")
      (node (ref "SV2") (pin "1") (pinfunction "1_1") (pintype "passive"))
      (node (ref "U$9") (pin "7") (pinfunction "SCL_7") (pintype "bidirectional"))
    )
    (net (code "107") (name "/SCL9") (class "Default")
      (node (ref "SV2") (pin "2") (pinfunction "2_2") (pintype "passive"))
      (node (ref "U$10") (pin "7") (pinfunction "SCL_7") (pintype "bidirectional"))
    )
    (net (code "108") (name "/SCL10") (class "Default")
      (node (ref "SV2") (pin "7") (pinfunction "7_7") (pintype "passive"))
      (node (ref "U$11") (pin "7") (pinfunction "SCL_7") (pintype "bidirectional"))
    )
    (net (code "109") (name "/SCL11") (class "Default")
      (node (ref "SV2") (pin "8") (pinfunction "8_8") (pintype "passive"))
      (node (ref "U$12") (pin "7") (pinfunction "SCL_7") (pintype "bidirectional"))
    )
    (net (code "110") (name "/SCL12") (class "Default")
      (node (ref "SV2") (pin "13") (pinfunction "13_13") (pintype "passive"))
      (node (ref "U$13") (pin "7") (pinfunction "SCL_7") (pintype "bidirectional"))
    )
    (net (code "111") (name "/SCL13") (class "Default")
      (node (ref "SV2") (pin "14") (pinfunction "14_14") (pintype "passive"))
      (node (ref "U$14") (pin "7") (pinfunction "SCL_7") (pintype "bidirectional"))
    )
    (net (code "112") (name "/SCL14") (class "Default")
      (node (ref "SV2") (pin "19") (pinfunction "19_19") (pintype "passive"))
      (node (ref "U$15") (pin "7") (pinfunction "SCL_7") (pintype "bidirectional"))
    )
    (net (code "113") (name "/SCL15") (class "Default")
      (node (ref "SV2") (pin "20") (pinfunction "20_20") (pintype "passive"))
      (node (ref "U$16") (pin "7") (pinfunction "SCL_7") (pintype "bidirectional"))
    )
    (net (code "114") (name "/SCL16") (class "Default")
      (node (ref "SV5") (pin "2") (pinfunction "2_2") (pintype "passive"))
      (node (ref "U$49") (pin "7") (pinfunction "SCL_7") (pintype "bidirectional"))
    )
    (net (code "115") (name "/SCL17") (class "Default")
      (node (ref "SV5") (pin "7") (pinfunction "7_7") (pintype "passive"))
      (node (ref "U$50") (pin "7") (pinfunction "SCL_7") (pintype "bidirectional"))
    )
    (net (code "116") (name "/SCL18") (class "Default")
      (node (ref "SV5") (pin "8") (pinfunction "8_8") (pintype "passive"))
      (node (ref "U$51") (pin "7") (pinfunction "SCL_7") (pintype "bidirectional"))
    )
    (net (code "117") (name "/SCL19") (class "Default")
      (node (ref "SV5") (pin "13") (pinfunction "13_13") (pintype "passive"))
      (node (ref "U$52") (pin "7") (pinfunction "SCL_7") (pintype "bidirectional"))
    )
    (net (code "118") (name "/SCL20") (class "Default")
      (node (ref "SV5") (pin "14") (pinfunction "14_14") (pintype "passive"))
      (node (ref "U$53") (pin "7") (pinfunction "SCL_7") (pintype "bidirectional"))
    )
    (net (code "119") (name "/SCL21") (class "Default")
      (node (ref "SV5") (pin "19") (pinfunction "19_19") (pintype "passive"))
      (node (ref "U$54") (pin "7") (pinfunction "SCL_7") (pintype "bidirectional"))
    )
    (net (code "120") (name "/SCL22") (class "Default")
      (node (ref "SV5") (pin "20") (pinfunction "20_20") (pintype "passive"))
      (node (ref "U$55") (pin "7") (pinfunction "SCL_7") (pintype "bidirectional"))
    )
    (net (code "121") (name "/SCL23") (class "Default")
      (node (ref "SV5") (pin "25") (pinfunction "25_25") (pintype "passive"))
      (node (ref "U$56") (pin "7") (pinfunction "SCL_7") (pintype "bidirectional"))
    )
    (net (code "122") (name "/SCL24") (class "Default")
      (node (ref "SV5") (pin "26") (pinfunction "26_26") (pintype "passive"))
      (node (ref "U$57") (pin "7") (pinfunction "SCL_7") (pintype "bidirectional"))
    )
    (net (code "123") (name "/SCL25") (class "Default")
      (node (ref "SV5") (pin "31") (pinfunction "31_31") (pintype "passive"))
      (node (ref "U$58") (pin "7") (pinfunction "SCL_7") (pintype "bidirectional"))
    )
    (net (code "124") (name "/SCL26") (class "Default")
      (node (ref "SV5") (pin "32") (pinfunction "32_32") (pintype "passive"))
      (node (ref "U$59") (pin "7") (pinfunction "SCL_7") (pintype "bidirectional"))
    )
    (net (code "125") (name "/SCL27") (class "Default")
      (node (ref "SV5") (pin "37") (pinfunction "37_37") (pintype "passive"))
      (node (ref "U$60") (pin "7") (pinfunction "SCL_7") (pintype "bidirectional"))
    )
    (net (code "126") (name "/SCL28") (class "Default")
      (node (ref "SV6") (pin "1") (pinfunction "1_1") (pintype "passive"))
      (node (ref "U$61") (pin "7") (pinfunction "SCL_7") (pintype "bidirectional"))
    )
    (net (code "127") (name "/SCL29") (class "Default")
      (node (ref "SV6") (pin "2") (pinfunction "2_2") (pintype "passive"))
      (node (ref "U$62") (pin "7") (pinfunction "SCL_7") (pintype "bidirectional"))
    )
    (net (code "128") (name "/SCL30") (class "Default")
      (node (ref "SV6") (pin "7") (pinfunction "7_7") (pintype "passive"))
      (node (ref "U$63") (pin "7") (pinfunction "SCL_7") (pintype "bidirectional"))
    )
    (net (code "129") (name "/SCL31") (class "Default")
      (node (ref "SV6") (pin "8") (pinfunction "8_8") (pintype "passive"))
      (node (ref "U$64") (pin "7") (pinfunction "SCL_7") (pintype "bidirectional"))
      (node (ref "U1") (pin "4") (pinfunction "SCK_4") (pintype "passive"))
      (node (ref "U2") (pin "6") (pinfunction "SCL_6") (pintype "input"))
    )
    (net (code "130") (name "/SCL32") (class "Default")
      (node (ref "SV2") (pin "25") (pinfunction "25_25") (pintype "passive"))
      (node (ref "U$17") (pin "7") (pinfunction "SCL_7") (pintype "bidirectional"))
    )
    (net (code "131") (name "/SCL33") (class "Default")
      (node (ref "SV2") (pin "26") (pinfunction "26_26") (pintype "passive"))
      (node (ref "U$18") (pin "7") (pinfunction "SCL_7") (pintype "bidirectional"))
    )
    (net (code "132") (name "/SCL34") (class "Default")
      (node (ref "SV2") (pin "31") (pinfunction "31_31") (pintype "passive"))
      (node (ref "U$19") (pin "7") (pinfunction "SCL_7") (pintype "bidirectional"))
    )
    (net (code "133") (name "/SCL35") (class "Default")
      (node (ref "SV2") (pin "32") (pinfunction "32_32") (pintype "passive"))
      (node (ref "U$20") (pin "7") (pinfunction "SCL_7") (pintype "bidirectional"))
    )
    (net (code "134") (name "/SCL36") (class "Default")
      (node (ref "SV2") (pin "37") (pinfunction "37_37") (pintype "passive"))
      (node (ref "U$21") (pin "7") (pinfunction "SCL_7") (pintype "bidirectional"))
    )
    (net (code "135") (name "/SCL37") (class "Default")
      (node (ref "SV3") (pin "1") (pinfunction "1_1") (pintype "passive"))
      (node (ref "U$22") (pin "7") (pinfunction "SCL_7") (pintype "bidirectional"))
    )
    (net (code "136") (name "/SCL38") (class "Default")
      (node (ref "SV3") (pin "2") (pinfunction "2_2") (pintype "passive"))
      (node (ref "U$23") (pin "7") (pinfunction "SCL_7") (pintype "bidirectional"))
    )
    (net (code "137") (name "/SCL39") (class "Default")
      (node (ref "SV3") (pin "7") (pinfunction "7_7") (pintype "passive"))
      (node (ref "U$24") (pin "7") (pinfunction "SCL_7") (pintype "bidirectional"))
    )
    (net (code "138") (name "/SCL40") (class "Default")
      (node (ref "SV3") (pin "8") (pinfunction "8_8") (pintype "passive"))
      (node (ref "U$25") (pin "7") (pinfunction "SCL_7") (pintype "bidirectional"))
    )
    (net (code "139") (name "/SCL41") (class "Default")
      (node (ref "SV3") (pin "13") (pinfunction "13_13") (pintype "passive"))
      (node (ref "U$26") (pin "7") (pinfunction "SCL_7") (pintype "bidirectional"))
    )
    (net (code "140") (name "/SCL42") (class "Default")
      (node (ref "SV3") (pin "14") (pinfunction "14_14") (pintype "passive"))
      (node (ref "U$27") (pin "7") (pinfunction "SCL_7") (pintype "bidirectional"))
    )
    (net (code "141") (name "/SCL43") (class "Default")
      (node (ref "SV3") (pin "19") (pinfunction "19_19") (pintype "passive"))
      (node (ref "U$28") (pin "7") (pinfunction "SCL_7") (pintype "bidirectional"))
    )
    (net (code "142") (name "/SCL44") (class "Default")
      (node (ref "SV3") (pin "20") (pinfunction "20_20") (pintype "passive"))
      (node (ref "U$29") (pin "7") (pinfunction "SCL_7") (pintype "bidirectional"))
    )
    (net (code "143") (name "/SCL45") (class "Default")
      (node (ref "SV3") (pin "25") (pinfunction "25_25") (pintype "passive"))
      (node (ref "U$30") (pin "7") (pinfunction "SCL_7") (pintype "bidirectional"))
    )
    (net (code "144") (name "/SCL46") (class "Default")
      (node (ref "SV3") (pin "26") (pinfunction "26_26") (pintype "passive"))
      (node (ref "U$31") (pin "7") (pinfunction "SCL_7") (pintype "bidirectional"))
    )
    (net (code "145") (name "/SCL47") (class "Default")
      (node (ref "SV3") (pin "31") (pinfunction "31_31") (pintype "passive"))
      (node (ref "U$32") (pin "7") (pinfunction "SCL_7") (pintype "bidirectional"))
    )
    (net (code "146") (name "/SCL48") (class "Default")
      (node (ref "SV6") (pin "13") (pinfunction "13_13") (pintype "passive"))
      (node (ref "U$65") (pin "7") (pinfunction "SCL_7") (pintype "bidirectional"))
    )
    (net (code "147") (name "/SCL49") (class "Default")
      (node (ref "SV6") (pin "14") (pinfunction "14_14") (pintype "passive"))
      (node (ref "U$66") (pin "7") (pinfunction "SCL_7") (pintype "bidirectional"))
    )
    (net (code "148") (name "/SCL50") (class "Default")
      (node (ref "SV6") (pin "19") (pinfunction "19_19") (pintype "passive"))
      (node (ref "U$67") (pin "7") (pinfunction "SCL_7") (pintype "bidirectional"))
    )
    (net (code "149") (name "/SCL51") (class "Default")
      (node (ref "SV6") (pin "20") (pinfunction "20_20") (pintype "passive"))
      (node (ref "U$68") (pin "7") (pinfunction "SCL_7") (pintype "bidirectional"))
    )
    (net (code "150") (name "/SCL52") (class "Default")
      (node (ref "SV6") (pin "25") (pinfunction "25_25") (pintype "passive"))
      (node (ref "U$69") (pin "7") (pinfunction "SCL_7") (pintype "bidirectional"))
    )
    (net (code "151") (name "/SCL53") (class "Default")
      (node (ref "SV6") (pin "26") (pinfunction "26_26") (pintype "passive"))
      (node (ref "U$70") (pin "7") (pinfunction "SCL_7") (pintype "bidirectional"))
    )
    (net (code "152") (name "/SCL54") (class "Default")
      (node (ref "SV6") (pin "31") (pinfunction "31_31") (pintype "passive"))
      (node (ref "U$71") (pin "7") (pinfunction "SCL_7") (pintype "bidirectional"))
    )
    (net (code "153") (name "/SCL55") (class "Default")
      (node (ref "SV6") (pin "32") (pinfunction "32_32") (pintype "passive"))
      (node (ref "U$72") (pin "7") (pinfunction "SCL_7") (pintype "bidirectional"))
    )
    (net (code "154") (name "/SCL56") (class "Default")
      (node (ref "SV6") (pin "37") (pinfunction "37_37") (pintype "passive"))
      (node (ref "U$73") (pin "7") (pinfunction "SCL_7") (pintype "bidirectional"))
    )
    (net (code "155") (name "/SCL57") (class "Default")
      (node (ref "SV7") (pin "1") (pinfunction "1_1") (pintype "passive"))
      (node (ref "U$74") (pin "7") (pinfunction "SCL_7") (pintype "bidirectional"))
    )
    (net (code "156") (name "/SCL58") (class "Default")
      (node (ref "SV7") (pin "2") (pinfunction "2_2") (pintype "passive"))
      (node (ref "U$75") (pin "7") (pinfunction "SCL_7") (pintype "bidirectional"))
    )
    (net (code "157") (name "/SCL59") (class "Default")
      (node (ref "SV7") (pin "7") (pinfunction "7_7") (pintype "passive"))
      (node (ref "U$76") (pin "7") (pinfunction "SCL_7") (pintype "bidirectional"))
    )
    (net (code "158") (name "/SCL60") (class "Default")
      (node (ref "SV7") (pin "8") (pinfunction "8_8") (pintype "passive"))
      (node (ref "U$77") (pin "7") (pinfunction "SCL_7") (pintype "bidirectional"))
    )
    (net (code "159") (name "/SCL61") (class "Default")
      (node (ref "SV7") (pin "13") (pinfunction "13_13") (pintype "passive"))
      (node (ref "U$78") (pin "7") (pinfunction "SCL_7") (pintype "bidirectional"))
    )
    (net (code "160") (name "/SCL62") (class "Default")
      (node (ref "SV7") (pin "14") (pinfunction "14_14") (pintype "passive"))
      (node (ref "U$79") (pin "7") (pinfunction "SCL_7") (pintype "bidirectional"))
    )
    (net (code "161") (name "/SCL63") (class "Default")
      (node (ref "SV7") (pin "19") (pinfunction "19_19") (pintype "passive"))
      (node (ref "U$80") (pin "7") (pinfunction "SCL_7") (pintype "bidirectional"))
      (node (ref "U3") (pin "4") (pinfunction "SCK_4") (pintype "passive"))
      (node (ref "U4") (pin "6") (pinfunction "SCL_6") (pintype "input"))
    )
    (net (code "162") (name "/SCL64") (class "Default")
      (node (ref "SV3") (pin "32") (pinfunction "32_32") (pintype "passive"))
      (node (ref "U$33") (pin "7") (pinfunction "SCL_7") (pintype "bidirectional"))
    )
    (net (code "163") (name "/SCL65") (class "Default")
      (node (ref "SV3") (pin "37") (pinfunction "37_37") (pintype "passive"))
      (node (ref "U$34") (pin "7") (pinfunction "SCL_7") (pintype "bidirectional"))
    )
    (net (code "164") (name "/SCL66") (class "Default")
      (node (ref "SV4") (pin "1") (pinfunction "1_1") (pintype "passive"))
      (node (ref "U$35") (pin "7") (pinfunction "SCL_7") (pintype "bidirectional"))
    )
    (net (code "165") (name "/SCL67") (class "Default")
      (node (ref "SV4") (pin "2") (pinfunction "2_2") (pintype "passive"))
      (node (ref "U$36") (pin "7") (pinfunction "SCL_7") (pintype "bidirectional"))
    )
    (net (code "166") (name "/SCL68") (class "Default")
      (node (ref "SV4") (pin "7") (pinfunction "7_7") (pintype "passive"))
      (node (ref "U$37") (pin "7") (pinfunction "SCL_7") (pintype "bidirectional"))
    )
    (net (code "167") (name "/SCL69") (class "Default")
      (node (ref "SV4") (pin "8") (pinfunction "8_8") (pintype "passive"))
      (node (ref "U$38") (pin "7") (pinfunction "SCL_7") (pintype "bidirectional"))
    )
    (net (code "168") (name "/SCL70") (class "Default")
      (node (ref "SV4") (pin "13") (pinfunction "13_13") (pintype "passive"))
      (node (ref "U$39") (pin "7") (pinfunction "SCL_7") (pintype "bidirectional"))
    )
    (net (code "169") (name "/SCL71") (class "Default")
      (node (ref "SV4") (pin "14") (pinfunction "14_14") (pintype "passive"))
      (node (ref "U$40") (pin "7") (pinfunction "SCL_7") (pintype "bidirectional"))
    )
    (net (code "170") (name "/SCL72") (class "Default")
      (node (ref "SV4") (pin "19") (pinfunction "19_19") (pintype "passive"))
      (node (ref "U$41") (pin "7") (pinfunction "SCL_7") (pintype "bidirectional"))
    )
    (net (code "171") (name "/SCL73") (class "Default")
      (node (ref "SV4") (pin "20") (pinfunction "20_20") (pintype "passive"))
      (node (ref "U$42") (pin "7") (pinfunction "SCL_7") (pintype "bidirectional"))
    )
    (net (code "172") (name "/SCL74") (class "Default")
      (node (ref "SV4") (pin "25") (pinfunction "25_25") (pintype "passive"))
      (node (ref "U$43") (pin "7") (pinfunction "SCL_7") (pintype "bidirectional"))
    )
    (net (code "173") (name "/SCL75") (class "Default")
      (node (ref "SV4") (pin "26") (pinfunction "26_26") (pintype "passive"))
      (node (ref "U$44") (pin "7") (pinfunction "SCL_7") (pintype "bidirectional"))
    )
    (net (code "174") (name "/SCL76") (class "Default")
      (node (ref "SV4") (pin "31") (pinfunction "31_31") (pintype "passive"))
      (node (ref "U$45") (pin "7") (pinfunction "SCL_7") (pintype "bidirectional"))
    )
    (net (code "175") (name "/SCL77") (class "Default")
      (node (ref "SV4") (pin "32") (pinfunction "32_32") (pintype "passive"))
      (node (ref "U$46") (pin "7") (pinfunction "SCL_7") (pintype "bidirectional"))
    )
    (net (code "176") (name "/SCL78") (class "Default")
      (node (ref "SV4") (pin "37") (pinfunction "37_37") (pintype "passive"))
      (node (ref "U$47") (pin "7") (pinfunction "SCL_7") (pintype "bidirectional"))
    )
    (net (code "177") (name "/SCL79") (class "Default")
      (node (ref "SV5") (pin "1") (pinfunction "1_1") (pintype "passive"))
      (node (ref "U$48") (pin "7") (pinfunction "SCL_7") (pintype "bidirectional"))
    )
    (net (code "178") (name "/SCL80") (class "Default")
      (node (ref "SV7") (pin "20") (pinfunction "20_20") (pintype "passive"))
      (node (ref "U$81") (pin "7") (pinfunction "SCL_7") (pintype "bidirectional"))
    )
    (net (code "179") (name "/SCL81") (class "Default")
      (node (ref "SV7") (pin "25") (pinfunction "25_25") (pintype "passive"))
      (node (ref "U$82") (pin "7") (pinfunction "SCL_7") (pintype "bidirectional"))
    )
    (net (code "180") (name "/SCL82") (class "Default")
      (node (ref "SV7") (pin "26") (pinfunction "26_26") (pintype "passive"))
      (node (ref "U$83") (pin "7") (pinfunction "SCL_7") (pintype "bidirectional"))
    )
    (net (code "181") (name "/SCL83") (class "Default")
      (node (ref "SV7") (pin "31") (pinfunction "31_31") (pintype "passive"))
      (node (ref "U$84") (pin "7") (pinfunction "SCL_7") (pintype "bidirectional"))
    )
    (net (code "182") (name "/SCL84") (class "Default")
      (node (ref "SV7") (pin "32") (pinfunction "32_32") (pintype "passive"))
      (node (ref "U$85") (pin "7") (pinfunction "SCL_7") (pintype "bidirectional"))
    )
    (net (code "183") (name "/SCL85") (class "Default")
      (node (ref "SV7") (pin "37") (pinfunction "37_37") (pintype "passive"))
      (node (ref "U$86") (pin "7") (pinfunction "SCL_7") (pintype "bidirectional"))
    )
    (net (code "184") (name "/SCL86") (class "Default")
      (node (ref "SV8") (pin "1") (pinfunction "1_1") (pintype "passive"))
      (node (ref "U$87") (pin "7") (pinfunction "SCL_7") (pintype "bidirectional"))
    )
    (net (code "185") (name "/SCL87") (class "Default")
      (node (ref "SV8") (pin "2") (pinfunction "2_2") (pintype "passive"))
      (node (ref "U$88") (pin "7") (pinfunction "SCL_7") (pintype "bidirectional"))
    )
    (net (code "186") (name "/SCL88") (class "Default")
      (node (ref "SV8") (pin "7") (pinfunction "7_7") (pintype "passive"))
      (node (ref "U$89") (pin "7") (pinfunction "SCL_7") (pintype "bidirectional"))
    )
    (net (code "187") (name "/SCL89") (class "Default")
      (node (ref "SV8") (pin "8") (pinfunction "8_8") (pintype "passive"))
      (node (ref "U$90") (pin "7") (pinfunction "SCL_7") (pintype "bidirectional"))
    )
    (net (code "188") (name "/SCL90") (class "Default")
      (node (ref "SV8") (pin "13") (pinfunction "13_13") (pintype "passive"))
      (node (ref "U$91") (pin "7") (pinfunction "SCL_7") (pintype "bidirectional"))
    )
    (net (code "189") (name "/SCL91") (class "Default")
      (node (ref "SV8") (pin "14") (pinfunction "14_14") (pintype "passive"))
      (node (ref "U$92") (pin "7") (pinfunction "SCL_7") (pintype "bidirectional"))
    )
    (net (code "190") (name "/SCL92") (class "Default")
      (node (ref "SV8") (pin "19") (pinfunction "19_19") (pintype "passive"))
      (node (ref "U$93") (pin "7") (pinfunction "SCL_7") (pintype "bidirectional"))
    )
    (net (code "191") (name "/SCL93") (class "Default")
      (node (ref "SV8") (pin "20") (pinfunction "20_20") (pintype "passive"))
      (node (ref "U$94") (pin "7") (pinfunction "SCL_7") (pintype "bidirectional"))
    )
    (net (code "192") (name "/SCL94") (class "Default")
      (node (ref "SV8") (pin "25") (pinfunction "25_25") (pintype "passive"))
      (node (ref "U$95") (pin "7") (pinfunction "SCL_7") (pintype "bidirectional"))
    )
    (net (code "193") (name "/SCL95") (class "Default")
      (node (ref "SV8") (pin "26") (pinfunction "26_26") (pintype "passive"))
      (node (ref "U$96") (pin "7") (pinfunction "SCL_7") (pintype "bidirectional"))
      (node (ref "U5") (pin "4") (pinfunction "SCK_4") (pintype "passive"))
      (node (ref "U6") (pin "6") (pinfunction "SCL_6") (pintype "input"))
    )
    (net (code "194") (name "/SDA0") (class "Default")
      (node (ref "SV1") (pin "19") (pinfunction "19_19") (pintype "passive"))
      (node (ref "U$1") (pin "8") (pinfunction "SDA_8") (pintype "bidirectional"))
    )
    (net (code "195") (name "/SDA1") (class "Default")
      (node (ref "SV1") (pin "20") (pinfunction "20_20") (pintype "passive"))
      (node (ref "U$2") (pin "8") (pinfunction "SDA_8") (pintype "bidirectional"))
    )
    (net (code "196") (name "/SDA2") (class "Default")
      (node (ref "SV1") (pin "25") (pinfunction "25_25") (pintype "passive"))
      (node (ref "U$3") (pin "8") (pinfunction "SDA_8") (pintype "bidirectional"))
    )
    (net (code "197") (name "/SDA3") (class "Default")
      (node (ref "SV1") (pin "26") (pinfunction "26_26") (pintype "passive"))
      (node (ref "U$4") (pin "8") (pinfunction "SDA_8") (pintype "bidirectional"))
    )
    (net (code "198") (name "/SDA4") (class "Default")
      (node (ref "SV1") (pin "31") (pinfunction "31_31") (pintype "passive"))
      (node (ref "U$5") (pin "8") (pinfunction "SDA_8") (pintype "bidirectional"))
    )
    (net (code "199") (name "/SDA5") (class "Default")
      (node (ref "SV1") (pin "32") (pinfunction "32_32") (pintype "passive"))
      (node (ref "U$6") (pin "8") (pinfunction "SDA_8") (pintype "bidirectional"))
    )
    (net (code "200") (name "/SDA6") (class "Default")
      (node (ref "SV1") (pin "37") (pinfunction "37_37") (pintype "passive"))
      (node (ref "U$7") (pin "8") (pinfunction "SDA_8") (pintype "bidirectional"))
    )
    (net (code "201") (name "/SDA7") (class "Default")
      (node (ref "SV1") (pin "38") (pinfunction "38_38") (pintype "passive"))
      (node (ref "U$8") (pin "8") (pinfunction "SDA_8") (pintype "bidirectional"))
    )
    (net (code "202") (name "/SDA8") (class "Default")
      (node (ref "SV2") (pin "3") (pinfunction "3_3") (pintype "passive"))
      (node (ref "U$9") (pin "8") (pinfunction "SDA_8") (pintype "bidirectional"))
    )
    (net (code "203") (name "/SDA9") (class "Default")
      (node (ref "SV2") (pin "4") (pinfunction "4_4") (pintype "passive"))
      (node (ref "U$10") (pin "8") (pinfunction "SDA_8") (pintype "bidirectional"))
    )
    (net (code "204") (name "/SDA10") (class "Default")
      (node (ref "SV2") (pin "9") (pinfunction "9_9") (pintype "passive"))
      (node (ref "U$11") (pin "8") (pinfunction "SDA_8") (pintype "bidirectional"))
    )
    (net (code "205") (name "/SDA11") (class "Default")
      (node (ref "SV2") (pin "10") (pinfunction "10_10") (pintype "passive"))
      (node (ref "U$12") (pin "8") (pinfunction "SDA_8") (pintype "bidirectional"))
    )
    (net (code "206") (name "/SDA12") (class "Default")
      (node (ref "SV2") (pin "15") (pinfunction "15_15") (pintype "passive"))
      (node (ref "U$13") (pin "8") (pinfunction "SDA_8") (pintype "bidirectional"))
    )
    (net (code "207") (name "/SDA13") (class "Default")
      (node (ref "SV2") (pin "16") (pinfunction "16_16") (pintype "passive"))
      (node (ref "U$14") (pin "8") (pinfunction "SDA_8") (pintype "bidirectional"))
    )
    (net (code "208") (name "/SDA14") (class "Default")
      (node (ref "SV2") (pin "21") (pinfunction "21_21") (pintype "passive"))
      (node (ref "U$15") (pin "8") (pinfunction "SDA_8") (pintype "bidirectional"))
    )
    (net (code "209") (name "/SDA15") (class "Default")
      (node (ref "SV2") (pin "22") (pinfunction "22_22") (pintype "passive"))
      (node (ref "U$16") (pin "8") (pinfunction "SDA_8") (pintype "bidirectional"))
    )
    (net (code "210") (name "/SDA16") (class "Default")
      (node (ref "SV5") (pin "4") (pinfunction "4_4") (pintype "passive"))
      (node (ref "U$49") (pin "8") (pinfunction "SDA_8") (pintype "bidirectional"))
    )
    (net (code "211") (name "/SDA17") (class "Default")
      (node (ref "SV5") (pin "9") (pinfunction "9_9") (pintype "passive"))
      (node (ref "U$50") (pin "8") (pinfunction "SDA_8") (pintype "bidirectional"))
    )
    (net (code "212") (name "/SDA18") (class "Default")
      (node (ref "SV5") (pin "10") (pinfunction "10_10") (pintype "passive"))
      (node (ref "U$51") (pin "8") (pinfunction "SDA_8") (pintype "bidirectional"))
    )
    (net (code "213") (name "/SDA19") (class "Default")
      (node (ref "SV5") (pin "15") (pinfunction "15_15") (pintype "passive"))
      (node (ref "U$52") (pin "8") (pinfunction "SDA_8") (pintype "bidirectional"))
    )
    (net (code "214") (name "/SDA20") (class "Default")
      (node (ref "SV5") (pin "16") (pinfunction "16_16") (pintype "passive"))
      (node (ref "U$53") (pin "8") (pinfunction "SDA_8") (pintype "bidirectional"))
    )
    (net (code "215") (name "/SDA21") (class "Default")
      (node (ref "SV5") (pin "21") (pinfunction "21_21") (pintype "passive"))
      (node (ref "U$54") (pin "8") (pinfunction "SDA_8") (pintype "bidirectional"))
    )
    (net (code "216") (name "/SDA22") (class "Default")
      (node (ref "SV5") (pin "22") (pinfunction "22_22") (pintype "passive"))
      (node (ref "U$55") (pin "8") (pinfunction "SDA_8") (pintype "bidirectional"))
    )
    (net (code "217") (name "/SDA23") (class "Default")
      (node (ref "SV5") (pin "27") (pinfunction "27_27") (pintype "passive"))
      (node (ref "U$56") (pin "8") (pinfunction "SDA_8") (pintype "bidirectional"))
    )
    (net (code "218") (name "/SDA24") (class "Default")
      (node (ref "SV5") (pin "28") (pinfunction "28_28") (pintype "passive"))
      (node (ref "U$57") (pin "8") (pinfunction "SDA_8") (pintype "bidirectional"))
    )
    (net (code "219") (name "/SDA25") (class "Default")
      (node (ref "SV5") (pin "33") (pinfunction "33_33") (pintype "passive"))
      (node (ref "U$58") (pin "8") (pinfunction "SDA_8") (pintype "bidirectional"))
    )
    (net (code "220") (name "/SDA26") (class "Default")
      (node (ref "SV5") (pin "34") (pinfunction "34_34") (pintype "passive"))
      (node (ref "U$59") (pin "8") (pinfunction "SDA_8") (pintype "bidirectional"))
    )
    (net (code "221") (name "/SDA27") (class "Default")
      (node (ref "SV5") (pin "39") (pinfunction "39_39") (pintype "passive"))
      (node (ref "U$60") (pin "8") (pinfunction "SDA_8") (pintype "bidirectional"))
    )
    (net (code "222") (name "/SDA28") (class "Default")
      (node (ref "SV6") (pin "3") (pinfunction "3_3") (pintype "passive"))
      (node (ref "U$61") (pin "8") (pinfunction "SDA_8") (pintype "bidirectional"))
    )
    (net (code "223") (name "/SDA29") (class "Default")
      (node (ref "SV6") (pin "4") (pinfunction "4_4") (pintype "passive"))
      (node (ref "U$62") (pin "8") (pinfunction "SDA_8") (pintype "bidirectional"))
    )
    (net (code "224") (name "/SDA30") (class "Default")
      (node (ref "SV6") (pin "9") (pinfunction "9_9") (pintype "passive"))
      (node (ref "U$63") (pin "8") (pinfunction "SDA_8") (pintype "bidirectional"))
    )
    (net (code "225") (name "/SDA31") (class "Default")
      (node (ref "SV6") (pin "10") (pinfunction "10_10") (pintype "passive"))
      (node (ref "U$64") (pin "8") (pinfunction "SDA_8") (pintype "bidirectional"))
      (node (ref "U1") (pin "3") (pinfunction "SDI_3") (pintype "passive"))
      (node (ref "U2") (pin "1") (pinfunction "SDA_1") (pintype "bidirectional"))
    )
    (net (code "226") (name "/SDA32") (class "Default")
      (node (ref "SV2") (pin "27") (pinfunction "27_27") (pintype "passive"))
      (node (ref "U$17") (pin "8") (pinfunction "SDA_8") (pintype "bidirectional"))
    )
    (net (code "227") (name "/SDA33") (class "Default")
      (node (ref "SV2") (pin "28") (pinfunction "28_28") (pintype "passive"))
      (node (ref "U$18") (pin "8") (pinfunction "SDA_8") (pintype "bidirectional"))
    )
    (net (code "228") (name "/SDA34") (class "Default")
      (node (ref "SV2") (pin "33") (pinfunction "33_33") (pintype "passive"))
      (node (ref "U$19") (pin "8") (pinfunction "SDA_8") (pintype "bidirectional"))
    )
    (net (code "229") (name "/SDA35") (class "Default")
      (node (ref "SV2") (pin "34") (pinfunction "34_34") (pintype "passive"))
      (node (ref "U$20") (pin "8") (pinfunction "SDA_8") (pintype "bidirectional"))
    )
    (net (code "230") (name "/SDA36") (class "Default")
      (node (ref "SV2") (pin "39") (pinfunction "39_39") (pintype "passive"))
      (node (ref "U$21") (pin "8") (pinfunction "SDA_8") (pintype "bidirectional"))
    )
    (net (code "231") (name "/SDA37") (class "Default")
      (node (ref "SV3") (pin "3") (pinfunction "3_3") (pintype "passive"))
      (node (ref "U$22") (pin "8") (pinfunction "SDA_8") (pintype "bidirectional"))
    )
    (net (code "232") (name "/SDA38") (class "Default")
      (node (ref "SV3") (pin "4") (pinfunction "4_4") (pintype "passive"))
      (node (ref "U$23") (pin "8") (pinfunction "SDA_8") (pintype "bidirectional"))
    )
    (net (code "233") (name "/SDA39") (class "Default")
      (node (ref "SV3") (pin "9") (pinfunction "9_9") (pintype "passive"))
      (node (ref "U$24") (pin "8") (pinfunction "SDA_8") (pintype "bidirectional"))
    )
    (net (code "234") (name "/SDA40") (class "Default")
      (node (ref "SV3") (pin "10") (pinfunction "10_10") (pintype "passive"))
      (node (ref "U$25") (pin "8") (pinfunction "SDA_8") (pintype "bidirectional"))
    )
    (net (code "235") (name "/SDA41") (class "Default")
      (node (ref "SV3") (pin "15") (pinfunction "15_15") (pintype "passive"))
      (node (ref "U$26") (pin "8") (pinfunction "SDA_8") (pintype "bidirectional"))
    )
    (net (code "236") (name "/SDA42") (class "Default")
      (node (ref "SV3") (pin "16") (pinfunction "16_16") (pintype "passive"))
      (node (ref "U$27") (pin "8") (pinfunction "SDA_8") (pintype "bidirectional"))
    )
    (net (code "237") (name "/SDA43") (class "Default")
      (node (ref "SV3") (pin "21") (pinfunction "21_21") (pintype "passive"))
      (node (ref "U$28") (pin "8") (pinfunction "SDA_8") (pintype "bidirectional"))
    )
    (net (code "238") (name "/SDA44") (class "Default")
      (node (ref "SV3") (pin "22") (pinfunction "22_22") (pintype "passive"))
      (node (ref "U$29") (pin "8") (pinfunction "SDA_8") (pintype "bidirectional"))
    )
    (net (code "239") (name "/SDA45") (class "Default")
      (node (ref "SV3") (pin "27") (pinfunction "27_27") (pintype "passive"))
      (node (ref "U$30") (pin "8") (pinfunction "SDA_8") (pintype "bidirectional"))
    )
    (net (code "240") (name "/SDA46") (class "Default")
      (node (ref "SV3") (pin "28") (pinfunction "28_28") (pintype "passive"))
      (node (ref "U$31") (pin "8") (pinfunction "SDA_8") (pintype "bidirectional"))
    )
    (net (code "241") (name "/SDA47") (class "Default")
      (node (ref "SV3") (pin "33") (pinfunction "33_33") (pintype "passive"))
      (node (ref "U$32") (pin "8") (pinfunction "SDA_8") (pintype "bidirectional"))
    )
    (net (code "242") (name "/SDA48") (class "Default")
      (node (ref "SV6") (pin "15") (pinfunction "15_15") (pintype "passive"))
      (node (ref "U$65") (pin "8") (pinfunction "SDA_8") (pintype "bidirectional"))
    )
    (net (code "243") (name "/SDA49") (class "Default")
      (node (ref "SV6") (pin "16") (pinfunction "16_16") (pintype "passive"))
      (node (ref "U$66") (pin "8") (pinfunction "SDA_8") (pintype "bidirectional"))
    )
    (net (code "244") (name "/SDA50") (class "Default")
      (node (ref "SV6") (pin "21") (pinfunction "21_21") (pintype "passive"))
      (node (ref "U$67") (pin "8") (pinfunction "SDA_8") (pintype "bidirectional"))
    )
    (net (code "245") (name "/SDA51") (class "Default")
      (node (ref "SV6") (pin "22") (pinfunction "22_22") (pintype "passive"))
      (node (ref "U$68") (pin "8") (pinfunction "SDA_8") (pintype "bidirectional"))
    )
    (net (code "246") (name "/SDA52") (class "Default")
      (node (ref "SV6") (pin "27") (pinfunction "27_27") (pintype "passive"))
      (node (ref "U$69") (pin "8") (pinfunction "SDA_8") (pintype "bidirectional"))
    )
    (net (code "247") (name "/SDA53") (class "Default")
      (node (ref "SV6") (pin "28") (pinfunction "28_28") (pintype "passive"))
      (node (ref "U$70") (pin "8") (pinfunction "SDA_8") (pintype "bidirectional"))
    )
    (net (code "248") (name "/SDA54") (class "Default")
      (node (ref "SV6") (pin "33") (pinfunction "33_33") (pintype "passive"))
      (node (ref "U$71") (pin "8") (pinfunction "SDA_8") (pintype "bidirectional"))
    )
    (net (code "249") (name "/SDA55") (class "Default")
      (node (ref "SV6") (pin "34") (pinfunction "34_34") (pintype "passive"))
      (node (ref "U$72") (pin "8") (pinfunction "SDA_8") (pintype "bidirectional"))
    )
    (net (code "250") (name "/SDA56") (class "Default")
      (node (ref "SV6") (pin "39") (pinfunction "39_39") (pintype "passive"))
      (node (ref "U$73") (pin "8") (pinfunction "SDA_8") (pintype "bidirectional"))
    )
    (net (code "251") (name "/SDA57") (class "Default")
      (node (ref "SV7") (pin "3") (pinfunction "3_3") (pintype "passive"))
      (node (ref "U$74") (pin "8") (pinfunction "SDA_8") (pintype "bidirectional"))
    )
    (net (code "252") (name "/SDA58") (class "Default")
      (node (ref "SV7") (pin "4") (pinfunction "4_4") (pintype "passive"))
      (node (ref "U$75") (pin "8") (pinfunction "SDA_8") (pintype "bidirectional"))
    )
    (net (code "253") (name "/SDA59") (class "Default")
      (node (ref "SV7") (pin "9") (pinfunction "9_9") (pintype "passive"))
      (node (ref "U$76") (pin "8") (pinfunction "SDA_8") (pintype "bidirectional"))
    )
    (net (code "254") (name "/SDA60") (class "Default")
      (node (ref "SV7") (pin "10") (pinfunction "10_10") (pintype "passive"))
      (node (ref "U$77") (pin "8") (pinfunction "SDA_8") (pintype "bidirectional"))
    )
    (net (code "255") (name "/SDA61") (class "Default")
      (node (ref "SV7") (pin "15") (pinfunction "15_15") (pintype "passive"))
      (node (ref "U$78") (pin "8") (pinfunction "SDA_8") (pintype "bidirectional"))
    )
    (net (code "256") (name "/SDA62") (class "Default")
      (node (ref "SV7") (pin "16") (pinfunction "16_16") (pintype "passive"))
      (node (ref "U$79") (pin "8") (pinfunction "SDA_8") (pintype "bidirectional"))
    )
    (net (code "257") (name "/SDA63") (class "Default")
      (node (ref "SV7") (pin "21") (pinfunction "21_21") (pintype "passive"))
      (node (ref "U$80") (pin "8") (pinfunction "SDA_8") (pintype "bidirectional"))
      (node (ref "U3") (pin "3") (pinfunction "SDI_3") (pintype "passive"))
      (node (ref "U4") (pin "1") (pinfunction "SDA_1") (pintype "bidirectional"))
    )
    (net (code "258") (name "/SDA64") (class "Default")
      (node (ref "SV3") (pin "34") (pinfunction "34_34") (pintype "passive"))
      (node (ref "U$33") (pin "8") (pinfunction "SDA_8") (pintype "bidirectional"))
    )
    (net (code "259") (name "/SDA65") (class "Default")
      (node (ref "SV3") (pin "39") (pinfunction "39_39") (pintype "passive"))
      (node (ref "U$34") (pin "8") (pinfunction "SDA_8") (pintype "bidirectional"))
    )
    (net (code "260") (name "/SDA66") (class "Default")
      (node (ref "SV4") (pin "3") (pinfunction "3_3") (pintype "passive"))
      (node (ref "U$35") (pin "8") (pinfunction "SDA_8") (pintype "bidirectional"))
    )
    (net (code "261") (name "/SDA67") (class "Default")
      (node (ref "SV4") (pin "4") (pinfunction "4_4") (pintype "passive"))
      (node (ref "U$36") (pin "8") (pinfunction "SDA_8") (pintype "bidirectional"))
    )
    (net (code "262") (name "/SDA68") (class "Default")
      (node (ref "SV4") (pin "9") (pinfunction "9_9") (pintype "passive"))
      (node (ref "U$37") (pin "8") (pinfunction "SDA_8") (pintype "bidirectional"))
    )
    (net (code "263") (name "/SDA69") (class "Default")
      (node (ref "SV4") (pin "10") (pinfunction "10_10") (pintype "passive"))
      (node (ref "U$38") (pin "8") (pinfunction "SDA_8") (pintype "bidirectional"))
    )
    (net (code "264") (name "/SDA70") (class "Default")
      (node (ref "SV4") (pin "15") (pinfunction "15_15") (pintype "passive"))
      (node (ref "U$39") (pin "8") (pinfunction "SDA_8") (pintype "bidirectional"))
    )
    (net (code "265") (name "/SDA71") (class "Default")
      (node (ref "SV4") (pin "16") (pinfunction "16_16") (pintype "passive"))
      (node (ref "U$40") (pin "8") (pinfunction "SDA_8") (pintype "bidirectional"))
    )
    (net (code "266") (name "/SDA72") (class "Default")
      (node (ref "SV4") (pin "21") (pinfunction "21_21") (pintype "passive"))
      (node (ref "U$41") (pin "8") (pinfunction "SDA_8") (pintype "bidirectional"))
    )
    (net (code "267") (name "/SDA73") (class "Default")
      (node (ref "SV4") (pin "22") (pinfunction "22_22") (pintype "passive"))
      (node (ref "U$42") (pin "8") (pinfunction "SDA_8") (pintype "bidirectional"))
    )
    (net (code "268") (name "/SDA74") (class "Default")
      (node (ref "SV4") (pin "27") (pinfunction "27_27") (pintype "passive"))
      (node (ref "U$43") (pin "8") (pinfunction "SDA_8") (pintype "bidirectional"))
    )
    (net (code "269") (name "/SDA75") (class "Default")
      (node (ref "SV4") (pin "28") (pinfunction "28_28") (pintype "passive"))
      (node (ref "U$44") (pin "8") (pinfunction "SDA_8") (pintype "bidirectional"))
    )
    (net (code "270") (name "/SDA76") (class "Default")
      (node (ref "SV4") (pin "33") (pinfunction "33_33") (pintype "passive"))
      (node (ref "U$45") (pin "8") (pinfunction "SDA_8") (pintype "bidirectional"))
    )
    (net (code "271") (name "/SDA77") (class "Default")
      (node (ref "SV4") (pin "34") (pinfunction "34_34") (pintype "passive"))
      (node (ref "U$46") (pin "8") (pinfunction "SDA_8") (pintype "bidirectional"))
    )
    (net (code "272") (name "/SDA78") (class "Default")
      (node (ref "SV4") (pin "39") (pinfunction "39_39") (pintype "passive"))
      (node (ref "U$47") (pin "8") (pinfunction "SDA_8") (pintype "bidirectional"))
    )
    (net (code "273") (name "/SDA79") (class "Default")
      (node (ref "SV5") (pin "3") (pinfunction "3_3") (pintype "passive"))
      (node (ref "U$48") (pin "8") (pinfunction "SDA_8") (pintype "bidirectional"))
    )
    (net (code "274") (name "/SDA80") (class "Default")
      (node (ref "SV7") (pin "22") (pinfunction "22_22") (pintype "passive"))
      (node (ref "U$81") (pin "8") (pinfunction "SDA_8") (pintype "bidirectional"))
    )
    (net (code "275") (name "/SDA81") (class "Default")
      (node (ref "SV7") (pin "27") (pinfunction "27_27") (pintype "passive"))
      (node (ref "U$82") (pin "8") (pinfunction "SDA_8") (pintype "bidirectional"))
    )
    (net (code "276") (name "/SDA82") (class "Default")
      (node (ref "SV7") (pin "28") (pinfunction "28_28") (pintype "passive"))
      (node (ref "U$83") (pin "8") (pinfunction "SDA_8") (pintype "bidirectional"))
    )
    (net (code "277") (name "/SDA83") (class "Default")
      (node (ref "SV7") (pin "33") (pinfunction "33_33") (pintype "passive"))
      (node (ref "U$84") (pin "8") (pinfunction "SDA_8") (pintype "bidirectional"))
    )
    (net (code "278") (name "/SDA84") (class "Default")
      (node (ref "SV7") (pin "34") (pinfunction "34_34") (pintype "passive"))
      (node (ref "U$85") (pin "8") (pinfunction "SDA_8") (pintype "bidirectional"))
    )
    (net (code "279") (name "/SDA85") (class "Default")
      (node (ref "SV7") (pin "39") (pinfunction "39_39") (pintype "passive"))
      (node (ref "U$86") (pin "8") (pinfunction "SDA_8") (pintype "bidirectional"))
    )
    (net (code "280") (name "/SDA86") (class "Default")
      (node (ref "SV8") (pin "3") (pinfunction "3_3") (pintype "passive"))
      (node (ref "U$87") (pin "8") (pinfunction "SDA_8") (pintype "bidirectional"))
    )
    (net (code "281") (name "/SDA87") (class "Default")
      (node (ref "SV8") (pin "4") (pinfunction "4_4") (pintype "passive"))
      (node (ref "U$88") (pin "8") (pinfunction "SDA_8") (pintype "bidirectional"))
    )
    (net (code "282") (name "/SDA88") (class "Default")
      (node (ref "SV8") (pin "9") (pinfunction "9_9") (pintype "passive"))
      (node (ref "U$89") (pin "8") (pinfunction "SDA_8") (pintype "bidirectional"))
    )
    (net (code "283") (name "/SDA89") (class "Default")
      (node (ref "SV8") (pin "10") (pinfunction "10_10") (pintype "passive"))
      (node (ref "U$90") (pin "8") (pinfunction "SDA_8") (pintype "bidirectional"))
    )
    (net (code "284") (name "/SDA90") (class "Default")
      (node (ref "SV8") (pin "15") (pinfunction "15_15") (pintype "passive"))
      (node (ref "U$91") (pin "8") (pinfunction "SDA_8") (pintype "bidirectional"))
    )
    (net (code "285") (name "/SDA91") (class "Default")
      (node (ref "SV8") (pin "16") (pinfunction "16_16") (pintype "passive"))
      (node (ref "U$92") (pin "8") (pinfunction "SDA_8") (pintype "bidirectional"))
    )
    (net (code "286") (name "/SDA92") (class "Default")
      (node (ref "SV8") (pin "21") (pinfunction "21_21") (pintype "passive"))
      (node (ref "U$93") (pin "8") (pinfunction "SDA_8") (pintype "bidirectional"))
    )
    (net (code "287") (name "/SDA93") (class "Default")
      (node (ref "SV8") (pin "22") (pinfunction "22_22") (pintype "passive"))
      (node (ref "U$94") (pin "8") (pinfunction "SDA_8") (pintype "bidirectional"))
    )
    (net (code "288") (name "/SDA94") (class "Default")
      (node (ref "SV8") (pin "27") (pinfunction "27_27") (pintype "passive"))
      (node (ref "U$95") (pin "8") (pinfunction "SDA_8") (pintype "bidirectional"))
    )
    (net (code "289") (name "/SDA95") (class "Default")
      (node (ref "SV8") (pin "28") (pinfunction "28_28") (pintype "passive"))
      (node (ref "U$96") (pin "8") (pinfunction "SDA_8") (pintype "bidirectional"))
      (node (ref "U5") (pin "3") (pinfunction "SDI_3") (pintype "passive"))
      (node (ref "U6") (pin "1") (pinfunction "SDA_1") (pintype "bidirectional"))
    )
    (net (code "290") (name "GND") (class "Default")
      (node (ref "C1") (pin "2") (pinfunction "2_2") (pintype "passive"))
      (node (ref "C10") (pin "2") (pinfunction "2_2") (pintype "passive"))
      (node (ref "C100") (pin "2") (pinfunction "2_2") (pintype "passive"))
      (node (ref "C101") (pin "2") (pinfunction "2_2") (pintype "passive"))
      (node (ref "C102") (pin "2") (pinfunction "2_2") (pintype "passive"))
      (node (ref "C103") (pin "2") (pinfunction "2_2") (pintype "passive"))
      (node (ref "C104") (pin "2") (pinfunction "2_2") (pintype "passive"))
      (node (ref "C105") (pin "2") (pinfunction "2_2") (pintype "passive"))
      (node (ref "C106") (pin "2") (pinfunction "2_2") (pintype "passive"))
      (node (ref "C107") (pin "2") (pinfunction "2_2") (pintype "passive"))
      (node (ref "C108") (pin "2") (pinfunction "2_2") (pintype "passive"))
      (node (ref "C109") (pin "2") (pinfunction "2_2") (pintype "passive"))
      (node (ref "C11") (pin "2") (pinfunction "2_2") (pintype "passive"))
      (node (ref "C110") (pin "2") (pinfunction "2_2") (pintype "passive"))
      (node (ref "C111") (pin "2") (pinfunction "2_2") (pintype "passive"))
      (node (ref "C112") (pin "2") (pinfunction "2_2") (pintype "passive"))
      (node (ref "C113") (pin "2") (pinfunction "2_2") (pintype "passive"))
      (node (ref "C114") (pin "2") (pinfunction "2_2") (pintype "passive"))
      (node (ref "C115") (pin "2") (pinfunction "2_2") (pintype "passive"))
      (node (ref "C116") (pin "2") (pinfunction "2_2") (pintype "passive"))
      (node (ref "C117") (pin "2") (pinfunction "2_2") (pintype "passive"))
      (node (ref "C118") (pin "2") (pinfunction "2_2") (pintype "passive"))
      (node (ref "C119") (pin "2") (pinfunction "2_2") (pintype "passive"))
      (node (ref "C12") (pin "2") (pinfunction "2_2") (pintype "passive"))
      (node (ref "C120") (pin "2") (pinfunction "2_2") (pintype "passive"))
      (node (ref "C121") (pin "2") (pinfunction "2_2") (pintype "passive"))
      (node (ref "C122") (pin "2") (pinfunction "2_2") (pintype "passive"))
      (node (ref "C123") (pin "2") (pinfunction "2_2") (pintype "passive"))
      (node (ref "C124") (pin "2") (pinfunction "2_2") (pintype "passive"))
      (node (ref "C125") (pin "2") (pinfunction "2_2") (pintype "passive"))
      (node (ref "C126") (pin "2") (pinfunction "2_2") (pintype "passive"))
      (node (ref "C127") (pin "2") (pinfunction "2_2") (pintype "passive"))
      (node (ref "C128") (pin "2") (pinfunction "2_2") (pintype "passive"))
      (node (ref "C129") (pin "2") (pinfunction "2_2") (pintype "passive"))
      (node (ref "C13") (pin "2") (pinfunction "2_2") (pintype "passive"))
      (node (ref "C130") (pin "2") (pinfunction "2_2") (pintype "passive"))
      (node (ref "C131") (pin "2") (pinfunction "2_2") (pintype "passive"))
      (node (ref "C132") (pin "2") (pinfunction "2_2") (pintype "passive"))
      (node (ref "C133") (pin "2") (pinfunction "2_2") (pintype "passive"))
      (node (ref "C134") (pin "2") (pinfunction "2_2") (pintype "passive"))
      (node (ref "C135") (pin "2") (pinfunction "2_2") (pintype "passive"))
      (node (ref "C136") (pin "2") (pinfunction "2_2") (pintype "passive"))
      (node (ref "C137") (pin "2") (pinfunction "2_2") (pintype "passive"))
      (node (ref "C138") (pin "2") (pinfunction "2_2") (pintype "passive"))
      (node (ref "C139") (pin "2") (pinfunction "2_2") (pintype "passive"))
      (node (ref "C14") (pin "2") (pinfunction "2_2") (pintype "passive"))
      (node (ref "C140") (pin "2") (pinfunction "2_2") (pintype "passive"))
      (node (ref "C141") (pin "2") (pinfunction "2_2") (pintype "passive"))
      (node (ref "C142") (pin "2") (pinfunction "2_2") (pintype "passive"))
      (node (ref "C143") (pin "2") (pinfunction "2_2") (pintype "passive"))
      (node (ref "C144") (pin "2") (pinfunction "2_2") (pintype "passive"))
      (node (ref "C145") (pin "2") (pinfunction "2_2") (pintype "passive"))
      (node (ref "C146") (pin "2") (pinfunction "2_2") (pintype "passive"))
      (node (ref "C147") (pin "2") (pinfunction "2_2") (pintype "passive"))
      (node (ref "C148") (pin "2") (pinfunction "2_2") (pintype "passive"))
      (node (ref "C149") (pin "2") (pinfunction "2_2") (pintype "passive"))
      (node (ref "C15") (pin "2") (pinfunction "2_2") (pintype "passive"))
      (node (ref "C150") (pin "2") (pinfunction "2_2") (pintype "passive"))
      (node (ref "C151") (pin "2") (pinfunction "2_2") (pintype "passive"))
      (node (ref "C152") (pin "2") (pinfunction "2_2") (pintype "passive"))
      (node (ref "C153") (pin "2") (pinfunction "2_2") (pintype "passive"))
      (node (ref "C154") (pin "2") (pinfunction "2_2") (pintype "passive"))
      (node (ref "C155") (pin "2") (pinfunction "2_2") (pintype "passive"))
      (node (ref "C156") (pin "2") (pinfunction "2_2") (pintype "passive"))
      (node (ref "C157") (pin "2") (pinfunction "2_2") (pintype "passive"))
      (node (ref "C158") (pin "2") (pinfunction "2_2") (pintype "passive"))
      (node (ref "C159") (pin "2") (pinfunction "2_2") (pintype "passive"))
      (node (ref "C16") (pin "2") (pinfunction "2_2") (pintype "passive"))
      (node (ref "C160") (pin "2") (pinfunction "2_2") (pintype "passive"))
      (node (ref "C161") (pin "2") (pinfunction "2_2") (pintype "passive"))
      (node (ref "C162") (pin "2") (pinfunction "2_2") (pintype "passive"))
      (node (ref "C163") (pin "2") (pinfunction "2_2") (pintype "passive"))
      (node (ref "C164") (pin "2") (pinfunction "2_2") (pintype "passive"))
      (node (ref "C165") (pin "2") (pinfunction "2_2") (pintype "passive"))
      (node (ref "C166") (pin "2") (pinfunction "2_2") (pintype "passive"))
      (node (ref "C167") (pin "2") (pinfunction "2_2") (pintype "passive"))
      (node (ref "C168") (pin "2") (pinfunction "2_2") (pintype "passive"))
      (node (ref "C169") (pin "2") (pinfunction "2_2") (pintype "passive"))
      (node (ref "C17") (pin "2") (pinfunction "2_2") (pintype "passive"))
      (node (ref "C170") (pin "2") (pinfunction "2_2") (pintype "passive"))
      (node (ref "C171") (pin "2") (pinfunction "2_2") (pintype "passive"))
      (node (ref "C172") (pin "2") (pinfunction "2_2") (pintype "passive"))
      (node (ref "C173") (pin "2") (pinfunction "2_2") (pintype "passive"))
      (node (ref "C174") (pin "2") (pinfunction "2_2") (pintype "passive"))
      (node (ref "C175") (pin "2") (pinfunction "2_2") (pintype "passive"))
      (node (ref "C176") (pin "2") (pinfunction "2_2") (pintype "passive"))
      (node (ref "C177") (pin "2") (pinfunction "2_2") (pintype "passive"))
      (node (ref "C178") (pin "2") (pinfunction "2_2") (pintype "passive"))
      (node (ref "C179") (pin "2") (pinfunction "2_2") (pintype "passive"))
      (node (ref "C18") (pin "2") (pinfunction "2_2") (pintype "passive"))
      (node (ref "C180") (pin "2") (pinfunction "2_2") (pintype "passive"))
      (node (ref "C181") (pin "2") (pinfunction "2_2") (pintype "passive"))
      (node (ref "C182") (pin "2") (pinfunction "2_2") (pintype "passive"))
      (node (ref "C183") (pin "2") (pinfunction "2_2") (pintype "passive"))
      (node (ref "C184") (pin "2") (pinfunction "2_2") (pintype "passive"))
      (node (ref "C185") (pin "2") (pinfunction "2_2") (pintype "passive"))
      (node (ref "C186") (pin "2") (pinfunction "2_2") (pintype "passive"))
      (node (ref "C187") (pin "2") (pinfunction "2_2") (pintype "passive"))
      (node (ref "C188") (pin "2") (pinfunction "2_2") (pintype "passive"))
      (node (ref "C189") (pin "2") (pinfunction "2_2") (pintype "passive"))
      (node (ref "C19") (pin "2") (pinfunction "2_2") (pintype "passive"))
      (node (ref "C190") (pin "2") (pinfunction "2_2") (pintype "passive"))
      (node (ref "C191") (pin "2") (pinfunction "2_2") (pintype "passive"))
      (node (ref "C192") (pin "2") (pinfunction "2_2") (pintype "passive"))
      (node (ref "C2") (pin "2") (pinfunction "2_2") (pintype "passive"))
      (node (ref "C20") (pin "2") (pinfunction "2_2") (pintype "passive"))
      (node (ref "C21") (pin "2") (pinfunction "2_2") (pintype "passive"))
      (node (ref "C22") (pin "2") (pinfunction "2_2") (pintype "passive"))
      (node (ref "C23") (pin "2") (pinfunction "2_2") (pintype "passive"))
      (node (ref "C24") (pin "2") (pinfunction "2_2") (pintype "passive"))
      (node (ref "C25") (pin "2") (pinfunction "2_2") (pintype "passive"))
      (node (ref "C26") (pin "2") (pinfunction "2_2") (pintype "passive"))
      (node (ref "C27") (pin "2") (pinfunction "2_2") (pintype "passive"))
      (node (ref "C28") (pin "2") (pinfunction "2_2") (pintype "passive"))
      (node (ref "C29") (pin "2") (pinfunction "2_2") (pintype "passive"))
      (node (ref "C3") (pin "2") (pinfunction "2_2") (pintype "passive"))
      (node (ref "C30") (pin "2") (pinfunction "2_2") (pintype "passive"))
      (node (ref "C31") (pin "2") (pinfunction "2_2") (pintype "passive"))
      (node (ref "C32") (pin "2") (pinfunction "2_2") (pintype "passive"))
      (node (ref "C33") (pin "2") (pinfunction "2_2") (pintype "passive"))
      (node (ref "C34") (pin "2") (pinfunction "2_2") (pintype "passive"))
      (node (ref "C35") (pin "2") (pinfunction "2_2") (pintype "passive"))
      (node (ref "C36") (pin "2") (pinfunction "2_2") (pintype "passive"))
      (node (ref "C37") (pin "2") (pinfunction "2_2") (pintype "passive"))
      (node (ref "C38") (pin "2") (pinfunction "2_2") (pintype "passive"))
      (node (ref "C39") (pin "2") (pinfunction "2_2") (pintype "passive"))
      (node (ref "C4") (pin "2") (pinfunction "2_2") (pintype "passive"))
      (node (ref "C40") (pin "2") (pinfunction "2_2") (pintype "passive"))
      (node (ref "C41") (pin "2") (pinfunction "2_2") (pintype "passive"))
      (node (ref "C42") (pin "2") (pinfunction "2_2") (pintype "passive"))
      (node (ref "C43") (pin "2") (pinfunction "2_2") (pintype "passive"))
      (node (ref "C44") (pin "2") (pinfunction "2_2") (pintype "passive"))
      (node (ref "C45") (pin "2") (pinfunction "2_2") (pintype "passive"))
      (node (ref "C46") (pin "2") (pinfunction "2_2") (pintype "passive"))
      (node (ref "C47") (pin "2") (pinfunction "2_2") (pintype "passive"))
      (node (ref "C48") (pin "2") (pinfunction "2_2") (pintype "passive"))
      (node (ref "C49") (pin "2") (pinfunction "2_2") (pintype "passive"))
      (node (ref "C5") (pin "2") (pinfunction "2_2") (pintype "passive"))
      (node (ref "C50") (pin "2") (pinfunction "2_2") (pintype "passive"))
      (node (ref "C51") (pin "2") (pinfunction "2_2") (pintype "passive"))
      (node (ref "C52") (pin "2") (pinfunction "2_2") (pintype "passive"))
      (node (ref "C53") (pin "2") (pinfunction "2_2") (pintype "passive"))
      (node (ref "C54") (pin "2") (pinfunction "2_2") (pintype "passive"))
      (node (ref "C55") (pin "2") (pinfunction "2_2") (pintype "passive"))
      (node (ref "C56") (pin "2") (pinfunction "2_2") (pintype "passive"))
      (node (ref "C57") (pin "2") (pinfunction "2_2") (pintype "passive"))
      (node (ref "C58") (pin "2") (pinfunction "2_2") (pintype "passive"))
      (node (ref "C59") (pin "2") (pinfunction "2_2") (pintype "passive"))
      (node (ref "C6") (pin "2") (pinfunction "2_2") (pintype "passive"))
      (node (ref "C60") (pin "2") (pinfunction "2_2") (pintype "passive"))
      (node (ref "C61") (pin "2") (pinfunction "2_2") (pintype "passive"))
      (node (ref "C62") (pin "2") (pinfunction "2_2") (pintype "passive"))
      (node (ref "C63") (pin "2") (pinfunction "2_2") (pintype "passive"))
      (node (ref "C64") (pin "2") (pinfunction "2_2") (pintype "passive"))
      (node (ref "C65") (pin "2") (pinfunction "2_2") (pintype "passive"))
      (node (ref "C66") (pin "2") (pinfunction "2_2") (pintype "passive"))
      (node (ref "C67") (pin "2") (pinfunction "2_2") (pintype "passive"))
      (node (ref "C68") (pin "2") (pinfunction "2_2") (pintype "passive"))
      (node (ref "C69") (pin "2") (pinfunction "2_2") (pintype "passive"))
      (node (ref "C7") (pin "2") (pinfunction "2_2") (pintype "passive"))
      (node (ref "C70") (pin "2") (pinfunction "2_2") (pintype "passive"))
      (node (ref "C71") (pin "2") (pinfunction "2_2") (pintype "passive"))
      (node (ref "C72") (pin "2") (pinfunction "2_2") (pintype "passive"))
      (node (ref "C73") (pin "2") (pinfunction "2_2") (pintype "passive"))
      (node (ref "C74") (pin "2") (pinfunction "2_2") (pintype "passive"))
      (node (ref "C75") (pin "2") (pinfunction "2_2") (pintype "passive"))
      (node (ref "C76") (pin "2") (pinfunction "2_2") (pintype "passive"))
      (node (ref "C77") (pin "2") (pinfunction "2_2") (pintype "passive"))
      (node (ref "C78") (pin "2") (pinfunction "2_2") (pintype "passive"))
      (node (ref "C79") (pin "2") (pinfunction "2_2") (pintype "passive"))
      (node (ref "C8") (pin "2") (pinfunction "2_2") (pintype "passive"))
      (node (ref "C80") (pin "2") (pinfunction "2_2") (pintype "passive"))
      (node (ref "C81") (pin "2") (pinfunction "2_2") (pintype "passive"))
      (node (ref "C82") (pin "2") (pinfunction "2_2") (pintype "passive"))
      (node (ref "C83") (pin "2") (pinfunction "2_2") (pintype "passive"))
      (node (ref "C84") (pin "2") (pinfunction "2_2") (pintype "passive"))
      (node (ref "C85") (pin "2") (pinfunction "2_2") (pintype "passive"))
      (node (ref "C86") (pin "2") (pinfunction "2_2") (pintype "passive"))
      (node (ref "C87") (pin "2") (pinfunction "2_2") (pintype "passive"))
      (node (ref "C88") (pin "2") (pinfunction "2_2") (pintype "passive"))
      (node (ref "C89") (pin "2") (pinfunction "2_2") (pintype "passive"))
      (node (ref "C9") (pin "2") (pinfunction "2_2") (pintype "passive"))
      (node (ref "C90") (pin "2") (pinfunction "2_2") (pintype "passive"))
      (node (ref "C91") (pin "2") (pinfunction "2_2") (pintype "passive"))
      (node (ref "C92") (pin "2") (pinfunction "2_2") (pintype "passive"))
      (node (ref "C93") (pin "2") (pinfunction "2_2") (pintype "passive"))
      (node (ref "C94") (pin "2") (pinfunction "2_2") (pintype "passive"))
      (node (ref "C95") (pin "2") (pinfunction "2_2") (pintype "passive"))
      (node (ref "C96") (pin "2") (pinfunction "2_2") (pintype "passive"))
      (node (ref "C97") (pin "2") (pinfunction "2_2") (pintype "passive"))
      (node (ref "C98") (pin "2") (pinfunction "2_2") (pintype "passive"))
      (node (ref "C99") (pin "2") (pinfunction "2_2") (pintype "passive"))
      (node (ref "SV1") (pin "11") (pinfunction "11_11") (pintype "passive"))
      (node (ref "SV1") (pin "12") (pinfunction "12_12") (pintype "passive"))
      (node (ref "SV1") (pin "13") (pinfunction "13_13") (pintype "passive"))
      (node (ref "SV1") (pin "14") (pinfunction "14_14") (pintype "passive"))
      (node (ref "SV1") (pin "15") (pinfunction "15_15") (pintype "passive"))
      (node (ref "SV1") (pin "16") (pinfunction "16_16") (pintype "passive"))
      (node (ref "SV1") (pin "5") (pinfunction "5_5") (pintype "passive"))
      (node (ref "SV1") (pin "6") (pinfunction "6_6") (pintype "passive"))
      (node (ref "SV2") (pin "40") (pinfunction "40_40") (pintype "passive"))
      (node (ref "SV3") (pin "40") (pinfunction "40_40") (pintype "passive"))
      (node (ref "SV4") (pin "40") (pinfunction "40_40") (pintype "passive"))
      (node (ref "SV5") (pin "40") (pinfunction "40_40") (pintype "passive"))
      (node (ref "SV6") (pin "40") (pinfunction "40_40") (pintype "passive"))
      (node (ref "SV7") (pin "40") (pinfunction "40_40") (pintype "passive"))
      (node (ref "SV8") (pin "31") (pinfunction "31_31") (pintype "passive"))
      (node (ref "SV8") (pin "32") (pinfunction "32_32") (pintype "passive"))
      (node (ref "SV8") (pin "33") (pinfunction "33_33") (pintype "passive"))
      (node (ref "SV8") (pin "34") (pinfunction "34_34") (pintype "passive"))
      (node (ref "SV8") (pin "35") (pinfunction "35_35") (pintype "passive"))
      (node (ref "SV8") (pin "36") (pinfunction "36_36") (pintype "passive"))
      (node (ref "U$1") (pin "10") (pinfunction "GND_10") (pintype "bidirectional"))
      (node (ref "U$1") (pin "2") (pinfunction "VSS_2") (pintype "bidirectional"))
      (node (ref "U$10") (pin "10") (pinfunction "GND_10") (pintype "bidirectional"))
      (node (ref "U$10") (pin "2") (pinfunction "VSS_2") (pintype "bidirectional"))
      (node (ref "U$11") (pin "10") (pinfunction "GND_10") (pintype "bidirectional"))
      (node (ref "U$11") (pin "2") (pinfunction "VSS_2") (pintype "bidirectional"))
      (node (ref "U$12") (pin "10") (pinfunction "GND_10") (pintype "bidirectional"))
      (node (ref "U$12") (pin "2") (pinfunction "VSS_2") (pintype "bidirectional"))
      (node (ref "U$13") (pin "10") (pinfunction "GND_10") (pintype "bidirectional"))
      (node (ref "U$13") (pin "2") (pinfunction "VSS_2") (pintype "bidirectional"))
      (node (ref "U$14") (pin "10") (pinfunction "GND_10") (pintype "bidirectional"))
      (node (ref "U$14") (pin "2") (pinfunction "VSS_2") (pintype "bidirectional"))
      (node (ref "U$15") (pin "10") (pinfunction "GND_10") (pintype "bidirectional"))
      (node (ref "U$15") (pin "2") (pinfunction "VSS_2") (pintype "bidirectional"))
      (node (ref "U$16") (pin "10") (pinfunction "GND_10") (pintype "bidirectional"))
      (node (ref "U$16") (pin "2") (pinfunction "VSS_2") (pintype "bidirectional"))
      (node (ref "U$17") (pin "10") (pinfunction "GND_10") (pintype "bidirectional"))
      (node (ref "U$17") (pin "2") (pinfunction "VSS_2") (pintype "bidirectional"))
      (node (ref "U$18") (pin "10") (pinfunction "GND_10") (pintype "bidirectional"))
      (node (ref "U$18") (pin "2") (pinfunction "VSS_2") (pintype "bidirectional"))
      (node (ref "U$19") (pin "10") (pinfunction "GND_10") (pintype "bidirectional"))
      (node (ref "U$19") (pin "2") (pinfunction "VSS_2") (pintype "bidirectional"))
      (node (ref "U$2") (pin "10") (pinfunction "GND_10") (pintype "bidirectional"))
      (node (ref "U$2") (pin "2") (pinfunction "VSS_2") (pintype "bidirectional"))
      (node (ref "U$20") (pin "10") (pinfunction "GND_10") (pintype "bidirectional"))
      (node (ref "U$20") (pin "2") (pinfunction "VSS_2") (pintype "bidirectional"))
      (node (ref "U$21") (pin "10") (pinfunction "GND_10") (pintype "bidirectional"))
      (node (ref "U$21") (pin "2") (pinfunction "VSS_2") (pintype "bidirectional"))
      (node (ref "U$22") (pin "10") (pinfunction "GND_10") (pintype "bidirectional"))
      (node (ref "U$22") (pin "2") (pinfunction "VSS_2") (pintype "bidirectional"))
      (node (ref "U$23") (pin "10") (pinfunction "GND_10") (pintype "bidirectional"))
      (node (ref "U$23") (pin "2") (pinfunction "VSS_2") (pintype "bidirectional"))
      (node (ref "U$24") (pin "10") (pinfunction "GND_10") (pintype "bidirectional"))
      (node (ref "U$24") (pin "2") (pinfunction "VSS_2") (pintype "bidirectional"))
      (node (ref "U$25") (pin "10") (pinfunction "GND_10") (pintype "bidirectional"))
      (node (ref "U$25") (pin "2") (pinfunction "VSS_2") (pintype "bidirectional"))
      (node (ref "U$26") (pin "10") (pinfunction "GND_10") (pintype "bidirectional"))
      (node (ref "U$26") (pin "2") (pinfunction "VSS_2") (pintype "bidirectional"))
      (node (ref "U$27") (pin "10") (pinfunction "GND_10") (pintype "bidirectional"))
      (node (ref "U$27") (pin "2") (pinfunction "VSS_2") (pintype "bidirectional"))
      (node (ref "U$28") (pin "10") (pinfunction "GND_10") (pintype "bidirectional"))
      (node (ref "U$28") (pin "2") (pinfunction "VSS_2") (pintype "bidirectional"))
      (node (ref "U$29") (pin "10") (pinfunction "GND_10") (pintype "bidirectional"))
      (node (ref "U$29") (pin "2") (pinfunction "VSS_2") (pintype "bidirectional"))
      (node (ref "U$3") (pin "10") (pinfunction "GND_10") (pintype "bidirectional"))
      (node (ref "U$3") (pin "2") (pinfunction "VSS_2") (pintype "bidirectional"))
      (node (ref "U$30") (pin "10") (pinfunction "GND_10") (pintype "bidirectional"))
      (node (ref "U$30") (pin "2") (pinfunction "VSS_2") (pintype "bidirectional"))
      (node (ref "U$31") (pin "10") (pinfunction "GND_10") (pintype "bidirectional"))
      (node (ref "U$31") (pin "2") (pinfunction "VSS_2") (pintype "bidirectional"))
      (node (ref "U$32") (pin "10") (pinfunction "GND_10") (pintype "bidirectional"))
      (node (ref "U$32") (pin "2") (pinfunction "VSS_2") (pintype "bidirectional"))
      (node (ref "U$33") (pin "10") (pinfunction "GND_10") (pintype "bidirectional"))
      (node (ref "U$33") (pin "2") (pinfunction "VSS_2") (pintype "bidirectional"))
      (node (ref "U$34") (pin "10") (pinfunction "GND_10") (pintype "bidirectional"))
      (node (ref "U$34") (pin "2") (pinfunction "VSS_2") (pintype "bidirectional"))
      (node (ref "U$35") (pin "10") (pinfunction "GND_10") (pintype "bidirectional"))
      (node (ref "U$35") (pin "2") (pinfunction "VSS_2") (pintype "bidirectional"))
      (node (ref "U$36") (pin "10") (pinfunction "GND_10") (pintype "bidirectional"))
      (node (ref "U$36") (pin "2") (pinfunction "VSS_2") (pintype "bidirectional"))
      (node (ref "U$37") (pin "10") (pinfunction "GND_10") (pintype "bidirectional"))
      (node (ref "U$37") (pin "2") (pinfunction "VSS_2") (pintype "bidirectional"))
      (node (ref "U$38") (pin "10") (pinfunction "GND_10") (pintype "bidirectional"))
      (node (ref "U$38") (pin "2") (pinfunction "VSS_2") (pintype "bidirectional"))
      (node (ref "U$39") (pin "10") (pinfunction "GND_10") (pintype "bidirectional"))
      (node (ref "U$39") (pin "2") (pinfunction "VSS_2") (pintype "bidirectional"))
      (node (ref "U$4") (pin "10") (pinfunction "GND_10") (pintype "bidirectional"))
      (node (ref "U$4") (pin "2") (pinfunction "VSS_2") (pintype "bidirectional"))
      (node (ref "U$40") (pin "10") (pinfunction "GND_10") (pintype "bidirectional"))
      (node (ref "U$40") (pin "2") (pinfunction "VSS_2") (pintype "bidirectional"))
      (node (ref "U$41") (pin "10") (pinfunction "GND_10") (pintype "bidirectional"))
      (node (ref "U$41") (pin "2") (pinfunction "VSS_2") (pintype "bidirectional"))
      (node (ref "U$42") (pin "10") (pinfunction "GND_10") (pintype "bidirectional"))
      (node (ref "U$42") (pin "2") (pinfunction "VSS_2") (pintype "bidirectional"))
      (node (ref "U$43") (pin "10") (pinfunction "GND_10") (pintype "bidirectional"))
      (node (ref "U$43") (pin "2") (pinfunction "VSS_2") (pintype "bidirectional"))
      (node (ref "U$44") (pin "10") (pinfunction "GND_10") (pintype "bidirectional"))
      (node (ref "U$44") (pin "2") (pinfunction "VSS_2") (pintype "bidirectional"))
      (node (ref "U$45") (pin "10") (pinfunction "GND_10") (pintype "bidirectional"))
      (node (ref "U$45") (pin "2") (pinfunction "VSS_2") (pintype "bidirectional"))
      (node (ref "U$46") (pin "10") (pinfunction "GND_10") (pintype "bidirectional"))
      (node (ref "U$46") (pin "2") (pinfunction "VSS_2") (pintype "bidirectional"))
      (node (ref "U$47") (pin "10") (pinfunction "GND_10") (pintype "bidirectional"))
      (node (ref "U$47") (pin "2") (pinfunction "VSS_2") (pintype "bidirectional"))
      (node (ref "U$48") (pin "10") (pinfunction "GND_10") (pintype "bidirectional"))
      (node (ref "U$48") (pin "2") (pinfunction "VSS_2") (pintype "bidirectional"))
      (node (ref "U$49") (pin "10") (pinfunction "GND_10") (pintype "bidirectional"))
      (node (ref "U$49") (pin "2") (pinfunction "VSS_2") (pintype "bidirectional"))
      (node (ref "U$5") (pin "10") (pinfunction "GND_10") (pintype "bidirectional"))
      (node (ref "U$5") (pin "2") (pinfunction "VSS_2") (pintype "bidirectional"))
      (node (ref "U$50") (pin "10") (pinfunction "GND_10") (pintype "bidirectional"))
      (node (ref "U$50") (pin "2") (pinfunction "VSS_2") (pintype "bidirectional"))
      (node (ref "U$51") (pin "10") (pinfunction "GND_10") (pintype "bidirectional"))
      (node (ref "U$51") (pin "2") (pinfunction "VSS_2") (pintype "bidirectional"))
      (node (ref "U$52") (pin "10") (pinfunction "GND_10") (pintype "bidirectional"))
      (node (ref "U$52") (pin "2") (pinfunction "VSS_2") (pintype "bidirectional"))
      (node (ref "U$53") (pin "10") (pinfunction "GND_10") (pintype "bidirectional"))
      (node (ref "U$53") (pin "2") (pinfunction "VSS_2") (pintype "bidirectional"))
      (node (ref "U$54") (pin "10") (pinfunction "GND_10") (pintype "bidirectional"))
      (node (ref "U$54") (pin "2") (pinfunction "VSS_2") (pintype "bidirectional"))
      (node (ref "U$55") (pin "10") (pinfunction "GND_10") (pintype "bidirectional"))
      (node (ref "U$55") (pin "2") (pinfunction "VSS_2") (pintype "bidirectional"))
      (node (ref "U$56") (pin "10") (pinfunction "GND_10") (pintype "bidirectional"))
      (node (ref "U$56") (pin "2") (pinfunction "VSS_2") (pintype "bidirectional"))
      (node (ref "U$57") (pin "10") (pinfunction "GND_10") (pintype "bidirectional"))
      (node (ref "U$57") (pin "2") (pinfunction "VSS_2") (pintype "bidirectional"))
      (node (ref "U$58") (pin "10") (pinfunction "GND_10") (pintype "bidirectional"))
      (node (ref "U$58") (pin "2") (pinfunction "VSS_2") (pintype "bidirectional"))
      (node (ref "U$59") (pin "10") (pinfunction "GND_10") (pintype "bidirectional"))
      (node (ref "U$59") (pin "2") (pinfunction "VSS_2") (pintype "bidirectional"))
      (node (ref "U$6") (pin "10") (pinfunction "GND_10") (pintype "bidirectional"))
      (node (ref "U$6") (pin "2") (pinfunction "VSS_2") (pintype "bidirectional"))
      (node (ref "U$60") (pin "10") (pinfunction "GND_10") (pintype "bidirectional"))
      (node (ref "U$60") (pin "2") (pinfunction "VSS_2") (pintype "bidirectional"))
      (node (ref "U$61") (pin "10") (pinfunction "GND_10") (pintype "bidirectional"))
      (node (ref "U$61") (pin "2") (pinfunction "VSS_2") (pintype "bidirectional"))
      (node (ref "U$62") (pin "10") (pinfunction "GND_10") (pintype "bidirectional"))
      (node (ref "U$62") (pin "2") (pinfunction "VSS_2") (pintype "bidirectional"))
      (node (ref "U$63") (pin "10") (pinfunction "GND_10") (pintype "bidirectional"))
      (node (ref "U$63") (pin "2") (pinfunction "VSS_2") (pintype "bidirectional"))
      (node (ref "U$64") (pin "10") (pinfunction "GND_10") (pintype "bidirectional"))
      (node (ref "U$64") (pin "2") (pinfunction "VSS_2") (pintype "bidirectional"))
      (node (ref "U$65") (pin "10") (pinfunction "GND_10") (pintype "bidirectional"))
      (node (ref "U$65") (pin "2") (pinfunction "VSS_2") (pintype "bidirectional"))
      (node (ref "U$66") (pin "10") (pinfunction "GND_10") (pintype "bidirectional"))
      (node (ref "U$66") (pin "2") (pinfunction "VSS_2") (pintype "bidirectional"))
      (node (ref "U$67") (pin "10") (pinfunction "GND_10") (pintype "bidirectional"))
      (node (ref "U$67") (pin "2") (pinfunction "VSS_2") (pintype "bidirectional"))
      (node (ref "U$68") (pin "10") (pinfunction "GND_10") (pintype "bidirectional"))
      (node (ref "U$68") (pin "2") (pinfunction "VSS_2") (pintype "bidirectional"))
      (node (ref "U$69") (pin "10") (pinfunction "GND_10") (pintype "bidirectional"))
      (node (ref "U$69") (pin "2") (pinfunction "VSS_2") (pintype "bidirectional"))
      (node (ref "U$7") (pin "10") (pinfunction "GND_10") (pintype "bidirectional"))
      (node (ref "U$7") (pin "2") (pinfunction "VSS_2") (pintype "bidirectional"))
      (node (ref "U$70") (pin "10") (pinfunction "GND_10") (pintype "bidirectional"))
      (node (ref "U$70") (pin "2") (pinfunction "VSS_2") (pintype "bidirectional"))
      (node (ref "U$71") (pin "10") (pinfunction "GND_10") (pintype "bidirectional"))
      (node (ref "U$71") (pin "2") (pinfunction "VSS_2") (pintype "bidirectional"))
      (node (ref "U$72") (pin "10") (pinfunction "GND_10") (pintype "bidirectional"))
      (node (ref "U$72") (pin "2") (pinfunction "VSS_2") (pintype "bidirectional"))
      (node (ref "U$73") (pin "10") (pinfunction "GND_10") (pintype "bidirectional"))
      (node (ref "U$73") (pin "2") (pinfunction "VSS_2") (pintype "bidirectional"))
      (node (ref "U$74") (pin "10") (pinfunction "GND_10") (pintype "bidirectional"))
      (node (ref "U$74") (pin "2") (pinfunction "VSS_2") (pintype "bidirectional"))
      (node (ref "U$75") (pin "10") (pinfunction "GND_10") (pintype "bidirectional"))
      (node (ref "U$75") (pin "2") (pinfunction "VSS_2") (pintype "bidirectional"))
      (node (ref "U$76") (pin "10") (pinfunction "GND_10") (pintype "bidirectional"))
      (node (ref "U$76") (pin "2") (pinfunction "VSS_2") (pintype "bidirectional"))
      (node (ref "U$77") (pin "10") (pinfunction "GND_10") (pintype "bidirectional"))
      (node (ref "U$77") (pin "2") (pinfunction "VSS_2") (pintype "bidirectional"))
      (node (ref "U$78") (pin "10") (pinfunction "GND_10") (pintype "bidirectional"))
      (node (ref "U$78") (pin "2") (pinfunction "VSS_2") (pintype "bidirectional"))
      (node (ref "U$79") (pin "10") (pinfunction "GND_10") (pintype "bidirectional"))
      (node (ref "U$79") (pin "2") (pinfunction "VSS_2") (pintype "bidirectional"))
      (node (ref "U$8") (pin "10") (pinfunction "GND_10") (pintype "bidirectional"))
      (node (ref "U$8") (pin "2") (pinfunction "VSS_2") (pintype "bidirectional"))
      (node (ref "U$80") (pin "10") (pinfunction "GND_10") (pintype "bidirectional"))
      (node (ref "U$80") (pin "2") (pinfunction "VSS_2") (pintype "bidirectional"))
      (node (ref "U$81") (pin "10") (pinfunction "GND_10") (pintype "bidirectional"))
      (node (ref "U$81") (pin "2") (pinfunction "VSS_2") (pintype "bidirectional"))
      (node (ref "U$82") (pin "10") (pinfunction "GND_10") (pintype "bidirectional"))
      (node (ref "U$82") (pin "2") (pinfunction "VSS_2") (pintype "bidirectional"))
      (node (ref "U$83") (pin "10") (pinfunction "GND_10") (pintype "bidirectional"))
      (node (ref "U$83") (pin "2") (pinfunction "VSS_2") (pintype "bidirectional"))
      (node (ref "U$84") (pin "10") (pinfunction "GND_10") (pintype "bidirectional"))
      (node (ref "U$84") (pin "2") (pinfunction "VSS_2") (pintype "bidirectional"))
      (node (ref "U$85") (pin "10") (pinfunction "GND_10") (pintype "bidirectional"))
      (node (ref "U$85") (pin "2") (pinfunction "VSS_2") (pintype "bidirectional"))
      (node (ref "U$86") (pin "10") (pinfunction "GND_10") (pintype "bidirectional"))
      (node (ref "U$86") (pin "2") (pinfunction "VSS_2") (pintype "bidirectional"))
      (node (ref "U$87") (pin "10") (pinfunction "GND_10") (pintype "bidirectional"))
      (node (ref "U$87") (pin "2") (pinfunction "VSS_2") (pintype "bidirectional"))
      (node (ref "U$88") (pin "10") (pinfunction "GND_10") (pintype "bidirectional"))
      (node (ref "U$88") (pin "2") (pinfunction "VSS_2") (pintype "bidirectional"))
      (node (ref "U$89") (pin "10") (pinfunction "GND_10") (pintype "bidirectional"))
      (node (ref "U$89") (pin "2") (pinfunction "VSS_2") (pintype "bidirectional"))
      (node (ref "U$9") (pin "10") (pinfunction "GND_10") (pintype "bidirectional"))
      (node (ref "U$9") (pin "2") (pinfunction "VSS_2") (pintype "bidirectional"))
      (node (ref "U$90") (pin "10") (pinfunction "GND_10") (pintype "bidirectional"))
      (node (ref "U$90") (pin "2") (pinfunction "VSS_2") (pintype "bidirectional"))
      (node (ref "U$91") (pin "10") (pinfunction "GND_10") (pintype "bidirectional"))
      (node (ref "U$91") (pin "2") (pinfunction "VSS_2") (pintype "bidirectional"))
      (node (ref "U$92") (pin "10") (pinfunction "GND_10") (pintype "bidirectional"))
      (node (ref "U$92") (pin "2") (pinfunction "VSS_2") (pintype "bidirectional"))
      (node (ref "U$93") (pin "10") (pinfunction "GND_10") (pintype "bidirectional"))
      (node (ref "U$93") (pin "2") (pinfunction "VSS_2") (pintype "bidirectional"))
      (node (ref "U$94") (pin "10") (pinfunction "GND_10") (pintype "bidirectional"))
      (node (ref "U$94") (pin "2") (pinfunction "VSS_2") (pintype "bidirectional"))
      (node (ref "U$95") (pin "10") (pinfunction "GND_10") (pintype "bidirectional"))
      (node (ref "U$95") (pin "2") (pinfunction "VSS_2") (pintype "bidirectional"))
      (node (ref "U$96") (pin "10") (pinfunction "GND_10") (pintype "bidirectional"))
      (node (ref "U$96") (pin "2") (pinfunction "VSS_2") (pintype "bidirectional"))
      (node (ref "U1") (pin "1") (pinfunction "GND_2_1") (pintype "passive"))
      (node (ref "U1") (pin "7") (pinfunction "GND_7") (pintype "passive"))
      (node (ref "U2") (pin "2") (pinfunction "VSS_2") (pintype "power_in"))
      (node (ref "U2") (pin "7") (pinfunction "VSS_PAD_7") (pintype "bidirectional"))
      (node (ref "U3") (pin "1") (pinfunction "GND_2_1") (pintype "passive"))
      (node (ref "U3") (pin "7") (pinfunction "GND_7") (pintype "passive"))
      (node (ref "U4") (pin "2") (pinfunction "VSS_2") (pintype "power_in"))
      (node (ref "U4") (pin "7") (pinfunction "VSS_PAD_7") (pintype "bidirectional"))
      (node (ref "U5") (pin "1") (pinfunction "GND_2_1") (pintype "passive"))
      (node (ref "U5") (pin "7") (pinfunction "GND_7") (pintype "passive"))
      (node (ref "U6") (pin "2") (pinfunction "VSS_2") (pintype "power_in"))
      (node (ref "U6") (pin "7") (pinfunction "VSS_PAD_7") (pintype "bidirectional"))
    )
    (net (code "291") (name "Net-(U$1-EXT_IN)") (class "Default")
      (node (ref "R1") (pin "2") (pinfunction "2_2") (pintype "passive"))
      (node (ref "U$1") (pin "5") (pinfunction "EXT_IN_5") (pintype "bidirectional"))
    )
    (net (code "292") (name "Net-(U$1-EXT_OUT)") (class "Default")
      (node (ref "R1") (pin "1") (pinfunction "1_1") (pintype "passive"))
      (node (ref "U$1") (pin "6") (pinfunction "EXT_OUT_6") (pintype "bidirectional"))
    )
    (net (code "293") (name "Net-(U$2-EXT_IN)") (class "Default")
      (node (ref "R2") (pin "2") (pinfunction "2_2") (pintype "passive"))
      (node (ref "U$2") (pin "5") (pinfunction "EXT_IN_5") (pintype "bidirectional"))
    )
    (net (code "294") (name "Net-(U$2-EXT_OUT)") (class "Default")
      (node (ref "R2") (pin "1") (pinfunction "1_1") (pintype "passive"))
      (node (ref "U$2") (pin "6") (pinfunction "EXT_OUT_6") (pintype "bidirectional"))
    )
    (net (code "295") (name "Net-(U$3-EXT_IN)") (class "Default")
      (node (ref "R3") (pin "2") (pinfunction "2_2") (pintype "passive"))
      (node (ref "U$3") (pin "5") (pinfunction "EXT_IN_5") (pintype "bidirectional"))
    )
    (net (code "296") (name "Net-(U$3-EXT_OUT)") (class "Default")
      (node (ref "R3") (pin "1") (pinfunction "1_1") (pintype "passive"))
      (node (ref "U$3") (pin "6") (pinfunction "EXT_OUT_6") (pintype "bidirectional"))
    )
    (net (code "297") (name "Net-(U$4-EXT_IN)") (class "Default")
      (node (ref "R4") (pin "2") (pinfunction "2_2") (pintype "passive"))
      (node (ref "U$4") (pin "5") (pinfunction "EXT_IN_5") (pintype "bidirectional"))
    )
    (net (code "298") (name "Net-(U$4-EXT_OUT)") (class "Default")
      (node (ref "R4") (pin "1") (pinfunction "1_1") (pintype "passive"))
      (node (ref "U$4") (pin "6") (pinfunction "EXT_OUT_6") (pintype "bidirectional"))
    )
    (net (code "299") (name "Net-(U$5-EXT_IN)") (class "Default")
      (node (ref "R5") (pin "2") (pinfunction "2_2") (pintype "passive"))
      (node (ref "U$5") (pin "5") (pinfunction "EXT_IN_5") (pintype "bidirectional"))
    )
    (net (code "300") (name "Net-(U$5-EXT_OUT)") (class "Default")
      (node (ref "R5") (pin "1") (pinfunction "1_1") (pintype "passive"))
      (node (ref "U$5") (pin "6") (pinfunction "EXT_OUT_6") (pintype "bidirectional"))
    )
    (net (code "301") (name "Net-(U$6-EXT_IN)") (class "Default")
      (node (ref "R6") (pin "2") (pinfunction "2_2") (pintype "passive"))
      (node (ref "U$6") (pin "5") (pinfunction "EXT_IN_5") (pintype "bidirectional"))
    )
    (net (code "302") (name "Net-(U$6-EXT_OUT)") (class "Default")
      (node (ref "R6") (pin "1") (pinfunction "1_1") (pintype "passive"))
      (node (ref "U$6") (pin "6") (pinfunction "EXT_OUT_6") (pintype "bidirectional"))
    )
    (net (code "303") (name "Net-(U$7-EXT_IN)") (class "Default")
      (node (ref "R7") (pin "2") (pinfunction "2_2") (pintype "passive"))
      (node (ref "U$7") (pin "5") (pinfunction "EXT_IN_5") (pintype "bidirectional"))
    )
    (net (code "304") (name "Net-(U$7-EXT_OUT)") (class "Default")
      (node (ref "R7") (pin "1") (pinfunction "1_1") (pintype "passive"))
      (node (ref "U$7") (pin "6") (pinfunction "EXT_OUT_6") (pintype "bidirectional"))
    )
    (net (code "305") (name "Net-(U$8-EXT_IN)") (class "Default")
      (node (ref "R8") (pin "2") (pinfunction "2_2") (pintype "passive"))
      (node (ref "U$8") (pin "5") (pinfunction "EXT_IN_5") (pintype "bidirectional"))
    )
    (net (code "306") (name "Net-(U$8-EXT_OUT)") (class "Default")
      (node (ref "R8") (pin "1") (pinfunction "1_1") (pintype "passive"))
      (node (ref "U$8") (pin "6") (pinfunction "EXT_OUT_6") (pintype "bidirectional"))
    )
    (net (code "307") (name "Net-(U$9-EXT_IN)") (class "Default")
      (node (ref "R9") (pin "2") (pinfunction "2_2") (pintype "passive"))
      (node (ref "U$9") (pin "5") (pinfunction "EXT_IN_5") (pintype "bidirectional"))
    )
    (net (code "308") (name "Net-(U$9-EXT_OUT)") (class "Default")
      (node (ref "R9") (pin "1") (pinfunction "1_1") (pintype "passive"))
      (node (ref "U$9") (pin "6") (pinfunction "EXT_OUT_6") (pintype "bidirectional"))
    )
    (net (code "309") (name "Net-(U$10-EXT_IN)") (class "Default")
      (node (ref "R10") (pin "2") (pinfunction "2_2") (pintype "passive"))
      (node (ref "U$10") (pin "5") (pinfunction "EXT_IN_5") (pintype "bidirectional"))
    )
    (net (code "310") (name "Net-(U$10-EXT_OUT)") (class "Default")
      (node (ref "R10") (pin "1") (pinfunction "1_1") (pintype "passive"))
      (node (ref "U$10") (pin "6") (pinfunction "EXT_OUT_6") (pintype "bidirectional"))
    )
    (net (code "311") (name "Net-(U$11-EXT_IN)") (class "Default")
      (node (ref "R11") (pin "2") (pinfunction "2_2") (pintype "passive"))
      (node (ref "U$11") (pin "5") (pinfunction "EXT_IN_5") (pintype "bidirectional"))
    )
    (net (code "312") (name "Net-(U$11-EXT_OUT)") (class "Default")
      (node (ref "R11") (pin "1") (pinfunction "1_1") (pintype "passive"))
      (node (ref "U$11") (pin "6") (pinfunction "EXT_OUT_6") (pintype "bidirectional"))
    )
    (net (code "313") (name "Net-(U$12-EXT_IN)") (class "Default")
      (node (ref "R12") (pin "2") (pinfunction "2_2") (pintype "passive"))
      (node (ref "U$12") (pin "5") (pinfunction "EXT_IN_5") (pintype "bidirectional"))
    )
    (net (code "314") (name "Net-(U$12-EXT_OUT)") (class "Default")
      (node (ref "R12") (pin "1") (pinfunction "1_1") (pintype "passive"))
      (node (ref "U$12") (pin "6") (pinfunction "EXT_OUT_6") (pintype "bidirectional"))
    )
    (net (code "315") (name "Net-(U$13-EXT_IN)") (class "Default")
      (node (ref "R13") (pin "2") (pinfunction "2_2") (pintype "passive"))
      (node (ref "U$13") (pin "5") (pinfunction "EXT_IN_5") (pintype "bidirectional"))
    )
    (net (code "316") (name "Net-(U$13-EXT_OUT)") (class "Default")
      (node (ref "R13") (pin "1") (pinfunction "1_1") (pintype "passive"))
      (node (ref "U$13") (pin "6") (pinfunction "EXT_OUT_6") (pintype "bidirectional"))
    )
    (net (code "317") (name "Net-(U$14-EXT_IN)") (class "Default")
      (node (ref "R14") (pin "2") (pinfunction "2_2") (pintype "passive"))
      (node (ref "U$14") (pin "5") (pinfunction "EXT_IN_5") (pintype "bidirectional"))
    )
    (net (code "318") (name "Net-(U$14-EXT_OUT)") (class "Default")
      (node (ref "R14") (pin "1") (pinfunction "1_1") (pintype "passive"))
      (node (ref "U$14") (pin "6") (pinfunction "EXT_OUT_6") (pintype "bidirectional"))
    )
    (net (code "319") (name "Net-(U$15-EXT_IN)") (class "Default")
      (node (ref "R15") (pin "2") (pinfunction "2_2") (pintype "passive"))
      (node (ref "U$15") (pin "5") (pinfunction "EXT_IN_5") (pintype "bidirectional"))
    )
    (net (code "320") (name "Net-(U$15-EXT_OUT)") (class "Default")
      (node (ref "R15") (pin "1") (pinfunction "1_1") (pintype "passive"))
      (node (ref "U$15") (pin "6") (pinfunction "EXT_OUT_6") (pintype "bidirectional"))
    )
    (net (code "321") (name "Net-(U$16-EXT_IN)") (class "Default")
      (node (ref "R16") (pin "2") (pinfunction "2_2") (pintype "passive"))
      (node (ref "U$16") (pin "5") (pinfunction "EXT_IN_5") (pintype "bidirectional"))
    )
    (net (code "322") (name "Net-(U$16-EXT_OUT)") (class "Default")
      (node (ref "R16") (pin "1") (pinfunction "1_1") (pintype "passive"))
      (node (ref "U$16") (pin "6") (pinfunction "EXT_OUT_6") (pintype "bidirectional"))
    )
    (net (code "323") (name "Net-(U$17-EXT_IN)") (class "Default")
      (node (ref "R17") (pin "2") (pinfunction "2_2") (pintype "passive"))
      (node (ref "U$17") (pin "5") (pinfunction "EXT_IN_5") (pintype "bidirectional"))
    )
    (net (code "324") (name "Net-(U$17-EXT_OUT)") (class "Default")
      (node (ref "R17") (pin "1") (pinfunction "1_1") (pintype "passive"))
      (node (ref "U$17") (pin "6") (pinfunction "EXT_OUT_6") (pintype "bidirectional"))
    )
    (net (code "325") (name "Net-(U$18-EXT_IN)") (class "Default")
      (node (ref "R18") (pin "2") (pinfunction "2_2") (pintype "passive"))
      (node (ref "U$18") (pin "5") (pinfunction "EXT_IN_5") (pintype "bidirectional"))
    )
    (net (code "326") (name "Net-(U$18-EXT_OUT)") (class "Default")
      (node (ref "R18") (pin "1") (pinfunction "1_1") (pintype "passive"))
      (node (ref "U$18") (pin "6") (pinfunction "EXT_OUT_6") (pintype "bidirectional"))
    )
    (net (code "327") (name "Net-(U$19-EXT_IN)") (class "Default")
      (node (ref "R19") (pin "2") (pinfunction "2_2") (pintype "passive"))
      (node (ref "U$19") (pin "5") (pinfunction "EXT_IN_5") (pintype "bidirectional"))
    )
    (net (code "328") (name "Net-(U$19-EXT_OUT)") (class "Default")
      (node (ref "R19") (pin "1") (pinfunction "1_1") (pintype "passive"))
      (node (ref "U$19") (pin "6") (pinfunction "EXT_OUT_6") (pintype "bidirectional"))
    )
    (net (code "329") (name "Net-(U$20-EXT_IN)") (class "Default")
      (node (ref "R20") (pin "2") (pinfunction "2_2") (pintype "passive"))
      (node (ref "U$20") (pin "5") (pinfunction "EXT_IN_5") (pintype "bidirectional"))
    )
    (net (code "330") (name "Net-(U$20-EXT_OUT)") (class "Default")
      (node (ref "R20") (pin "1") (pinfunction "1_1") (pintype "passive"))
      (node (ref "U$20") (pin "6") (pinfunction "EXT_OUT_6") (pintype "bidirectional"))
    )
    (net (code "331") (name "Net-(U$21-EXT_IN)") (class "Default")
      (node (ref "R21") (pin "2") (pinfunction "2_2") (pintype "passive"))
      (node (ref "U$21") (pin "5") (pinfunction "EXT_IN_5") (pintype "bidirectional"))
    )
    (net (code "332") (name "Net-(U$21-EXT_OUT)") (class "Default")
      (node (ref "R21") (pin "1") (pinfunction "1_1") (pintype "passive"))
      (node (ref "U$21") (pin "6") (pinfunction "EXT_OUT_6") (pintype "bidirectional"))
    )
    (net (code "333") (name "Net-(U$22-EXT_IN)") (class "Default")
      (node (ref "R22") (pin "2") (pinfunction "2_2") (pintype "passive"))
      (node (ref "U$22") (pin "5") (pinfunction "EXT_IN_5") (pintype "bidirectional"))
    )
    (net (code "334") (name "Net-(U$22-EXT_OUT)") (class "Default")
      (node (ref "R22") (pin "1") (pinfunction "1_1") (pintype "passive"))
      (node (ref "U$22") (pin "6") (pinfunction "EXT_OUT_6") (pintype "bidirectional"))
    )
    (net (code "335") (name "Net-(U$23-EXT_IN)") (class "Default")
      (node (ref "R23") (pin "2") (pinfunction "2_2") (pintype "passive"))
      (node (ref "U$23") (pin "5") (pinfunction "EXT_IN_5") (pintype "bidirectional"))
    )
    (net (code "336") (name "Net-(U$23-EXT_OUT)") (class "Default")
      (node (ref "R23") (pin "1") (pinfunction "1_1") (pintype "passive"))
      (node (ref "U$23") (pin "6") (pinfunction "EXT_OUT_6") (pintype "bidirectional"))
    )
    (net (code "337") (name "Net-(U$24-EXT_IN)") (class "Default")
      (node (ref "R24") (pin "2") (pinfunction "2_2") (pintype "passive"))
      (node (ref "U$24") (pin "5") (pinfunction "EXT_IN_5") (pintype "bidirectional"))
    )
    (net (code "338") (name "Net-(U$24-EXT_OUT)") (class "Default")
      (node (ref "R24") (pin "1") (pinfunction "1_1") (pintype "passive"))
      (node (ref "U$24") (pin "6") (pinfunction "EXT_OUT_6") (pintype "bidirectional"))
    )
    (net (code "339") (name "Net-(U$25-EXT_IN)") (class "Default")
      (node (ref "R25") (pin "2") (pinfunction "2_2") (pintype "passive"))
      (node (ref "U$25") (pin "5") (pinfunction "EXT_IN_5") (pintype "bidirectional"))
    )
    (net (code "340") (name "Net-(U$25-EXT_OUT)") (class "Default")
      (node (ref "R25") (pin "1") (pinfunction "1_1") (pintype "passive"))
      (node (ref "U$25") (pin "6") (pinfunction "EXT_OUT_6") (pintype "bidirectional"))
    )
    (net (code "341") (name "Net-(U$26-EXT_IN)") (class "Default")
      (node (ref "R26") (pin "2") (pinfunction "2_2") (pintype "passive"))
      (node (ref "U$26") (pin "5") (pinfunction "EXT_IN_5") (pintype "bidirectional"))
    )
    (net (code "342") (name "Net-(U$26-EXT_OUT)") (class "Default")
      (node (ref "R26") (pin "1") (pinfunction "1_1") (pintype "passive"))
      (node (ref "U$26") (pin "6") (pinfunction "EXT_OUT_6") (pintype "bidirectional"))
    )
    (net (code "343") (name "Net-(U$27-EXT_IN)") (class "Default")
      (node (ref "R27") (pin "2") (pinfunction "2_2") (pintype "passive"))
      (node (ref "U$27") (pin "5") (pinfunction "EXT_IN_5") (pintype "bidirectional"))
    )
    (net (code "344") (name "Net-(U$27-EXT_OUT)") (class "Default")
      (node (ref "R27") (pin "1") (pinfunction "1_1") (pintype "passive"))
      (node (ref "U$27") (pin "6") (pinfunction "EXT_OUT_6") (pintype "bidirectional"))
    )
    (net (code "345") (name "Net-(U$28-EXT_IN)") (class "Default")
      (node (ref "R28") (pin "2") (pinfunction "2_2") (pintype "passive"))
      (node (ref "U$28") (pin "5") (pinfunction "EXT_IN_5") (pintype "bidirectional"))
    )
    (net (code "346") (name "Net-(U$28-EXT_OUT)") (class "Default")
      (node (ref "R28") (pin "1") (pinfunction "1_1") (pintype "passive"))
      (node (ref "U$28") (pin "6") (pinfunction "EXT_OUT_6") (pintype "bidirectional"))
    )
    (net (code "347") (name "Net-(U$29-EXT_IN)") (class "Default")
      (node (ref "R29") (pin "2") (pinfunction "2_2") (pintype "passive"))
      (node (ref "U$29") (pin "5") (pinfunction "EXT_IN_5") (pintype "bidirectional"))
    )
    (net (code "348") (name "Net-(U$29-EXT_OUT)") (class "Default")
      (node (ref "R29") (pin "1") (pinfunction "1_1") (pintype "passive"))
      (node (ref "U$29") (pin "6") (pinfunction "EXT_OUT_6") (pintype "bidirectional"))
    )
    (net (code "349") (name "Net-(U$30-EXT_IN)") (class "Default")
      (node (ref "R30") (pin "2") (pinfunction "2_2") (pintype "passive"))
      (node (ref "U$30") (pin "5") (pinfunction "EXT_IN_5") (pintype "bidirectional"))
    )
    (net (code "350") (name "Net-(U$30-EXT_OUT)") (class "Default")
      (node (ref "R30") (pin "1") (pinfunction "1_1") (pintype "passive"))
      (node (ref "U$30") (pin "6") (pinfunction "EXT_OUT_6") (pintype "bidirectional"))
    )
    (net (code "351") (name "Net-(U$31-EXT_IN)") (class "Default")
      (node (ref "R31") (pin "2") (pinfunction "2_2") (pintype "passive"))
      (node (ref "U$31") (pin "5") (pinfunction "EXT_IN_5") (pintype "bidirectional"))
    )
    (net (code "352") (name "Net-(U$31-EXT_OUT)") (class "Default")
      (node (ref "R31") (pin "1") (pinfunction "1_1") (pintype "passive"))
      (node (ref "U$31") (pin "6") (pinfunction "EXT_OUT_6") (pintype "bidirectional"))
    )
    (net (code "353") (name "Net-(U$32-EXT_IN)") (class "Default")
      (node (ref "R32") (pin "2") (pinfunction "2_2") (pintype "passive"))
      (node (ref "U$32") (pin "5") (pinfunction "EXT_IN_5") (pintype "bidirectional"))
    )
    (net (code "354") (name "Net-(U$32-EXT_OUT)") (class "Default")
      (node (ref "R32") (pin "1") (pinfunction "1_1") (pintype "passive"))
      (node (ref "U$32") (pin "6") (pinfunction "EXT_OUT_6") (pintype "bidirectional"))
    )
    (net (code "355") (name "Net-(U$33-EXT_IN)") (class "Default")
      (node (ref "R33") (pin "2") (pinfunction "2_2") (pintype "passive"))
      (node (ref "U$33") (pin "5") (pinfunction "EXT_IN_5") (pintype "bidirectional"))
    )
    (net (code "356") (name "Net-(U$33-EXT_OUT)") (class "Default")
      (node (ref "R33") (pin "1") (pinfunction "1_1") (pintype "passive"))
      (node (ref "U$33") (pin "6") (pinfunction "EXT_OUT_6") (pintype "bidirectional"))
    )
    (net (code "357") (name "Net-(U$34-EXT_IN)") (class "Default")
      (node (ref "R34") (pin "2") (pinfunction "2_2") (pintype "passive"))
      (node (ref "U$34") (pin "5") (pinfunction "EXT_IN_5") (pintype "bidirectional"))
    )
    (net (code "358") (name "Net-(U$34-EXT_OUT)") (class "Default")
      (node (ref "R34") (pin "1") (pinfunction "1_1") (pintype "passive"))
      (node (ref "U$34") (pin "6") (pinfunction "EXT_OUT_6") (pintype "bidirectional"))
    )
    (net (code "359") (name "Net-(U$35-EXT_IN)") (class "Default")
      (node (ref "R35") (pin "2") (pinfunction "2_2") (pintype "passive"))
      (node (ref "U$35") (pin "5") (pinfunction "EXT_IN_5") (pintype "bidirectional"))
    )
    (net (code "360") (name "Net-(U$35-EXT_OUT)") (class "Default")
      (node (ref "R35") (pin "1") (pinfunction "1_1") (pintype "passive"))
      (node (ref "U$35") (pin "6") (pinfunction "EXT_OUT_6") (pintype "bidirectional"))
    )
    (net (code "361") (name "Net-(U$36-EXT_IN)") (class "Default")
      (node (ref "R36") (pin "2") (pinfunction "2_2") (pintype "passive"))
      (node (ref "U$36") (pin "5") (pinfunction "EXT_IN_5") (pintype "bidirectional"))
    )
    (net (code "362") (name "Net-(U$36-EXT_OUT)") (class "Default")
      (node (ref "R36") (pin "1") (pinfunction "1_1") (pintype "passive"))
      (node (ref "U$36") (pin "6") (pinfunction "EXT_OUT_6") (pintype "bidirectional"))
    )
    (net (code "363") (name "Net-(U$37-EXT_IN)") (class "Default")
      (node (ref "R37") (pin "2") (pinfunction "2_2") (pintype "passive"))
      (node (ref "U$37") (pin "5") (pinfunction "EXT_IN_5") (pintype "bidirectional"))
    )
    (net (code "364") (name "Net-(U$37-EXT_OUT)") (class "Default")
      (node (ref "R37") (pin "1") (pinfunction "1_1") (pintype "passive"))
      (node (ref "U$37") (pin "6") (pinfunction "EXT_OUT_6") (pintype "bidirectional"))
    )
    (net (code "365") (name "Net-(U$38-EXT_IN)") (class "Default")
      (node (ref "R38") (pin "2") (pinfunction "2_2") (pintype "passive"))
      (node (ref "U$38") (pin "5") (pinfunction "EXT_IN_5") (pintype "bidirectional"))
    )
    (net (code "366") (name "Net-(U$38-EXT_OUT)") (class "Default")
      (node (ref "R38") (pin "1") (pinfunction "1_1") (pintype "passive"))
      (node (ref "U$38") (pin "6") (pinfunction "EXT_OUT_6") (pintype "bidirectional"))
    )
    (net (code "367") (name "Net-(U$39-EXT_IN)") (class "Default")
      (node (ref "R39") (pin "2") (pinfunction "2_2") (pintype "passive"))
      (node (ref "U$39") (pin "5") (pinfunction "EXT_IN_5") (pintype "bidirectional"))
    )
    (net (code "368") (name "Net-(U$39-EXT_OUT)") (class "Default")
      (node (ref "R39") (pin "1") (pinfunction "1_1") (pintype "passive"))
      (node (ref "U$39") (pin "6") (pinfunction "EXT_OUT_6") (pintype "bidirectional"))
    )
    (net (code "369") (name "Net-(U$40-EXT_IN)") (class "Default")
      (node (ref "R40") (pin "2") (pinfunction "2_2") (pintype "passive"))
      (node (ref "U$40") (pin "5") (pinfunction "EXT_IN_5") (pintype "bidirectional"))
    )
    (net (code "370") (name "Net-(U$40-EXT_OUT)") (class "Default")
      (node (ref "R40") (pin "1") (pinfunction "1_1") (pintype "passive"))
      (node (ref "U$40") (pin "6") (pinfunction "EXT_OUT_6") (pintype "bidirectional"))
    )
    (net (code "371") (name "Net-(U$41-EXT_IN)") (class "Default")
      (node (ref "R41") (pin "2") (pinfunction "2_2") (pintype "passive"))
      (node (ref "U$41") (pin "5") (pinfunction "EXT_IN_5") (pintype "bidirectional"))
    )
    (net (code "372") (name "Net-(U$41-EXT_OUT)") (class "Default")
      (node (ref "R41") (pin "1") (pinfunction "1_1") (pintype "passive"))
      (node (ref "U$41") (pin "6") (pinfunction "EXT_OUT_6") (pintype "bidirectional"))
    )
    (net (code "373") (name "Net-(U$42-EXT_IN)") (class "Default")
      (node (ref "R42") (pin "2") (pinfunction "2_2") (pintype "passive"))
      (node (ref "U$42") (pin "5") (pinfunction "EXT_IN_5") (pintype "bidirectional"))
    )
    (net (code "374") (name "Net-(U$42-EXT_OUT)") (class "Default")
      (node (ref "R42") (pin "1") (pinfunction "1_1") (pintype "passive"))
      (node (ref "U$42") (pin "6") (pinfunction "EXT_OUT_6") (pintype "bidirectional"))
    )
    (net (code "375") (name "Net-(U$43-EXT_IN)") (class "Default")
      (node (ref "R43") (pin "2") (pinfunction "2_2") (pintype "passive"))
      (node (ref "U$43") (pin "5") (pinfunction "EXT_IN_5") (pintype "bidirectional"))
    )
    (net (code "376") (name "Net-(U$43-EXT_OUT)") (class "Default")
      (node (ref "R43") (pin "1") (pinfunction "1_1") (pintype "passive"))
      (node (ref "U$43") (pin "6") (pinfunction "EXT_OUT_6") (pintype "bidirectional"))
    )
    (net (code "377") (name "Net-(U$44-EXT_IN)") (class "Default")
      (node (ref "R44") (pin "2") (pinfunction "2_2") (pintype "passive"))
      (node (ref "U$44") (pin "5") (pinfunction "EXT_IN_5") (pintype "bidirectional"))
    )
    (net (code "378") (name "Net-(U$44-EXT_OUT)") (class "Default")
      (node (ref "R44") (pin "1") (pinfunction "1_1") (pintype "passive"))
      (node (ref "U$44") (pin "6") (pinfunction "EXT_OUT_6") (pintype "bidirectional"))
    )
    (net (code "379") (name "Net-(U$45-EXT_IN)") (class "Default")
      (node (ref "R45") (pin "2") (pinfunction "2_2") (pintype "passive"))
      (node (ref "U$45") (pin "5") (pinfunction "EXT_IN_5") (pintype "bidirectional"))
    )
    (net (code "380") (name "Net-(U$45-EXT_OUT)") (class "Default")
      (node (ref "R45") (pin "1") (pinfunction "1_1") (pintype "passive"))
      (node (ref "U$45") (pin "6") (pinfunction "EXT_OUT_6") (pintype "bidirectional"))
    )
    (net (code "381") (name "Net-(U$46-EXT_IN)") (class "Default")
      (node (ref "R46") (pin "2") (pinfunction "2_2") (pintype "passive"))
      (node (ref "U$46") (pin "5") (pinfunction "EXT_IN_5") (pintype "bidirectional"))
    )
    (net (code "382") (name "Net-(U$46-EXT_OUT)") (class "Default")
      (node (ref "R46") (pin "1") (pinfunction "1_1") (pintype "passive"))
      (node (ref "U$46") (pin "6") (pinfunction "EXT_OUT_6") (pintype "bidirectional"))
    )
    (net (code "383") (name "Net-(U$47-EXT_IN)") (class "Default")
      (node (ref "R47") (pin "2") (pinfunction "2_2") (pintype "passive"))
      (node (ref "U$47") (pin "5") (pinfunction "EXT_IN_5") (pintype "bidirectional"))
    )
    (net (code "384") (name "Net-(U$47-EXT_OUT)") (class "Default")
      (node (ref "R47") (pin "1") (pinfunction "1_1") (pintype "passive"))
      (node (ref "U$47") (pin "6") (pinfunction "EXT_OUT_6") (pintype "bidirectional"))
    )
    (net (code "385") (name "Net-(U$48-EXT_IN)") (class "Default")
      (node (ref "R48") (pin "2") (pinfunction "2_2") (pintype "passive"))
      (node (ref "U$48") (pin "5") (pinfunction "EXT_IN_5") (pintype "bidirectional"))
    )
    (net (code "386") (name "Net-(U$48-EXT_OUT)") (class "Default")
      (node (ref "R48") (pin "1") (pinfunction "1_1") (pintype "passive"))
      (node (ref "U$48") (pin "6") (pinfunction "EXT_OUT_6") (pintype "bidirectional"))
    )
    (net (code "387") (name "Net-(U$49-EXT_IN)") (class "Default")
      (node (ref "R49") (pin "2") (pinfunction "2_2") (pintype "passive"))
      (node (ref "U$49") (pin "5") (pinfunction "EXT_IN_5") (pintype "bidirectional"))
    )
    (net (code "388") (name "Net-(U$49-EXT_OUT)") (class "Default")
      (node (ref "R49") (pin "1") (pinfunction "1_1") (pintype "passive"))
      (node (ref "U$49") (pin "6") (pinfunction "EXT_OUT_6") (pintype "bidirectional"))
    )
    (net (code "389") (name "Net-(U$50-EXT_IN)") (class "Default")
      (node (ref "R50") (pin "2") (pinfunction "2_2") (pintype "passive"))
      (node (ref "U$50") (pin "5") (pinfunction "EXT_IN_5") (pintype "bidirectional"))
    )
    (net (code "390") (name "Net-(U$50-EXT_OUT)") (class "Default")
      (node (ref "R50") (pin "1") (pinfunction "1_1") (pintype "passive"))
      (node (ref "U$50") (pin "6") (pinfunction "EXT_OUT_6") (pintype "bidirectional"))
    )
    (net (code "391") (name "Net-(U$51-EXT_IN)") (class "Default")
      (node (ref "R51") (pin "2") (pinfunction "2_2") (pintype "passive"))
      (node (ref "U$51") (pin "5") (pinfunction "EXT_IN_5") (pintype "bidirectional"))
    )
    (net (code "392") (name "Net-(U$51-EXT_OUT)") (class "Default")
      (node (ref "R51") (pin "1") (pinfunction "1_1") (pintype "passive"))
      (node (ref "U$51") (pin "6") (pinfunction "EXT_OUT_6") (pintype "bidirectional"))
    )
    (net (code "393") (name "Net-(U$52-EXT_IN)") (class "Default")
      (node (ref "R52") (pin "2") (pinfunction "2_2") (pintype "passive"))
      (node (ref "U$52") (pin "5") (pinfunction "EXT_IN_5") (pintype "bidirectional"))
    )
    (net (code "394") (name "Net-(U$52-EXT_OUT)") (class "Default")
      (node (ref "R52") (pin "1") (pinfunction "1_1") (pintype "passive"))
      (node (ref "U$52") (pin "6") (pinfunction "EXT_OUT_6") (pintype "bidirectional"))
    )
    (net (code "395") (name "Net-(U$53-EXT_IN)") (class "Default")
      (node (ref "R53") (pin "2") (pinfunction "2_2") (pintype "passive"))
      (node (ref "U$53") (pin "5") (pinfunction "EXT_IN_5") (pintype "bidirectional"))
    )
    (net (code "396") (name "Net-(U$53-EXT_OUT)") (class "Default")
      (node (ref "R53") (pin "1") (pinfunction "1_1") (pintype "passive"))
      (node (ref "U$53") (pin "6") (pinfunction "EXT_OUT_6") (pintype "bidirectional"))
    )
    (net (code "397") (name "Net-(U$54-EXT_IN)") (class "Default")
      (node (ref "R54") (pin "2") (pinfunction "2_2") (pintype "passive"))
      (node (ref "U$54") (pin "5") (pinfunction "EXT_IN_5") (pintype "bidirectional"))
    )
    (net (code "398") (name "Net-(U$54-EXT_OUT)") (class "Default")
      (node (ref "R54") (pin "1") (pinfunction "1_1") (pintype "passive"))
      (node (ref "U$54") (pin "6") (pinfunction "EXT_OUT_6") (pintype "bidirectional"))
    )
    (net (code "399") (name "Net-(U$55-EXT_IN)") (class "Default")
      (node (ref "R55") (pin "2") (pinfunction "2_2") (pintype "passive"))
      (node (ref "U$55") (pin "5") (pinfunction "EXT_IN_5") (pintype "bidirectional"))
    )
    (net (code "400") (name "Net-(U$55-EXT_OUT)") (class "Default")
      (node (ref "R55") (pin "1") (pinfunction "1_1") (pintype "passive"))
      (node (ref "U$55") (pin "6") (pinfunction "EXT_OUT_6") (pintype "bidirectional"))
    )
    (net (code "401") (name "Net-(U$56-EXT_IN)") (class "Default")
      (node (ref "R56") (pin "2") (pinfunction "2_2") (pintype "passive"))
      (node (ref "U$56") (pin "5") (pinfunction "EXT_IN_5") (pintype "bidirectional"))
    )
    (net (code "402") (name "Net-(U$56-EXT_OUT)") (class "Default")
      (node (ref "R56") (pin "1") (pinfunction "1_1") (pintype "passive"))
      (node (ref "U$56") (pin "6") (pinfunction "EXT_OUT_6") (pintype "bidirectional"))
    )
    (net (code "403") (name "Net-(U$57-EXT_IN)") (class "Default")
      (node (ref "R57") (pin "2") (pinfunction "2_2") (pintype "passive"))
      (node (ref "U$57") (pin "5") (pinfunction "EXT_IN_5") (pintype "bidirectional"))
    )
    (net (code "404") (name "Net-(U$57-EXT_OUT)") (class "Default")
      (node (ref "R57") (pin "1") (pinfunction "1_1") (pintype "passive"))
      (node (ref "U$57") (pin "6") (pinfunction "EXT_OUT_6") (pintype "bidirectional"))
    )
    (net (code "405") (name "Net-(U$58-EXT_IN)") (class "Default")
      (node (ref "R58") (pin "2") (pinfunction "2_2") (pintype "passive"))
      (node (ref "U$58") (pin "5") (pinfunction "EXT_IN_5") (pintype "bidirectional"))
    )
    (net (code "406") (name "Net-(U$58-EXT_OUT)") (class "Default")
      (node (ref "R58") (pin "1") (pinfunction "1_1") (pintype "passive"))
      (node (ref "U$58") (pin "6") (pinfunction "EXT_OUT_6") (pintype "bidirectional"))
    )
    (net (code "407") (name "Net-(U$59-EXT_IN)") (class "Default")
      (node (ref "R59") (pin "2") (pinfunction "2_2") (pintype "passive"))
      (node (ref "U$59") (pin "5") (pinfunction "EXT_IN_5") (pintype "bidirectional"))
    )
    (net (code "408") (name "Net-(U$59-EXT_OUT)") (class "Default")
      (node (ref "R59") (pin "1") (pinfunction "1_1") (pintype "passive"))
      (node (ref "U$59") (pin "6") (pinfunction "EXT_OUT_6") (pintype "bidirectional"))
    )
    (net (code "409") (name "Net-(U$60-EXT_IN)") (class "Default")
      (node (ref "R60") (pin "2") (pinfunction "2_2") (pintype "passive"))
      (node (ref "U$60") (pin "5") (pinfunction "EXT_IN_5") (pintype "bidirectional"))
    )
    (net (code "410") (name "Net-(U$60-EXT_OUT)") (class "Default")
      (node (ref "R60") (pin "1") (pinfunction "1_1") (pintype "passive"))
      (node (ref "U$60") (pin "6") (pinfunction "EXT_OUT_6") (pintype "bidirectional"))
    )
    (net (code "411") (name "Net-(U$61-EXT_IN)") (class "Default")
      (node (ref "R61") (pin "2") (pinfunction "2_2") (pintype "passive"))
      (node (ref "U$61") (pin "5") (pinfunction "EXT_IN_5") (pintype "bidirectional"))
    )
    (net (code "412") (name "Net-(U$61-EXT_OUT)") (class "Default")
      (node (ref "R61") (pin "1") (pinfunction "1_1") (pintype "passive"))
      (node (ref "U$61") (pin "6") (pinfunction "EXT_OUT_6") (pintype "bidirectional"))
    )
    (net (code "413") (name "Net-(U$62-EXT_IN)") (class "Default")
      (node (ref "R62") (pin "2") (pinfunction "2_2") (pintype "passive"))
      (node (ref "U$62") (pin "5") (pinfunction "EXT_IN_5") (pintype "bidirectional"))
    )
    (net (code "414") (name "Net-(U$62-EXT_OUT)") (class "Default")
      (node (ref "R62") (pin "1") (pinfunction "1_1") (pintype "passive"))
      (node (ref "U$62") (pin "6") (pinfunction "EXT_OUT_6") (pintype "bidirectional"))
    )
    (net (code "415") (name "Net-(U$63-EXT_IN)") (class "Default")
      (node (ref "R63") (pin "2") (pinfunction "2_2") (pintype "passive"))
      (node (ref "U$63") (pin "5") (pinfunction "EXT_IN_5") (pintype "bidirectional"))
    )
    (net (code "416") (name "Net-(U$63-EXT_OUT)") (class "Default")
      (node (ref "R63") (pin "1") (pinfunction "1_1") (pintype "passive"))
      (node (ref "U$63") (pin "6") (pinfunction "EXT_OUT_6") (pintype "bidirectional"))
    )
    (net (code "417") (name "Net-(U$64-EXT_IN)") (class "Default")
      (node (ref "R64") (pin "2") (pinfunction "2_2") (pintype "passive"))
      (node (ref "U$64") (pin "5") (pinfunction "EXT_IN_5") (pintype "bidirectional"))
    )
    (net (code "418") (name "Net-(U$64-EXT_OUT)") (class "Default")
      (node (ref "R64") (pin "1") (pinfunction "1_1") (pintype "passive"))
      (node (ref "U$64") (pin "6") (pinfunction "EXT_OUT_6") (pintype "bidirectional"))
    )
    (net (code "419") (name "Net-(U$65-EXT_IN)") (class "Default")
      (node (ref "R65") (pin "2") (pinfunction "2_2") (pintype "passive"))
      (node (ref "U$65") (pin "5") (pinfunction "EXT_IN_5") (pintype "bidirectional"))
    )
    (net (code "420") (name "Net-(U$65-EXT_OUT)") (class "Default")
      (node (ref "R65") (pin "1") (pinfunction "1_1") (pintype "passive"))
      (node (ref "U$65") (pin "6") (pinfunction "EXT_OUT_6") (pintype "bidirectional"))
    )
    (net (code "421") (name "Net-(U$66-EXT_IN)") (class "Default")
      (node (ref "R66") (pin "2") (pinfunction "2_2") (pintype "passive"))
      (node (ref "U$66") (pin "5") (pinfunction "EXT_IN_5") (pintype "bidirectional"))
    )
    (net (code "422") (name "Net-(U$66-EXT_OUT)") (class "Default")
      (node (ref "R66") (pin "1") (pinfunction "1_1") (pintype "passive"))
      (node (ref "U$66") (pin "6") (pinfunction "EXT_OUT_6") (pintype "bidirectional"))
    )
    (net (code "423") (name "Net-(U$67-EXT_IN)") (class "Default")
      (node (ref "R67") (pin "2") (pinfunction "2_2") (pintype "passive"))
      (node (ref "U$67") (pin "5") (pinfunction "EXT_IN_5") (pintype "bidirectional"))
    )
    (net (code "424") (name "Net-(U$67-EXT_OUT)") (class "Default")
      (node (ref "R67") (pin "1") (pinfunction "1_1") (pintype "passive"))
      (node (ref "U$67") (pin "6") (pinfunction "EXT_OUT_6") (pintype "bidirectional"))
    )
    (net (code "425") (name "Net-(U$68-EXT_IN)") (class "Default")
      (node (ref "R68") (pin "2") (pinfunction "2_2") (pintype "passive"))
      (node (ref "U$68") (pin "5") (pinfunction "EXT_IN_5") (pintype "bidirectional"))
    )
    (net (code "426") (name "Net-(U$68-EXT_OUT)") (class "Default")
      (node (ref "R68") (pin "1") (pinfunction "1_1") (pintype "passive"))
      (node (ref "U$68") (pin "6") (pinfunction "EXT_OUT_6") (pintype "bidirectional"))
    )
    (net (code "427") (name "Net-(U$69-EXT_IN)") (class "Default")
      (node (ref "R69") (pin "2") (pinfunction "2_2") (pintype "passive"))
      (node (ref "U$69") (pin "5") (pinfunction "EXT_IN_5") (pintype "bidirectional"))
    )
    (net (code "428") (name "Net-(U$69-EXT_OUT)") (class "Default")
      (node (ref "R69") (pin "1") (pinfunction "1_1") (pintype "passive"))
      (node (ref "U$69") (pin "6") (pinfunction "EXT_OUT_6") (pintype "bidirectional"))
    )
    (net (code "429") (name "Net-(U$70-EXT_IN)") (class "Default")
      (node (ref "R70") (pin "2") (pinfunction "2_2") (pintype "passive"))
      (node (ref "U$70") (pin "5") (pinfunction "EXT_IN_5") (pintype "bidirectional"))
    )
    (net (code "430") (name "Net-(U$70-EXT_OUT)") (class "Default")
      (node (ref "R70") (pin "1") (pinfunction "1_1") (pintype "passive"))
      (node (ref "U$70") (pin "6") (pinfunction "EXT_OUT_6") (pintype "bidirectional"))
    )
    (net (code "431") (name "Net-(U$71-EXT_IN)") (class "Default")
      (node (ref "R71") (pin "2") (pinfunction "2_2") (pintype "passive"))
      (node (ref "U$71") (pin "5") (pinfunction "EXT_IN_5") (pintype "bidirectional"))
    )
    (net (code "432") (name "Net-(U$71-EXT_OUT)") (class "Default")
      (node (ref "R71") (pin "1") (pinfunction "1_1") (pintype "passive"))
      (node (ref "U$71") (pin "6") (pinfunction "EXT_OUT_6") (pintype "bidirectional"))
    )
    (net (code "433") (name "Net-(U$72-EXT_IN)") (class "Default")
      (node (ref "R72") (pin "2") (pinfunction "2_2") (pintype "passive"))
      (node (ref "U$72") (pin "5") (pinfunction "EXT_IN_5") (pintype "bidirectional"))
    )
    (net (code "434") (name "Net-(U$72-EXT_OUT)") (class "Default")
      (node (ref "R72") (pin "1") (pinfunction "1_1") (pintype "passive"))
      (node (ref "U$72") (pin "6") (pinfunction "EXT_OUT_6") (pintype "bidirectional"))
    )
    (net (code "435") (name "Net-(U$73-EXT_IN)") (class "Default")
      (node (ref "R73") (pin "2") (pinfunction "2_2") (pintype "passive"))
      (node (ref "U$73") (pin "5") (pinfunction "EXT_IN_5") (pintype "bidirectional"))
    )
    (net (code "436") (name "Net-(U$73-EXT_OUT)") (class "Default")
      (node (ref "R73") (pin "1") (pinfunction "1_1") (pintype "passive"))
      (node (ref "U$73") (pin "6") (pinfunction "EXT_OUT_6") (pintype "bidirectional"))
    )
    (net (code "437") (name "Net-(U$74-EXT_IN)") (class "Default")
      (node (ref "R74") (pin "2") (pinfunction "2_2") (pintype "passive"))
      (node (ref "U$74") (pin "5") (pinfunction "EXT_IN_5") (pintype "bidirectional"))
    )
    (net (code "438") (name "Net-(U$74-EXT_OUT)") (class "Default")
      (node (ref "R74") (pin "1") (pinfunction "1_1") (pintype "passive"))
      (node (ref "U$74") (pin "6") (pinfunction "EXT_OUT_6") (pintype "bidirectional"))
    )
    (net (code "439") (name "Net-(U$75-EXT_IN)") (class "Default")
      (node (ref "R75") (pin "2") (pinfunction "2_2") (pintype "passive"))
      (node (ref "U$75") (pin "5") (pinfunction "EXT_IN_5") (pintype "bidirectional"))
    )
    (net (code "440") (name "Net-(U$75-EXT_OUT)") (class "Default")
      (node (ref "R75") (pin "1") (pinfunction "1_1") (pintype "passive"))
      (node (ref "U$75") (pin "6") (pinfunction "EXT_OUT_6") (pintype "bidirectional"))
    )
    (net (code "441") (name "Net-(U$76-EXT_IN)") (class "Default")
      (node (ref "R76") (pin "2") (pinfunction "2_2") (pintype "passive"))
      (node (ref "U$76") (pin "5") (pinfunction "EXT_IN_5") (pintype "bidirectional"))
    )
    (net (code "442") (name "Net-(U$76-EXT_OUT)") (class "Default")
      (node (ref "R76") (pin "1") (pinfunction "1_1") (pintype "passive"))
      (node (ref "U$76") (pin "6") (pinfunction "EXT_OUT_6") (pintype "bidirectional"))
    )
    (net (code "443") (name "Net-(U$77-EXT_IN)") (class "Default")
      (node (ref "R77") (pin "2") (pinfunction "2_2") (pintype "passive"))
      (node (ref "U$77") (pin "5") (pinfunction "EXT_IN_5") (pintype "bidirectional"))
    )
    (net (code "444") (name "Net-(U$77-EXT_OUT)") (class "Default")
      (node (ref "R77") (pin "1") (pinfunction "1_1") (pintype "passive"))
      (node (ref "U$77") (pin "6") (pinfunction "EXT_OUT_6") (pintype "bidirectional"))
    )
    (net (code "445") (name "Net-(U$78-EXT_IN)") (class "Default")
      (node (ref "R78") (pin "2") (pinfunction "2_2") (pintype "passive"))
      (node (ref "U$78") (pin "5") (pinfunction "EXT_IN_5") (pintype "bidirectional"))
    )
    (net (code "446") (name "Net-(U$78-EXT_OUT)") (class "Default")
      (node (ref "R78") (pin "1") (pinfunction "1_1") (pintype "passive"))
      (node (ref "U$78") (pin "6") (pinfunction "EXT_OUT_6") (pintype "bidirectional"))
    )
    (net (code "447") (name "Net-(U$79-EXT_IN)") (class "Default")
      (node (ref "R79") (pin "2") (pinfunction "2_2") (pintype "passive"))
      (node (ref "U$79") (pin "5") (pinfunction "EXT_IN_5") (pintype "bidirectional"))
    )
    (net (code "448") (name "Net-(U$79-EXT_OUT)") (class "Default")
      (node (ref "R79") (pin "1") (pinfunction "1_1") (pintype "passive"))
      (node (ref "U$79") (pin "6") (pinfunction "EXT_OUT_6") (pintype "bidirectional"))
    )
    (net (code "449") (name "Net-(U$80-EXT_IN)") (class "Default")
      (node (ref "R80") (pin "2") (pinfunction "2_2") (pintype "passive"))
      (node (ref "U$80") (pin "5") (pinfunction "EXT_IN_5") (pintype "bidirectional"))
    )
    (net (code "450") (name "Net-(U$80-EXT_OUT)") (class "Default")
      (node (ref "R80") (pin "1") (pinfunction "1_1") (pintype "passive"))
      (node (ref "U$80") (pin "6") (pinfunction "EXT_OUT_6") (pintype "bidirectional"))
    )
    (net (code "451") (name "Net-(U$81-EXT_IN)") (class "Default")
      (node (ref "R81") (pin "2") (pinfunction "2_2") (pintype "passive"))
      (node (ref "U$81") (pin "5") (pinfunction "EXT_IN_5") (pintype "bidirectional"))
    )
    (net (code "452") (name "Net-(U$81-EXT_OUT)") (class "Default")
      (node (ref "R81") (pin "1") (pinfunction "1_1") (pintype "passive"))
      (node (ref "U$81") (pin "6") (pinfunction "EXT_OUT_6") (pintype "bidirectional"))
    )
    (net (code "453") (name "Net-(U$82-EXT_IN)") (class "Default")
      (node (ref "R82") (pin "2") (pinfunction "2_2") (pintype "passive"))
      (node (ref "U$82") (pin "5") (pinfunction "EXT_IN_5") (pintype "bidirectional"))
    )
    (net (code "454") (name "Net-(U$82-EXT_OUT)") (class "Default")
      (node (ref "R82") (pin "1") (pinfunction "1_1") (pintype "passive"))
      (node (ref "U$82") (pin "6") (pinfunction "EXT_OUT_6") (pintype "bidirectional"))
    )
    (net (code "455") (name "Net-(U$83-EXT_IN)") (class "Default")
      (node (ref "R83") (pin "2") (pinfunction "2_2") (pintype "passive"))
      (node (ref "U$83") (pin "5") (pinfunction "EXT_IN_5") (pintype "bidirectional"))
    )
    (net (code "456") (name "Net-(U$83-EXT_OUT)") (class "Default")
      (node (ref "R83") (pin "1") (pinfunction "1_1") (pintype "passive"))
      (node (ref "U$83") (pin "6") (pinfunction "EXT_OUT_6") (pintype "bidirectional"))
    )
    (net (code "457") (name "Net-(U$84-EXT_IN)") (class "Default")
      (node (ref "R84") (pin "2") (pinfunction "2_2") (pintype "passive"))
      (node (ref "U$84") (pin "5") (pinfunction "EXT_IN_5") (pintype "bidirectional"))
    )
    (net (code "458") (name "Net-(U$84-EXT_OUT)") (class "Default")
      (node (ref "R84") (pin "1") (pinfunction "1_1") (pintype "passive"))
      (node (ref "U$84") (pin "6") (pinfunction "EXT_OUT_6") (pintype "bidirectional"))
    )
    (net (code "459") (name "Net-(U$85-EXT_IN)") (class "Default")
      (node (ref "R85") (pin "2") (pinfunction "2_2") (pintype "passive"))
      (node (ref "U$85") (pin "5") (pinfunction "EXT_IN_5") (pintype "bidirectional"))
    )
    (net (code "460") (name "Net-(U$85-EXT_OUT)") (class "Default")
      (node (ref "R85") (pin "1") (pinfunction "1_1") (pintype "passive"))
      (node (ref "U$85") (pin "6") (pinfunction "EXT_OUT_6") (pintype "bidirectional"))
    )
    (net (code "461") (name "Net-(U$86-EXT_IN)") (class "Default")
      (node (ref "R86") (pin "2") (pinfunction "2_2") (pintype "passive"))
      (node (ref "U$86") (pin "5") (pinfunction "EXT_IN_5") (pintype "bidirectional"))
    )
    (net (code "462") (name "Net-(U$86-EXT_OUT)") (class "Default")
      (node (ref "R86") (pin "1") (pinfunction "1_1") (pintype "passive"))
      (node (ref "U$86") (pin "6") (pinfunction "EXT_OUT_6") (pintype "bidirectional"))
    )
    (net (code "463") (name "Net-(U$87-EXT_IN)") (class "Default")
      (node (ref "R87") (pin "2") (pinfunction "2_2") (pintype "passive"))
      (node (ref "U$87") (pin "5") (pinfunction "EXT_IN_5") (pintype "bidirectional"))
    )
    (net (code "464") (name "Net-(U$87-EXT_OUT)") (class "Default")
      (node (ref "R87") (pin "1") (pinfunction "1_1") (pintype "passive"))
      (node (ref "U$87") (pin "6") (pinfunction "EXT_OUT_6") (pintype "bidirectional"))
    )
    (net (code "465") (name "Net-(U$88-EXT_IN)") (class "Default")
      (node (ref "R88") (pin "2") (pinfunction "2_2") (pintype "passive"))
      (node (ref "U$88") (pin "5") (pinfunction "EXT_IN_5") (pintype "bidirectional"))
    )
    (net (code "466") (name "Net-(U$88-EXT_OUT)") (class "Default")
      (node (ref "R88") (pin "1") (pinfunction "1_1") (pintype "passive"))
      (node (ref "U$88") (pin "6") (pinfunction "EXT_OUT_6") (pintype "bidirectional"))
    )
    (net (code "467") (name "Net-(U$89-EXT_IN)") (class "Default")
      (node (ref "R89") (pin "2") (pinfunction "2_2") (pintype "passive"))
      (node (ref "U$89") (pin "5") (pinfunction "EXT_IN_5") (pintype "bidirectional"))
    )
    (net (code "468") (name "Net-(U$89-EXT_OUT)") (class "Default")
      (node (ref "R89") (pin "1") (pinfunction "1_1") (pintype "passive"))
      (node (ref "U$89") (pin "6") (pinfunction "EXT_OUT_6") (pintype "bidirectional"))
    )
    (net (code "469") (name "Net-(U$90-EXT_IN)") (class "Default")
      (node (ref "R90") (pin "2") (pinfunction "2_2") (pintype "passive"))
      (node (ref "U$90") (pin "5") (pinfunction "EXT_IN_5") (pintype "bidirectional"))
    )
    (net (code "470") (name "Net-(U$90-EXT_OUT)") (class "Default")
      (node (ref "R90") (pin "1") (pinfunction "1_1") (pintype "passive"))
      (node (ref "U$90") (pin "6") (pinfunction "EXT_OUT_6") (pintype "bidirectional"))
    )
    (net (code "471") (name "Net-(U$91-EXT_IN)") (class "Default")
      (node (ref "R91") (pin "2") (pinfunction "2_2") (pintype "passive"))
      (node (ref "U$91") (pin "5") (pinfunction "EXT_IN_5") (pintype "bidirectional"))
    )
    (net (code "472") (name "Net-(U$91-EXT_OUT)") (class "Default")
      (node (ref "R91") (pin "1") (pinfunction "1_1") (pintype "passive"))
      (node (ref "U$91") (pin "6") (pinfunction "EXT_OUT_6") (pintype "bidirectional"))
    )
    (net (code "473") (name "Net-(U$92-EXT_IN)") (class "Default")
      (node (ref "R92") (pin "2") (pinfunction "2_2") (pintype "passive"))
      (node (ref "U$92") (pin "5") (pinfunction "EXT_IN_5") (pintype "bidirectional"))
    )
    (net (code "474") (name "Net-(U$92-EXT_OUT)") (class "Default")
      (node (ref "R92") (pin "1") (pinfunction "1_1") (pintype "passive"))
      (node (ref "U$92") (pin "6") (pinfunction "EXT_OUT_6") (pintype "bidirectional"))
    )
    (net (code "475") (name "Net-(U$93-EXT_IN)") (class "Default")
      (node (ref "R93") (pin "2") (pinfunction "2_2") (pintype "passive"))
      (node (ref "U$93") (pin "5") (pinfunction "EXT_IN_5") (pintype "bidirectional"))
    )
    (net (code "476") (name "Net-(U$93-EXT_OUT)") (class "Default")
      (node (ref "R93") (pin "1") (pinfunction "1_1") (pintype "passive"))
      (node (ref "U$93") (pin "6") (pinfunction "EXT_OUT_6") (pintype "bidirectional"))
    )
    (net (code "477") (name "Net-(U$94-EXT_IN)") (class "Default")
      (node (ref "R94") (pin "2") (pinfunction "2_2") (pintype "passive"))
      (node (ref "U$94") (pin "5") (pinfunction "EXT_IN_5") (pintype "bidirectional"))
    )
    (net (code "478") (name "Net-(U$94-EXT_OUT)") (class "Default")
      (node (ref "R94") (pin "1") (pinfunction "1_1") (pintype "passive"))
      (node (ref "U$94") (pin "6") (pinfunction "EXT_OUT_6") (pintype "bidirectional"))
    )
    (net (code "479") (name "Net-(U$95-EXT_IN)") (class "Default")
      (node (ref "R95") (pin "2") (pinfunction "2_2") (pintype "passive"))
      (node (ref "U$95") (pin "5") (pinfunction "EXT_IN_5") (pintype "bidirectional"))
    )
    (net (code "480") (name "Net-(U$95-EXT_OUT)") (class "Default")
      (node (ref "R95") (pin "1") (pinfunction "1_1") (pintype "passive"))
      (node (ref "U$95") (pin "6") (pinfunction "EXT_OUT_6") (pintype "bidirectional"))
    )
    (net (code "481") (name "Net-(U$96-EXT_IN)") (class "Default")
      (node (ref "R96") (pin "2") (pinfunction "2_2") (pintype "passive"))
      (node (ref "U$96") (pin "5") (pinfunction "EXT_IN_5") (pintype "bidirectional"))
    )
    (net (code "482") (name "Net-(U$96-EXT_OUT)") (class "Default")
      (node (ref "R96") (pin "1") (pinfunction "1_1") (pintype "passive"))
      (node (ref "U$96") (pin "6") (pinfunction "EXT_OUT_6") (pintype "bidirectional"))
    )
    (net (code "483") (name "VDD") (class "Default")
      (node (ref "C10") (pin "1") (pinfunction "1_1") (pintype "passive"))
      (node (ref "C100") (pin "1") (pinfunction "1_1") (pintype "passive"))
      (node (ref "C102") (pin "1") (pinfunction "1_1") (pintype "passive"))
      (node (ref "C104") (pin "1") (pinfunction "1_1") (pintype "passive"))
      (node (ref "C106") (pin "1") (pinfunction "1_1") (pintype "passive"))
      (node (ref "C108") (pin "1") (pinfunction "1_1") (pintype "passive"))
      (node (ref "C110") (pin "1") (pinfunction "1_1") (pintype "passive"))
      (node (ref "C112") (pin "1") (pinfunction "1_1") (pintype "passive"))
      (node (ref "C114") (pin "1") (pinfunction "1_1") (pintype "passive"))
      (node (ref "C116") (pin "1") (pinfunction "1_1") (pintype "passive"))
      (node (ref "C118") (pin "1") (pinfunction "1_1") (pintype "passive"))
      (node (ref "C12") (pin "1") (pinfunction "1_1") (pintype "passive"))
      (node (ref "C120") (pin "1") (pinfunction "1_1") (pintype "passive"))
      (node (ref "C122") (pin "1") (pinfunction "1_1") (pintype "passive"))
      (node (ref "C124") (pin "1") (pinfunction "1_1") (pintype "passive"))
      (node (ref "C126") (pin "1") (pinfunction "1_1") (pintype "passive"))
      (node (ref "C128") (pin "1") (pinfunction "1_1") (pintype "passive"))
      (node (ref "C130") (pin "1") (pinfunction "1_1") (pintype "passive"))
      (node (ref "C132") (pin "1") (pinfunction "1_1") (pintype "passive"))
      (node (ref "C134") (pin "1") (pinfunction "1_1") (pintype "passive"))
      (node (ref "C136") (pin "1") (pinfunction "1_1") (pintype "passive"))
      (node (ref "C138") (pin "1") (pinfunction "1_1") (pintype "passive"))
      (node (ref "C14") (pin "1") (pinfunction "1_1") (pintype "passive"))
      (node (ref "C140") (pin "1") (pinfunction "1_1") (pintype "passive"))
      (node (ref "C142") (pin "1") (pinfunction "1_1") (pintype "passive"))
      (node (ref "C144") (pin "1") (pinfunction "1_1") (pintype "passive"))
      (node (ref "C146") (pin "1") (pinfunction "1_1") (pintype "passive"))
      (node (ref "C148") (pin "1") (pinfunction "1_1") (pintype "passive"))
      (node (ref "C150") (pin "1") (pinfunction "1_1") (pintype "passive"))
      (node (ref "C152") (pin "1") (pinfunction "1_1") (pintype "passive"))
      (node (ref "C154") (pin "1") (pinfunction "1_1") (pintype "passive"))
      (node (ref "C156") (pin "1") (pinfunction "1_1") (pintype "passive"))
      (node (ref "C158") (pin "1") (pinfunction "1_1") (pintype "passive"))
      (node (ref "C16") (pin "1") (pinfunction "1_1") (pintype "passive"))
      (node (ref "C160") (pin "1") (pinfunction "1_1") (pintype "passive"))
      (node (ref "C162") (pin "1") (pinfunction "1_1") (pintype "passive"))
      (node (ref "C164") (pin "1") (pinfunction "1_1") (pintype "passive"))
      (node (ref "C166") (pin "1") (pinfunction "1_1") (pintype "passive"))
      (node (ref "C168") (pin "1") (pinfunction "1_1") (pintype "passive"))
      (node (ref "C170") (pin "1") (pinfunction "1_1") (pintype "passive"))
      (node (ref "C172") (pin "1") (pinfunction "1_1") (pintype "passive"))
      (node (ref "C174") (pin "1") (pinfunction "1_1") (pintype "passive"))
      (node (ref "C176") (pin "1") (pinfunction "1_1") (pintype "passive"))
      (node (ref "C178") (pin "1") (pinfunction "1_1") (pintype "passive"))
      (node (ref "C18") (pin "1") (pinfunction "1_1") (pintype "passive"))
      (node (ref "C180") (pin "1") (pinfunction "1_1") (pintype "passive"))
      (node (ref "C182") (pin "1") (pinfunction "1_1") (pintype "passive"))
      (node (ref "C184") (pin "1") (pinfunction "1_1") (pintype "passive"))
      (node (ref "C186") (pin "1") (pinfunction "1_1") (pintype "passive"))
      (node (ref "C188") (pin "1") (pinfunction "1_1") (pintype "passive"))
      (node (ref "C190") (pin "1") (pinfunction "1_1") (pintype "passive"))
      (node (ref "C192") (pin "1") (pinfunction "1_1") (pintype "passive"))
      (node (ref "C2") (pin "1") (pinfunction "1_1") (pintype "passive"))
      (node (ref "C20") (pin "1") (pinfunction "1_1") (pintype "passive"))
      (node (ref "C22") (pin "1") (pinfunction "1_1") (pintype "passive"))
      (node (ref "C24") (pin "1") (pinfunction "1_1") (pintype "passive"))
      (node (ref "C26") (pin "1") (pinfunction "1_1") (pintype "passive"))
      (node (ref "C28") (pin "1") (pinfunction "1_1") (pintype "passive"))
      (node (ref "C30") (pin "1") (pinfunction "1_1") (pintype "passive"))
      (node (ref "C32") (pin "1") (pinfunction "1_1") (pintype "passive"))
      (node (ref "C34") (pin "1") (pinfunction "1_1") (pintype "passive"))
      (node (ref "C36") (pin "1") (pinfunction "1_1") (pintype "passive"))
      (node (ref "C38") (pin "1") (pinfunction "1_1") (pintype "passive"))
      (node (ref "C4") (pin "1") (pinfunction "1_1") (pintype "passive"))
      (node (ref "C40") (pin "1") (pinfunction "1_1") (pintype "passive"))
      (node (ref "C42") (pin "1") (pinfunction "1_1") (pintype "passive"))
      (node (ref "C44") (pin "1") (pinfunction "1_1") (pintype "passive"))
      (node (ref "C46") (pin "1") (pinfunction "1_1") (pintype "passive"))
      (node (ref "C48") (pin "1") (pinfunction "1_1") (pintype "passive"))
      (node (ref "C50") (pin "1") (pinfunction "1_1") (pintype "passive"))
      (node (ref "C52") (pin "1") (pinfunction "1_1") (pintype "passive"))
      (node (ref "C54") (pin "1") (pinfunction "1_1") (pintype "passive"))
      (node (ref "C56") (pin "1") (pinfunction "1_1") (pintype "passive"))
      (node (ref "C58") (pin "1") (pinfunction "1_1") (pintype "passive"))
      (node (ref "C6") (pin "1") (pinfunction "1_1") (pintype "passive"))
      (node (ref "C60") (pin "1") (pinfunction "1_1") (pintype "passive"))
      (node (ref "C62") (pin "1") (pinfunction "1_1") (pintype "passive"))
      (node (ref "C64") (pin "1") (pinfunction "1_1") (pintype "passive"))
      (node (ref "C66") (pin "1") (pinfunction "1_1") (pintype "passive"))
      (node (ref "C68") (pin "1") (pinfunction "1_1") (pintype "passive"))
      (node (ref "C70") (pin "1") (pinfunction "1_1") (pintype "passive"))
      (node (ref "C72") (pin "1") (pinfunction "1_1") (pintype "passive"))
      (node (ref "C74") (pin "1") (pinfunction "1_1") (pintype "passive"))
      (node (ref "C76") (pin "1") (pinfunction "1_1") (pintype "passive"))
      (node (ref "C78") (pin "1") (pinfunction "1_1") (pintype "passive"))
      (node (ref "C8") (pin "1") (pinfunction "1_1") (pintype "passive"))
      (node (ref "C80") (pin "1") (pinfunction "1_1") (pintype "passive"))
      (node (ref "C82") (pin "1") (pinfunction "1_1") (pintype "passive"))
      (node (ref "C84") (pin "1") (pinfunction "1_1") (pintype "passive"))
      (node (ref "C86") (pin "1") (pinfunction "1_1") (pintype "passive"))
      (node (ref "C88") (pin "1") (pinfunction "1_1") (pintype "passive"))
      (node (ref "C90") (pin "1") (pinfunction "1_1") (pintype "passive"))
      (node (ref "C92") (pin "1") (pinfunction "1_1") (pintype "passive"))
      (node (ref "C94") (pin "1") (pinfunction "1_1") (pintype "passive"))
      (node (ref "C96") (pin "1") (pinfunction "1_1") (pintype "passive"))
      (node (ref "C98") (pin "1") (pinfunction "1_1") (pintype "passive"))
      (node (ref "SV1") (pin "10") (pinfunction "10_10") (pintype "passive"))
      (node (ref "SV1") (pin "7") (pinfunction "7_7") (pintype "passive"))
      (node (ref "SV1") (pin "8") (pinfunction "8_8") (pintype "passive"))
      (node (ref "SV1") (pin "9") (pinfunction "9_9") (pintype "passive"))
      (node (ref "U$1") (pin "1") (pinfunction "VDD_1") (pintype "bidirectional"))
      (node (ref "U$1") (pin "4") (pinfunction "VDD_IO_4") (pintype "bidirectional"))
      (node (ref "U$10") (pin "1") (pinfunction "VDD_1") (pintype "bidirectional"))
      (node (ref "U$10") (pin "4") (pinfunction "VDD_IO_4") (pintype "bidirectional"))
      (node (ref "U$11") (pin "1") (pinfunction "VDD_1") (pintype "bidirectional"))
      (node (ref "U$11") (pin "4") (pinfunction "VDD_IO_4") (pintype "bidirectional"))
      (node (ref "U$12") (pin "1") (pinfunction "VDD_1") (pintype "bidirectional"))
      (node (ref "U$12") (pin "4") (pinfunction "VDD_IO_4") (pintype "bidirectional"))
      (node (ref "U$13") (pin "1") (pinfunction "VDD_1") (pintype "bidirectional"))
      (node (ref "U$13") (pin "4") (pinfunction "VDD_IO_4") (pintype "bidirectional"))
      (node (ref "U$14") (pin "1") (pinfunction "VDD_1") (pintype "bidirectional"))
      (node (ref "U$14") (pin "4") (pinfunction "VDD_IO_4") (pintype "bidirectional"))
      (node (ref "U$15") (pin "1") (pinfunction "VDD_1") (pintype "bidirectional"))
      (node (ref "U$15") (pin "4") (pinfunction "VDD_IO_4") (pintype "bidirectional"))
      (node (ref "U$16") (pin "1") (pinfunction "VDD_1") (pintype "bidirectional"))
      (node (ref "U$16") (pin "4") (pinfunction "VDD_IO_4") (pintype "bidirectional"))
      (node (ref "U$17") (pin "1") (pinfunction "VDD_1") (pintype "bidirectional"))
      (node (ref "U$17") (pin "4") (pinfunction "VDD_IO_4") (pintype "bidirectional"))
      (node (ref "U$18") (pin "1") (pinfunction "VDD_1") (pintype "bidirectional"))
      (node (ref "U$18") (pin "4") (pinfunction "VDD_IO_4") (pintype "bidirectional"))
      (node (ref "U$19") (pin "1") (pinfunction "VDD_1") (pintype "bidirectional"))
      (node (ref "U$19") (pin "4") (pinfunction "VDD_IO_4") (pintype "bidirectional"))
      (node (ref "U$2") (pin "1") (pinfunction "VDD_1") (pintype "bidirectional"))
      (node (ref "U$2") (pin "4") (pinfunction "VDD_IO_4") (pintype "bidirectional"))
      (node (ref "U$20") (pin "1") (pinfunction "VDD_1") (pintype "bidirectional"))
      (node (ref "U$20") (pin "4") (pinfunction "VDD_IO_4") (pintype "bidirectional"))
      (node (ref "U$21") (pin "1") (pinfunction "VDD_1") (pintype "bidirectional"))
      (node (ref "U$21") (pin "4") (pinfunction "VDD_IO_4") (pintype "bidirectional"))
      (node (ref "U$22") (pin "1") (pinfunction "VDD_1") (pintype "bidirectional"))
      (node (ref "U$22") (pin "4") (pinfunction "VDD_IO_4") (pintype "bidirectional"))
      (node (ref "U$23") (pin "1") (pinfunction "VDD_1") (pintype "bidirectional"))
      (node (ref "U$23") (pin "4") (pinfunction "VDD_IO_4") (pintype "bidirectional"))
      (node (ref "U$24") (pin "1") (pinfunction "VDD_1") (pintype "bidirectional"))
      (node (ref "U$24") (pin "4") (pinfunction "VDD_IO_4") (pintype "bidirectional"))
      (node (ref "U$25") (pin "1") (pinfunction "VDD_1") (pintype "bidirectional"))
      (node (ref "U$25") (pin "4") (pinfunction "VDD_IO_4") (pintype "bidirectional"))
      (node (ref "U$26") (pin "1") (pinfunction "VDD_1") (pintype "bidirectional"))
      (node (ref "U$26") (pin "4") (pinfunction "VDD_IO_4") (pintype "bidirectional"))
      (node (ref "U$27") (pin "1") (pinfunction "VDD_1") (pintype "bidirectional"))
      (node (ref "U$27") (pin "4") (pinfunction "VDD_IO_4") (pintype "bidirectional"))
      (node (ref "U$28") (pin "1") (pinfunction "VDD_1") (pintype "bidirectional"))
      (node (ref "U$28") (pin "4") (pinfunction "VDD_IO_4") (pintype "bidirectional"))
      (node (ref "U$29") (pin "1") (pinfunction "VDD_1") (pintype "bidirectional"))
      (node (ref "U$29") (pin "4") (pinfunction "VDD_IO_4") (pintype "bidirectional"))
      (node (ref "U$3") (pin "1") (pinfunction "VDD_1") (pintype "bidirectional"))
      (node (ref "U$3") (pin "4") (pinfunction "VDD_IO_4") (pintype "bidirectional"))
      (node (ref "U$30") (pin "1") (pinfunction "VDD_1") (pintype "bidirectional"))
      (node (ref "U$30") (pin "4") (pinfunction "VDD_IO_4") (pintype "bidirectional"))
      (node (ref "U$31") (pin "1") (pinfunction "VDD_1") (pintype "bidirectional"))
      (node (ref "U$31") (pin "4") (pinfunction "VDD_IO_4") (pintype "bidirectional"))
      (node (ref "U$32") (pin "1") (pinfunction "VDD_1") (pintype "bidirectional"))
      (node (ref "U$32") (pin "4") (pinfunction "VDD_IO_4") (pintype "bidirectional"))
      (node (ref "U$33") (pin "1") (pinfunction "VDD_1") (pintype "bidirectional"))
      (node (ref "U$33") (pin "4") (pinfunction "VDD_IO_4") (pintype "bidirectional"))
      (node (ref "U$34") (pin "1") (pinfunction "VDD_1") (pintype "bidirectional"))
      (node (ref "U$34") (pin "4") (pinfunction "VDD_IO_4") (pintype "bidirectional"))
      (node (ref "U$35") (pin "1") (pinfunction "VDD_1") (pintype "bidirectional"))
      (node (ref "U$35") (pin "4") (pinfunction "VDD_IO_4") (pintype "bidirectional"))
      (node (ref "U$36") (pin "1") (pinfunction "VDD_1") (pintype "bidirectional"))
      (node (ref "U$36") (pin "4") (pinfunction "VDD_IO_4") (pintype "bidirectional"))
      (node (ref "U$37") (pin "1") (pinfunction "VDD_1") (pintype "bidirectional"))
      (node (ref "U$37") (pin "4") (pinfunction "VDD_IO_4") (pintype "bidirectional"))
      (node (ref "U$38") (pin "1") (pinfunction "VDD_1") (pintype "bidirectional"))
      (node (ref "U$38") (pin "4") (pinfunction "VDD_IO_4") (pintype "bidirectional"))
      (node (ref "U$39") (pin "1") (pinfunction "VDD_1") (pintype "bidirectional"))
      (node (ref "U$39") (pin "4") (pinfunction "VDD_IO_4") (pintype "bidirectional"))
      (node (ref "U$4") (pin "1") (pinfunction "VDD_1") (pintype "bidirectional"))
      (node (ref "U$4") (pin "4") (pinfunction "VDD_IO_4") (pintype "bidirectional"))
      (node (ref "U$40") (pin "1") (pinfunction "VDD_1") (pintype "bidirectional"))
      (node (ref "U$40") (pin "4") (pinfunction "VDD_IO_4") (pintype "bidirectional"))
      (node (ref "U$41") (pin "1") (pinfunction "VDD_1") (pintype "bidirectional"))
      (node (ref "U$41") (pin "4") (pinfunction "VDD_IO_4") (pintype "bidirectional"))
      (node (ref "U$42") (pin "1") (pinfunction "VDD_1") (pintype "bidirectional"))
      (node (ref "U$42") (pin "4") (pinfunction "VDD_IO_4") (pintype "bidirectional"))
      (node (ref "U$43") (pin "1") (pinfunction "VDD_1") (pintype "bidirectional"))
      (node (ref "U$43") (pin "4") (pinfunction "VDD_IO_4") (pintype "bidirectional"))
      (node (ref "U$44") (pin "1") (pinfunction "VDD_1") (pintype "bidirectional"))
      (node (ref "U$44") (pin "4") (pinfunction "VDD_IO_4") (pintype "bidirectional"))
      (node (ref "U$45") (pin "1") (pinfunction "VDD_1") (pintype "bidirectional"))
      (node (ref "U$45") (pin "4") (pinfunction "VDD_IO_4") (pintype "bidirectional"))
      (node (ref "U$46") (pin "1") (pinfunction "VDD_1") (pintype "bidirectional"))
      (node (ref "U$46") (pin "4") (pinfunction "VDD_IO_4") (pintype "bidirectional"))
      (node (ref "U$47") (pin "1") (pinfunction "VDD_1") (pintype "bidirectional"))
      (node (ref "U$47") (pin "4") (pinfunction "VDD_IO_4") (pintype "bidirectional"))
      (node (ref "U$48") (pin "1") (pinfunction "VDD_1") (pintype "bidirectional"))
      (node (ref "U$48") (pin "4") (pinfunction "VDD_IO_4") (pintype "bidirectional"))
      (node (ref "U$49") (pin "1") (pinfunction "VDD_1") (pintype "bidirectional"))
      (node (ref "U$49") (pin "4") (pinfunction "VDD_IO_4") (pintype "bidirectional"))
      (node (ref "U$5") (pin "1") (pinfunction "VDD_1") (pintype "bidirectional"))
      (node (ref "U$5") (pin "4") (pinfunction "VDD_IO_4") (pintype "bidirectional"))
      (node (ref "U$50") (pin "1") (pinfunction "VDD_1") (pintype "bidirectional"))
      (node (ref "U$50") (pin "4") (pinfunction "VDD_IO_4") (pintype "bidirectional"))
      (node (ref "U$51") (pin "1") (pinfunction "VDD_1") (pintype "bidirectional"))
      (node (ref "U$51") (pin "4") (pinfunction "VDD_IO_4") (pintype "bidirectional"))
      (node (ref "U$52") (pin "1") (pinfunction "VDD_1") (pintype "bidirectional"))
      (node (ref "U$52") (pin "4") (pinfunction "VDD_IO_4") (pintype "bidirectional"))
      (node (ref "U$53") (pin "1") (pinfunction "VDD_1") (pintype "bidirectional"))
      (node (ref "U$53") (pin "4") (pinfunction "VDD_IO_4") (pintype "bidirectional"))
      (node (ref "U$54") (pin "1") (pinfunction "VDD_1") (pintype "bidirectional"))
      (node (ref "U$54") (pin "4") (pinfunction "VDD_IO_4") (pintype "bidirectional"))
      (node (ref "U$55") (pin "1") (pinfunction "VDD_1") (pintype "bidirectional"))
      (node (ref "U$55") (pin "4") (pinfunction "VDD_IO_4") (pintype "bidirectional"))
      (node (ref "U$56") (pin "1") (pinfunction "VDD_1") (pintype "bidirectional"))
      (node (ref "U$56") (pin "4") (pinfunction "VDD_IO_4") (pintype "bidirectional"))
      (node (ref "U$57") (pin "1") (pinfunction "VDD_1") (pintype "bidirectional"))
      (node (ref "U$57") (pin "4") (pinfunction "VDD_IO_4") (pintype "bidirectional"))
      (node (ref "U$58") (pin "1") (pinfunction "VDD_1") (pintype "bidirectional"))
      (node (ref "U$58") (pin "4") (pinfunction "VDD_IO_4") (pintype "bidirectional"))
      (node (ref "U$59") (pin "1") (pinfunction "VDD_1") (pintype "bidirectional"))
      (node (ref "U$59") (pin "4") (pinfunction "VDD_IO_4") (pintype "bidirectional"))
      (node (ref "U$6") (pin "1") (pinfunction "VDD_1") (pintype "bidirectional"))
      (node (ref "U$6") (pin "4") (pinfunction "VDD_IO_4") (pintype "bidirectional"))
      (node (ref "U$60") (pin "1") (pinfunction "VDD_1") (pintype "bidirectional"))
      (node (ref "U$60") (pin "4") (pinfunction "VDD_IO_4") (pintype "bidirectional"))
      (node (ref "U$61") (pin "1") (pinfunction "VDD_1") (pintype "bidirectional"))
      (node (ref "U$61") (pin "4") (pinfunction "VDD_IO_4") (pintype "bidirectional"))
      (node (ref "U$62") (pin "1") (pinfunction "VDD_1") (pintype "bidirectional"))
      (node (ref "U$62") (pin "4") (pinfunction "VDD_IO_4") (pintype "bidirectional"))
      (node (ref "U$63") (pin "1") (pinfunction "VDD_1") (pintype "bidirectional"))
      (node (ref "U$63") (pin "4") (pinfunction "VDD_IO_4") (pintype "bidirectional"))
      (node (ref "U$64") (pin "1") (pinfunction "VDD_1") (pintype "bidirectional"))
      (node (ref "U$64") (pin "4") (pinfunction "VDD_IO_4") (pintype "bidirectional"))
      (node (ref "U$65") (pin "1") (pinfunction "VDD_1") (pintype "bidirectional"))
      (node (ref "U$65") (pin "4") (pinfunction "VDD_IO_4") (pintype "bidirectional"))
      (node (ref "U$66") (pin "1") (pinfunction "VDD_1") (pintype "bidirectional"))
      (node (ref "U$66") (pin "4") (pinfunction "VDD_IO_4") (pintype "bidirectional"))
      (node (ref "U$67") (pin "1") (pinfunction "VDD_1") (pintype "bidirectional"))
      (node (ref "U$67") (pin "4") (pinfunction "VDD_IO_4") (pintype "bidirectional"))
      (node (ref "U$68") (pin "1") (pinfunction "VDD_1") (pintype "bidirectional"))
      (node (ref "U$68") (pin "4") (pinfunction "VDD_IO_4") (pintype "bidirectional"))
      (node (ref "U$69") (pin "1") (pinfunction "VDD_1") (pintype "bidirectional"))
      (node (ref "U$69") (pin "4") (pinfunction "VDD_IO_4") (pintype "bidirectional"))
      (node (ref "U$7") (pin "1") (pinfunction "VDD_1") (pintype "bidirectional"))
      (node (ref "U$7") (pin "4") (pinfunction "VDD_IO_4") (pintype "bidirectional"))
      (node (ref "U$70") (pin "1") (pinfunction "VDD_1") (pintype "bidirectional"))
      (node (ref "U$70") (pin "4") (pinfunction "VDD_IO_4") (pintype "bidirectional"))
      (node (ref "U$71") (pin "1") (pinfunction "VDD_1") (pintype "bidirectional"))
      (node (ref "U$71") (pin "4") (pinfunction "VDD_IO_4") (pintype "bidirectional"))
      (node (ref "U$72") (pin "1") (pinfunction "VDD_1") (pintype "bidirectional"))
      (node (ref "U$72") (pin "4") (pinfunction "VDD_IO_4") (pintype "bidirectional"))
      (node (ref "U$73") (pin "1") (pinfunction "VDD_1") (pintype "bidirectional"))
      (node (ref "U$73") (pin "4") (pinfunction "VDD_IO_4") (pintype "bidirectional"))
      (node (ref "U$74") (pin "1") (pinfunction "VDD_1") (pintype "bidirectional"))
      (node (ref "U$74") (pin "4") (pinfunction "VDD_IO_4") (pintype "bidirectional"))
      (node (ref "U$75") (pin "1") (pinfunction "VDD_1") (pintype "bidirectional"))
      (node (ref "U$75") (pin "4") (pinfunction "VDD_IO_4") (pintype "bidirectional"))
      (node (ref "U$76") (pin "1") (pinfunction "VDD_1") (pintype "bidirectional"))
      (node (ref "U$76") (pin "4") (pinfunction "VDD_IO_4") (pintype "bidirectional"))
      (node (ref "U$77") (pin "1") (pinfunction "VDD_1") (pintype "bidirectional"))
      (node (ref "U$77") (pin "4") (pinfunction "VDD_IO_4") (pintype "bidirectional"))
      (node (ref "U$78") (pin "1") (pinfunction "VDD_1") (pintype "bidirectional"))
      (node (ref "U$78") (pin "4") (pinfunction "VDD_IO_4") (pintype "bidirectional"))
      (node (ref "U$79") (pin "1") (pinfunction "VDD_1") (pintype "bidirectional"))
      (node (ref "U$79") (pin "4") (pinfunction "VDD_IO_4") (pintype "bidirectional"))
      (node (ref "U$8") (pin "1") (pinfunction "VDD_1") (pintype "bidirectional"))
      (node (ref "U$8") (pin "4") (pinfunction "VDD_IO_4") (pintype "bidirectional"))
      (node (ref "U$80") (pin "1") (pinfunction "VDD_1") (pintype "bidirectional"))
      (node (ref "U$80") (pin "4") (pinfunction "VDD_IO_4") (pintype "bidirectional"))
      (node (ref "U$81") (pin "1") (pinfunction "VDD_1") (pintype "bidirectional"))
      (node (ref "U$81") (pin "4") (pinfunction "VDD_IO_4") (pintype "bidirectional"))
      (node (ref "U$82") (pin "1") (pinfunction "VDD_1") (pintype "bidirectional"))
      (node (ref "U$82") (pin "4") (pinfunction "VDD_IO_4") (pintype "bidirectional"))
      (node (ref "U$83") (pin "1") (pinfunction "VDD_1") (pintype "bidirectional"))
      (node (ref "U$83") (pin "4") (pinfunction "VDD_IO_4") (pintype "bidirectional"))
      (node (ref "U$84") (pin "1") (pinfunction "VDD_1") (pintype "bidirectional"))
      (node (ref "U$84") (pin "4") (pinfunction "VDD_IO_4") (pintype "bidirectional"))
      (node (ref "U$85") (pin "1") (pinfunction "VDD_1") (pintype "bidirectional"))
      (node (ref "U$85") (pin "4") (pinfunction "VDD_IO_4") (pintype "bidirectional"))
      (node (ref "U$86") (pin "1") (pinfunction "VDD_1") (pintype "bidirectional"))
      (node (ref "U$86") (pin "4") (pinfunction "VDD_IO_4") (pintype "bidirectional"))
      (node (ref "U$87") (pin "1") (pinfunction "VDD_1") (pintype "bidirectional"))
      (node (ref "U$87") (pin "4") (pinfunction "VDD_IO_4") (pintype "bidirectional"))
      (node (ref "U$88") (pin "1") (pinfunction "VDD_1") (pintype "bidirectional"))
      (node (ref "U$88") (pin "4") (pinfunction "VDD_IO_4") (pintype "bidirectional"))
      (node (ref "U$89") (pin "1") (pinfunction "VDD_1") (pintype "bidirectional"))
      (node (ref "U$89") (pin "4") (pinfunction "VDD_IO_4") (pintype "bidirectional"))
      (node (ref "U$9") (pin "1") (pinfunction "VDD_1") (pintype "bidirectional"))
      (node (ref "U$9") (pin "4") (pinfunction "VDD_IO_4") (pintype "bidirectional"))
      (node (ref "U$90") (pin "1") (pinfunction "VDD_1") (pintype "bidirectional"))
      (node (ref "U$90") (pin "4") (pinfunction "VDD_IO_4") (pintype "bidirectional"))
      (node (ref "U$91") (pin "1") (pinfunction "VDD_1") (pintype "bidirectional"))
      (node (ref "U$91") (pin "4") (pinfunction "VDD_IO_4") (pintype "bidirectional"))
      (node (ref "U$92") (pin "1") (pinfunction "VDD_1") (pintype "bidirectional"))
      (node (ref "U$92") (pin "4") (pinfunction "VDD_IO_4") (pintype "bidirectional"))
      (node (ref "U$93") (pin "1") (pinfunction "VDD_1") (pintype "bidirectional"))
      (node (ref "U$93") (pin "4") (pinfunction "VDD_IO_4") (pintype "bidirectional"))
      (node (ref "U$94") (pin "1") (pinfunction "VDD_1") (pintype "bidirectional"))
      (node (ref "U$94") (pin "4") (pinfunction "VDD_IO_4") (pintype "bidirectional"))
      (node (ref "U$95") (pin "1") (pinfunction "VDD_1") (pintype "bidirectional"))
      (node (ref "U$95") (pin "4") (pinfunction "VDD_IO_4") (pintype "bidirectional"))
      (node (ref "U$96") (pin "1") (pinfunction "VDD_1") (pintype "bidirectional"))
      (node (ref "U$96") (pin "4") (pinfunction "VDD_IO_4") (pintype "bidirectional"))
      (node (ref "U1") (pin "6") (pinfunction "VDDIO_6") (pintype "passive"))
      (node (ref "U1") (pin "8") (pinfunction "VDD_8") (pintype "passive"))
      (node (ref "U2") (pin "5") (pinfunction "VDD_5") (pintype "power_in"))
      (node (ref "U3") (pin "6") (pinfunction "VDDIO_6") (pintype "passive"))
      (node (ref "U3") (pin "8") (pinfunction "VDD_8") (pintype "passive"))
      (node (ref "U4") (pin "5") (pinfunction "VDD_5") (pintype "power_in"))
      (node (ref "U5") (pin "6") (pinfunction "VDDIO_6") (pintype "passive"))
      (node (ref "U5") (pin "8") (pinfunction "VDD_8") (pintype "passive"))
      (node (ref "U6") (pin "5") (pinfunction "VDD_5") (pintype "power_in"))
    )
    (net (code "484") (name "unconnected-(U1-CSB-Pad2)") (class "Default")
      (node (ref "U1") (pin "2") (pinfunction "CSB_2") (pintype "passive"))
    )
    (net (code "485") (name "unconnected-(U1-SDO-Pad5)") (class "Default")
      (node (ref "U1") (pin "5") (pinfunction "SDO_5") (pintype "passive"))
    )
    (net (code "486") (name "unconnected-(U2-1_NC-Pad3)") (class "Default")
      (node (ref "U2") (pin "3") (pinfunction "1_NC_3") (pintype "passive"))
    )
    (net (code "487") (name "unconnected-(U2-2_NC-Pad4)") (class "Default")
      (node (ref "U2") (pin "4") (pinfunction "2_NC_4") (pintype "passive"))
    )
    (net (code "488") (name "unconnected-(U3-CSB-Pad2)") (class "Default")
      (node (ref "U3") (pin "2") (pinfunction "CSB_2") (pintype "passive"))
    )
    (net (code "489") (name "unconnected-(U3-SDO-Pad5)") (class "Default")
      (node (ref "U3") (pin "5") (pinfunction "SDO_5") (pintype "passive"))
    )
    (net (code "490") (name "unconnected-(U4-1_NC-Pad3)") (class "Default")
      (node (ref "U4") (pin "3") (pinfunction "1_NC_3") (pintype "passive"))
    )
    (net (code "491") (name "unconnected-(U4-2_NC-Pad4)") (class "Default")
      (node (ref "U4") (pin "4") (pinfunction "2_NC_4") (pintype "passive"))
    )
    (net (code "492") (name "unconnected-(U5-CSB-Pad2)") (class "Default")
      (node (ref "U5") (pin "2") (pinfunction "CSB_2") (pintype "passive"))
    )
    (net (code "493") (name "unconnected-(U5-SDO-Pad5)") (class "Default")
      (node (ref "U5") (pin "5") (pinfunction "SDO_5") (pintype "passive"))
    )
    (net (code "494") (name "unconnected-(U6-1_NC-Pad3)") (class "Default")
      (node (ref "U6") (pin "3") (pinfunction "1_NC_3") (pintype "passive"))
    )
    (net (code "495") (name "unconnected-(U6-2_NC-Pad4)") (class "Default")
      (node (ref "U6") (pin "4") (pinfunction "2_NC_4") (pintype "passive"))
    )
  )
)
